# VNA.net
KiCad netlist of a schematic drawn in EAGLE
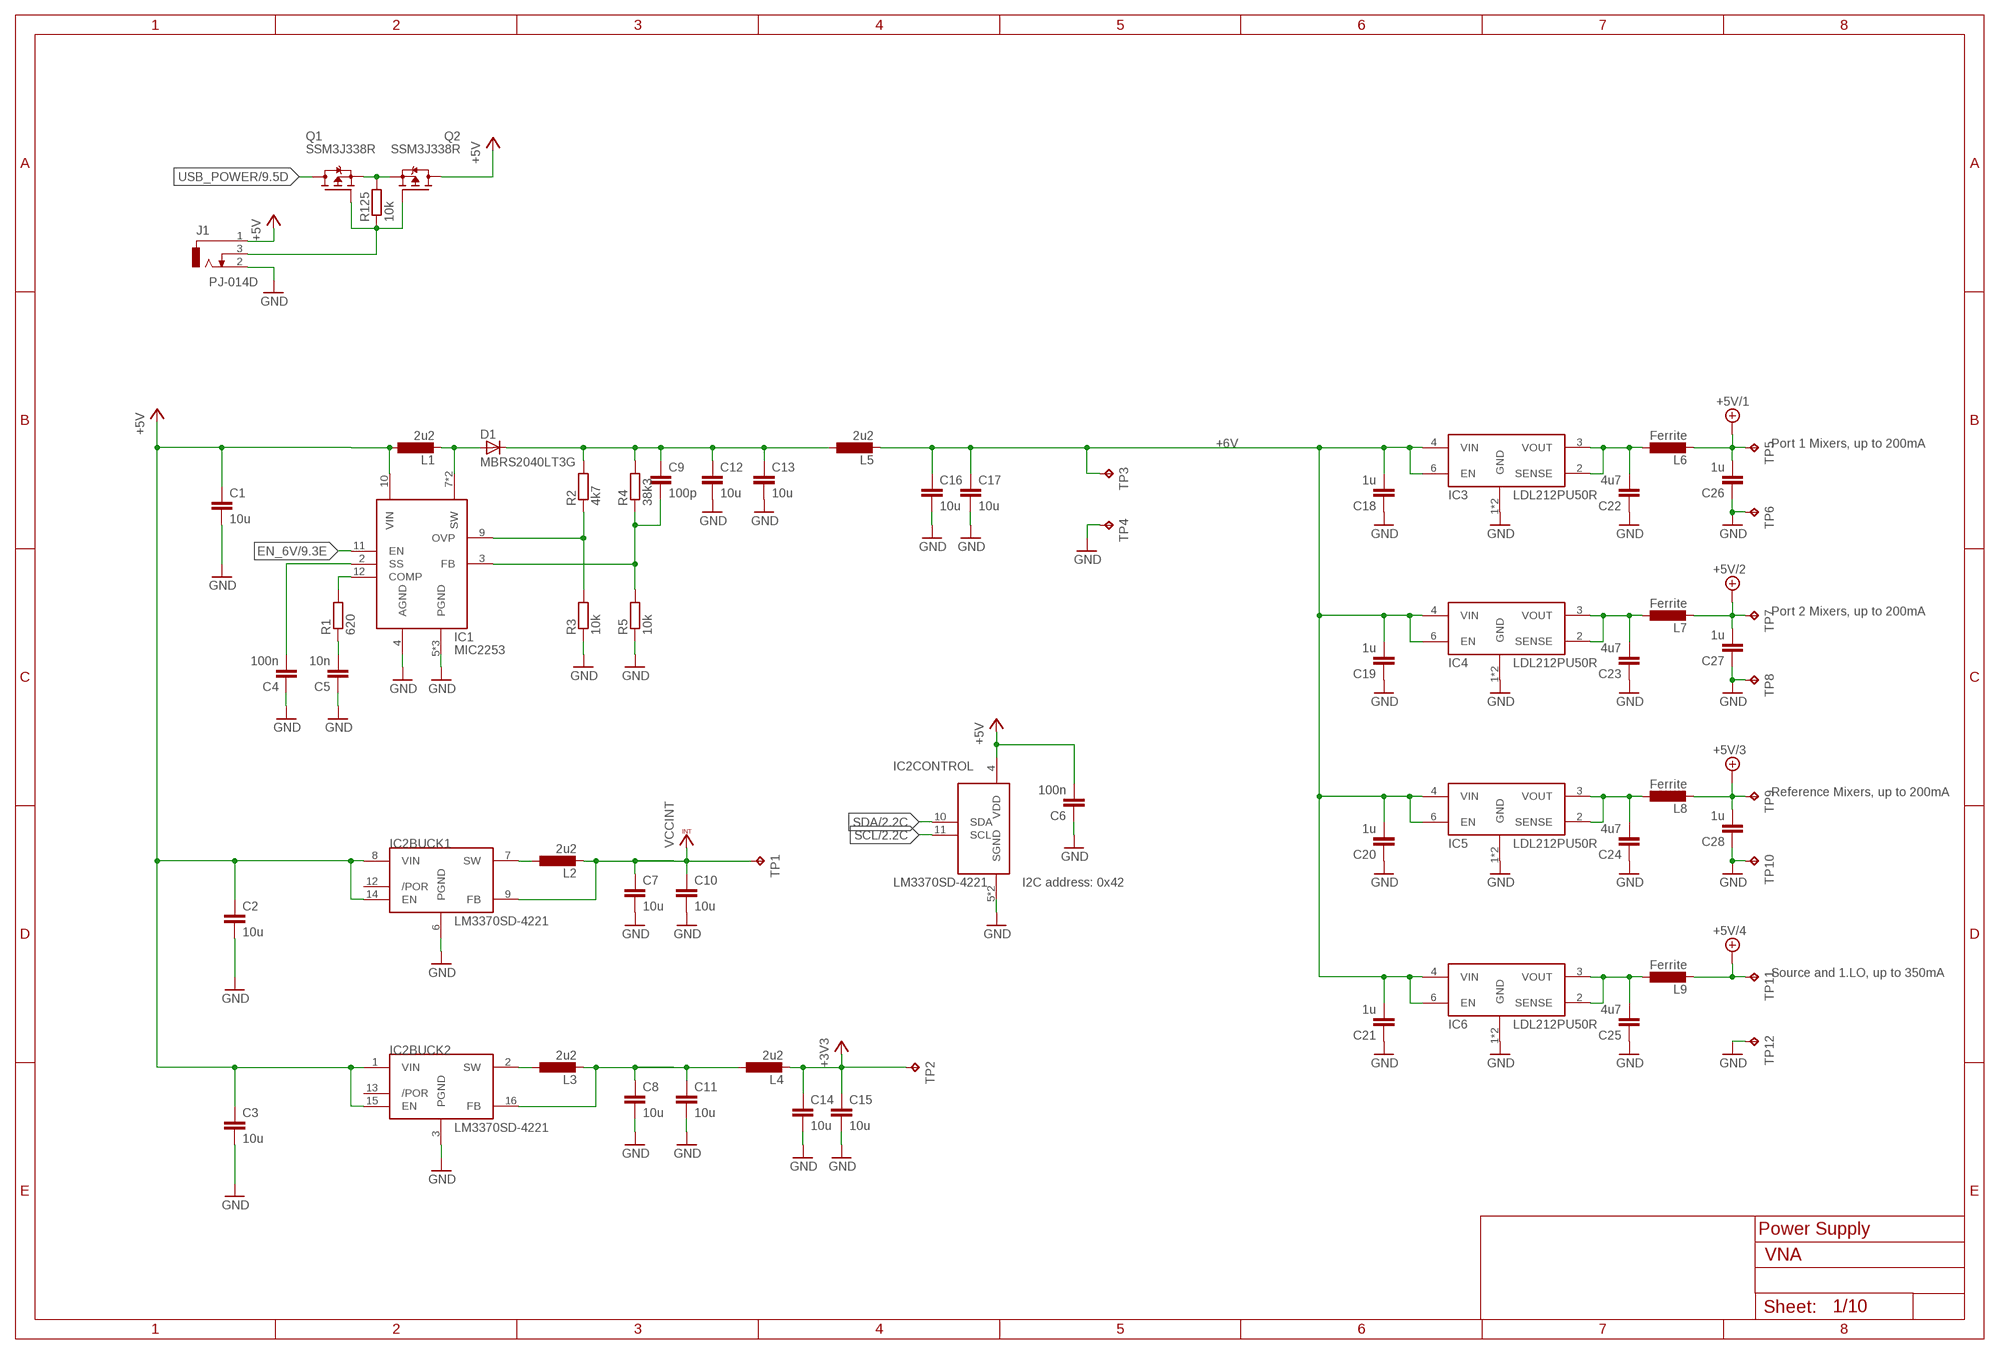
[diagram p0: schematic, sheet 1]
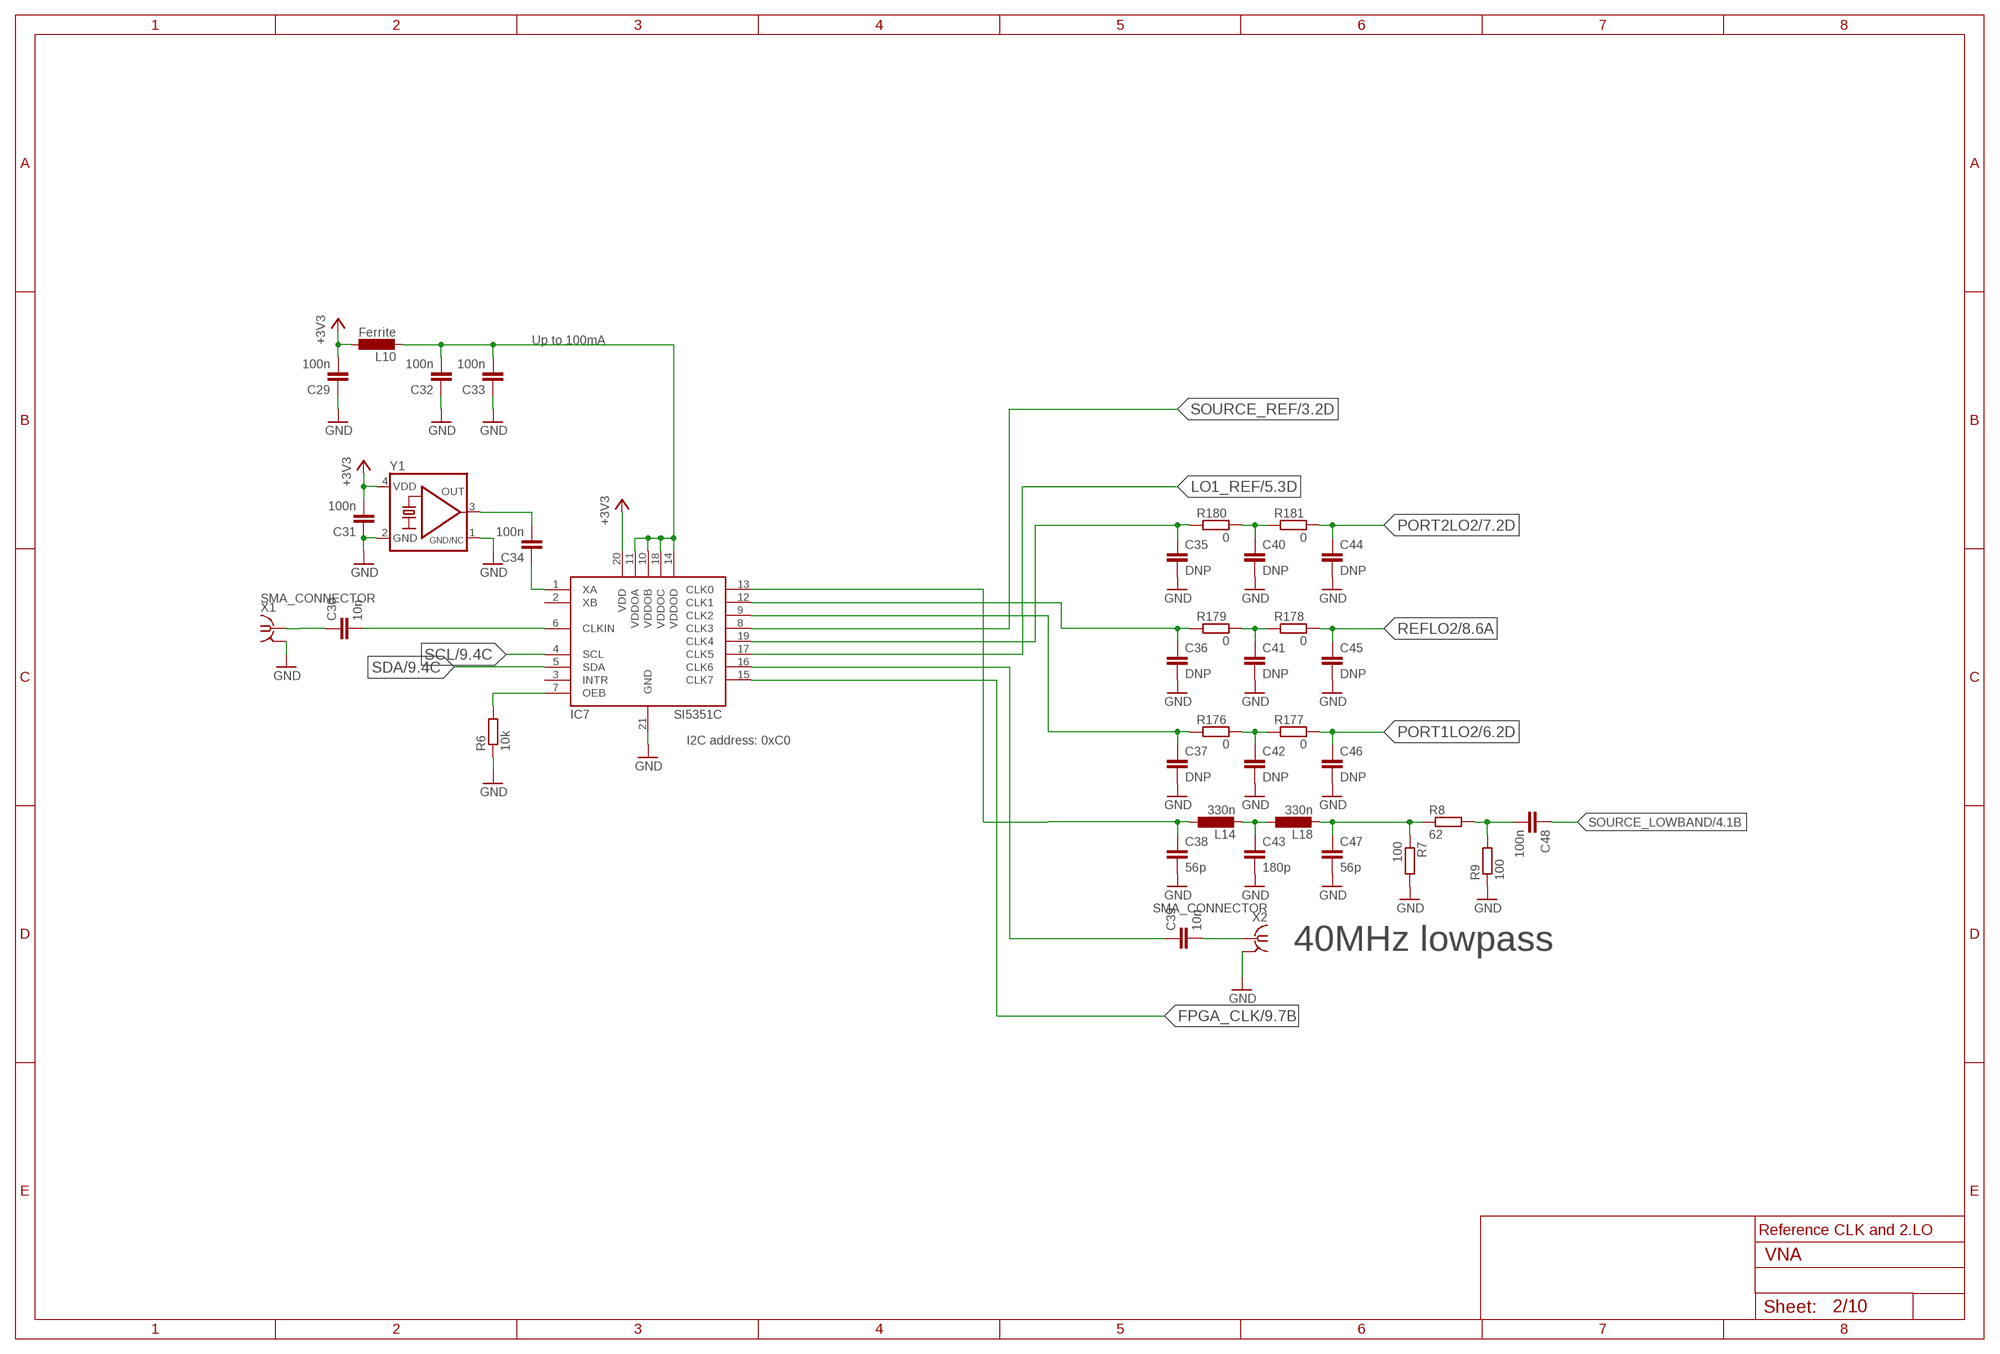
[diagram p1: schematic, sheet 2]
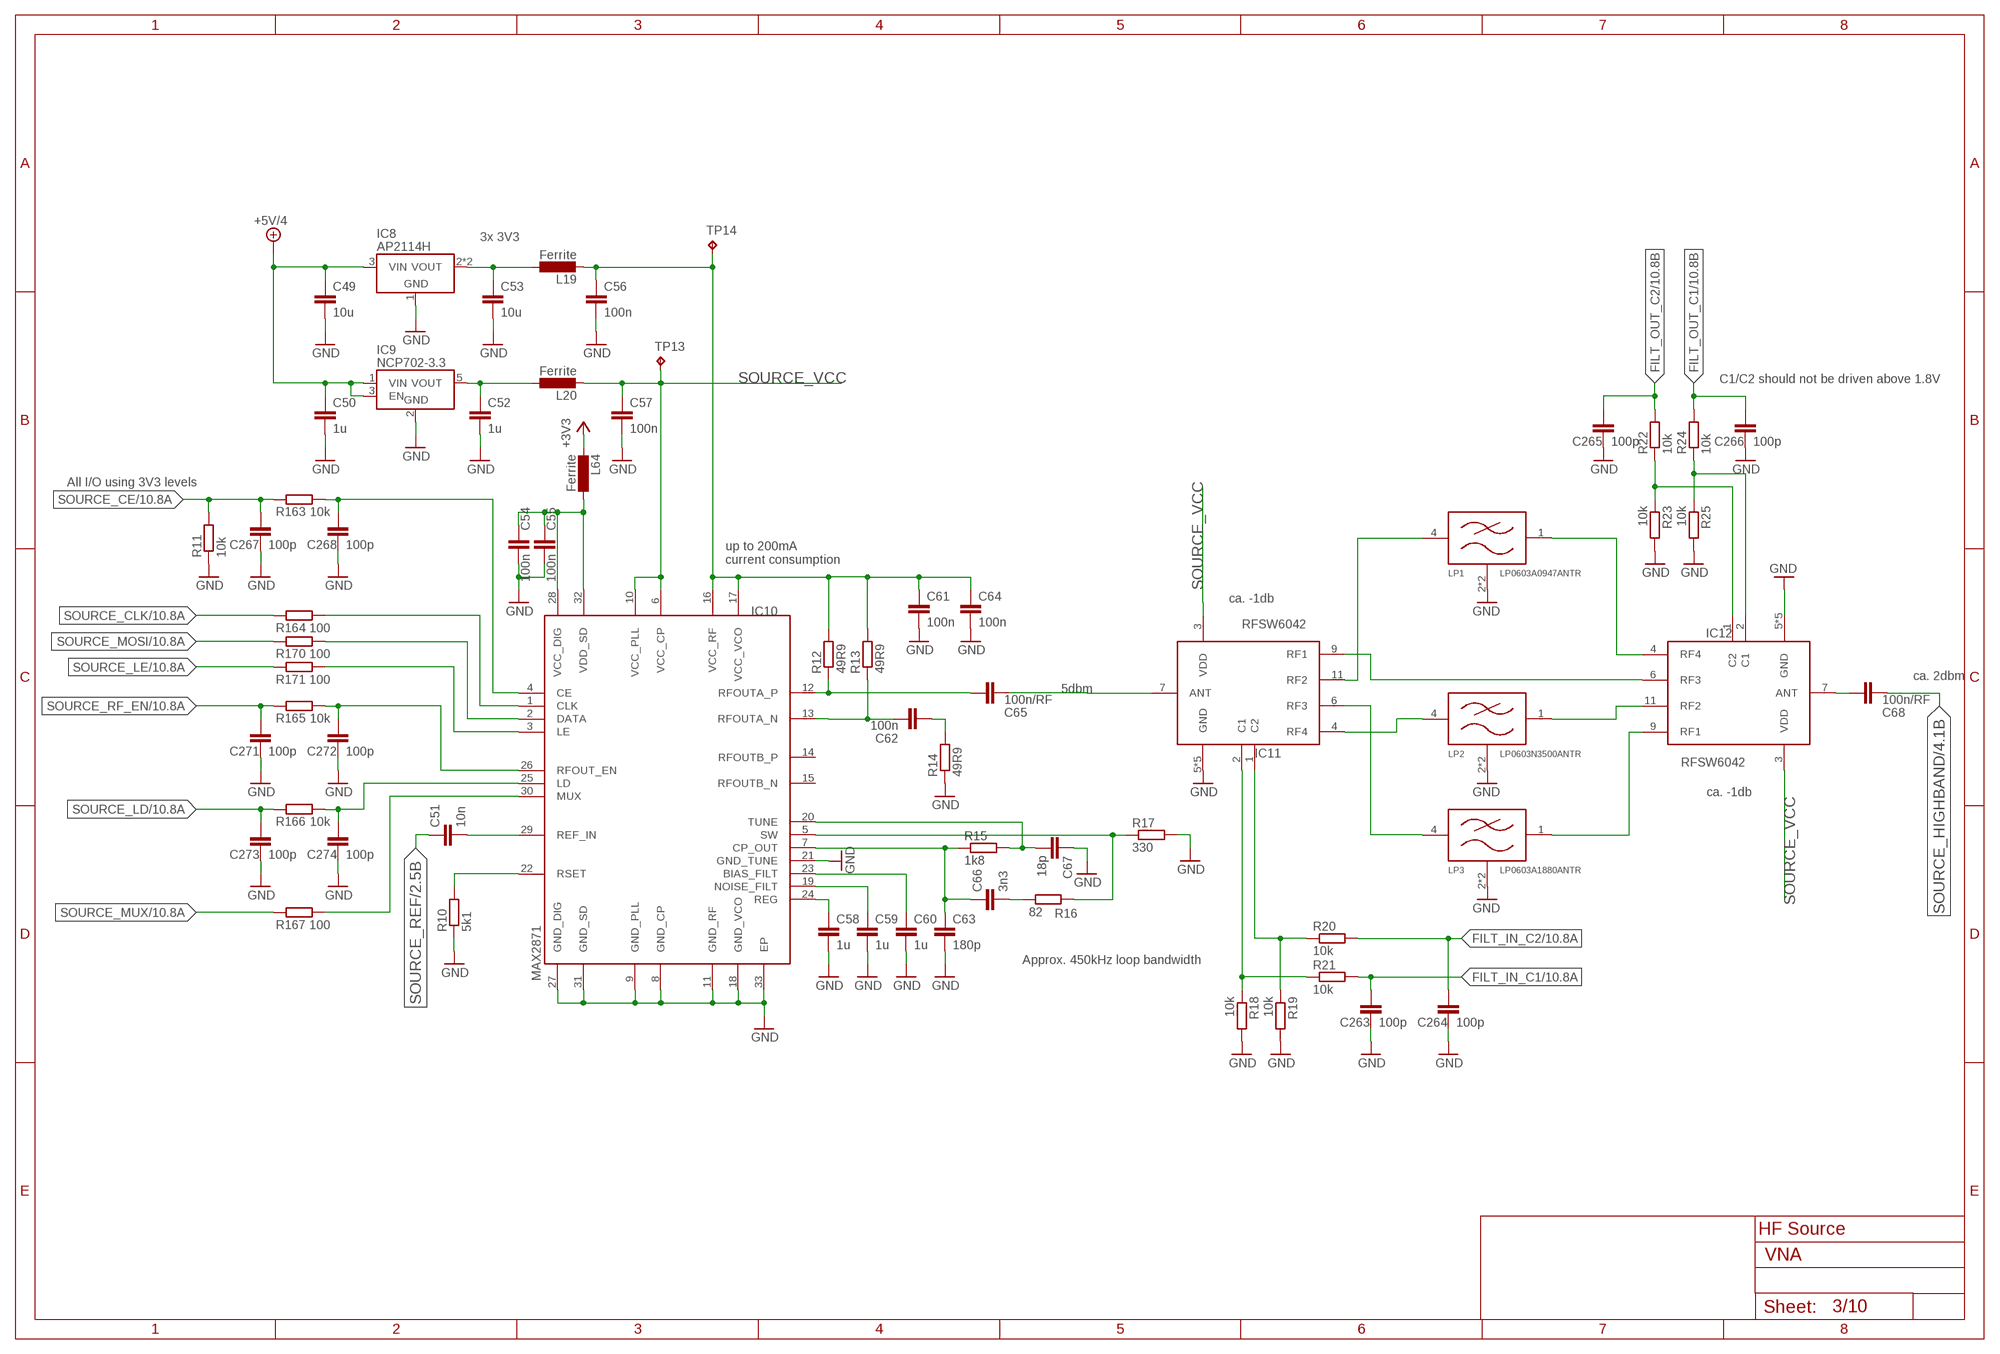
[diagram p2: schematic, sheet 3]
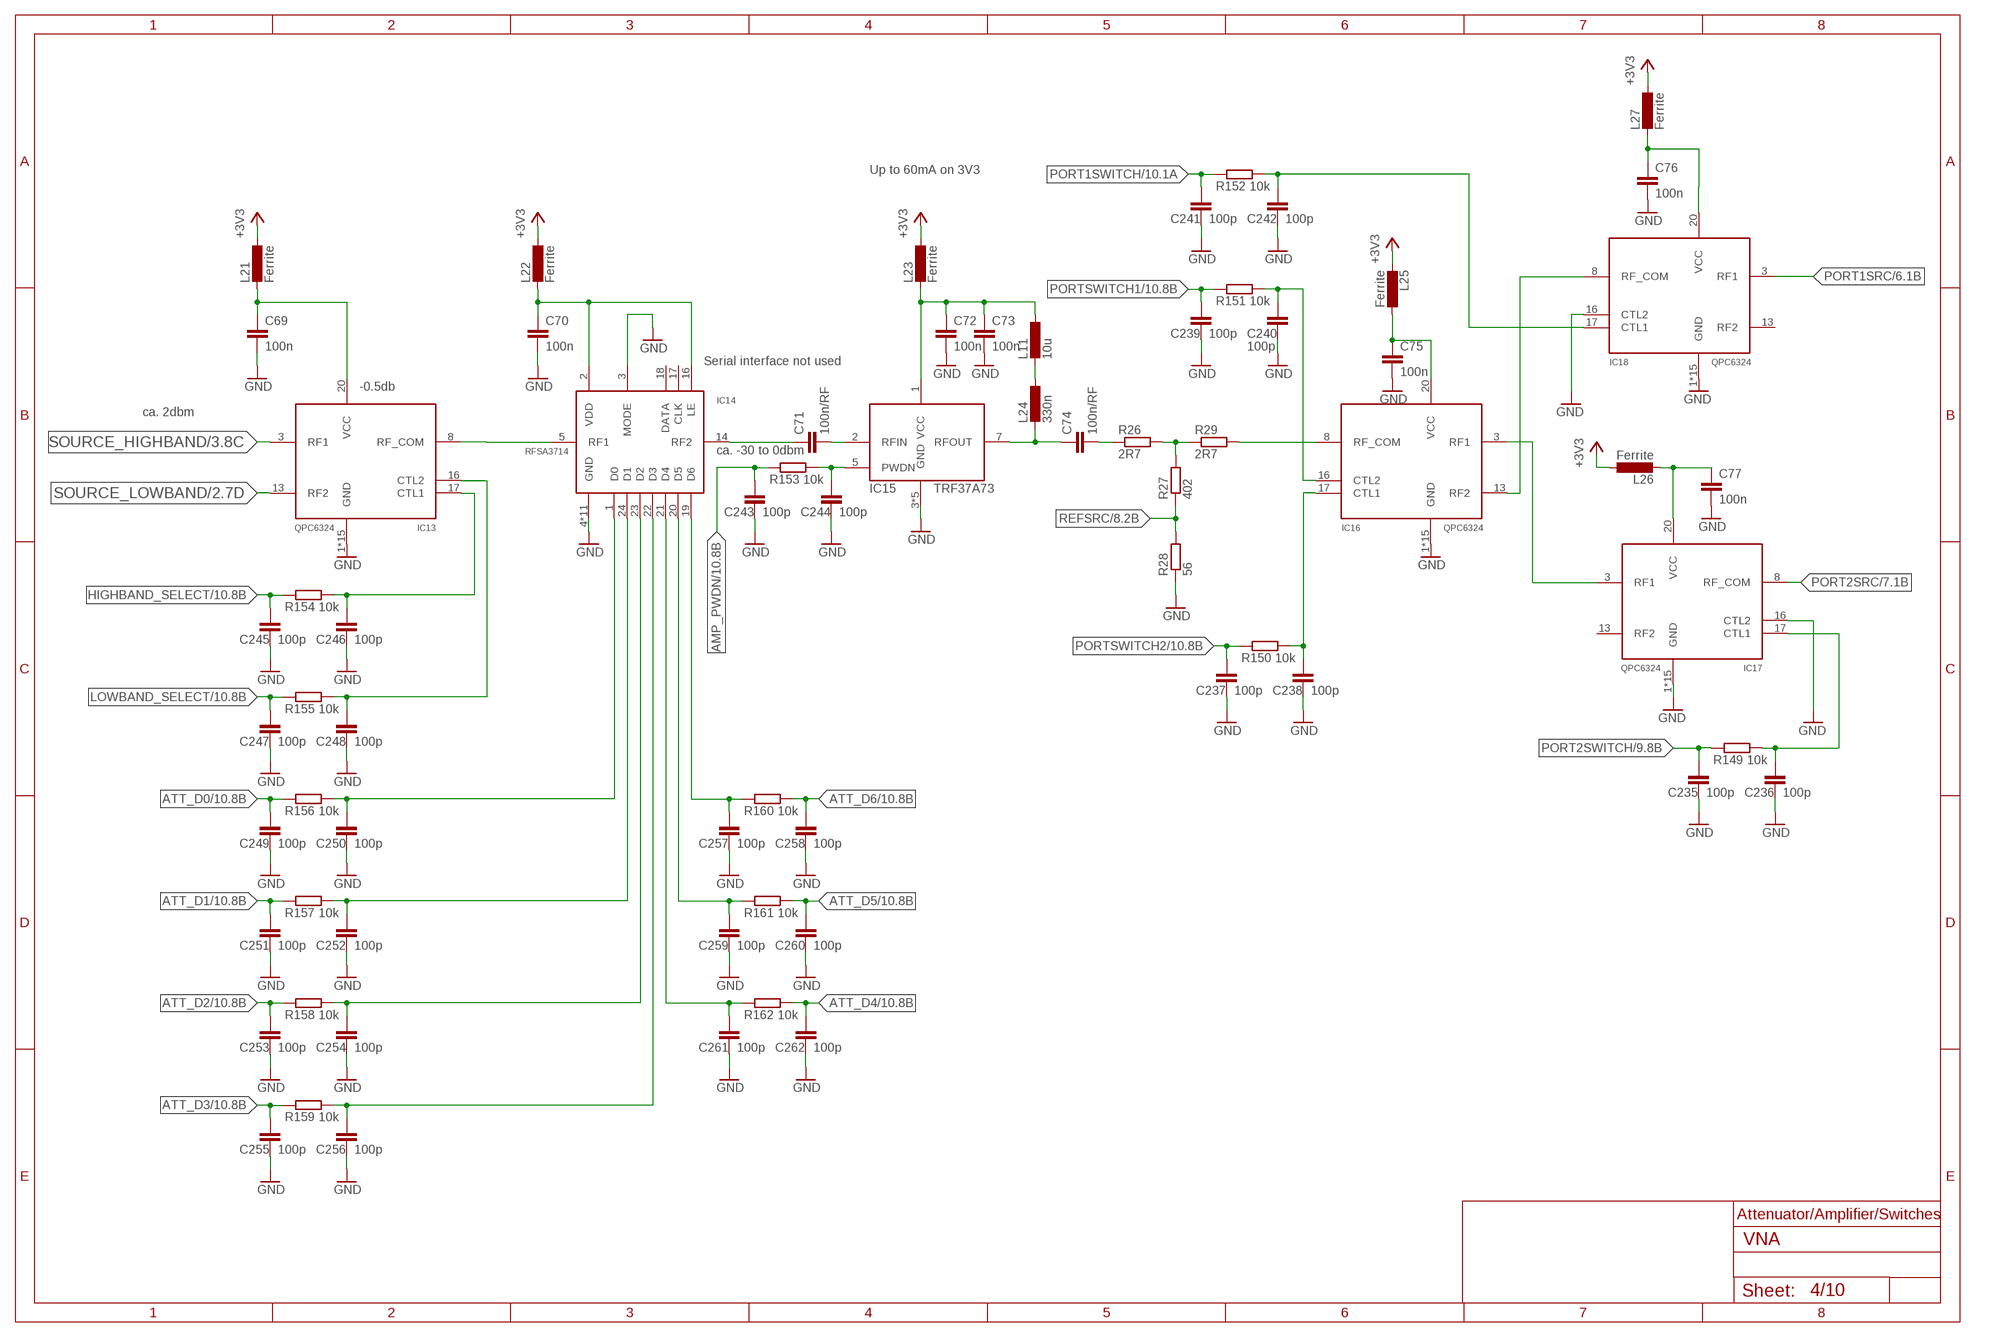
[diagram p3: schematic, sheet 4]
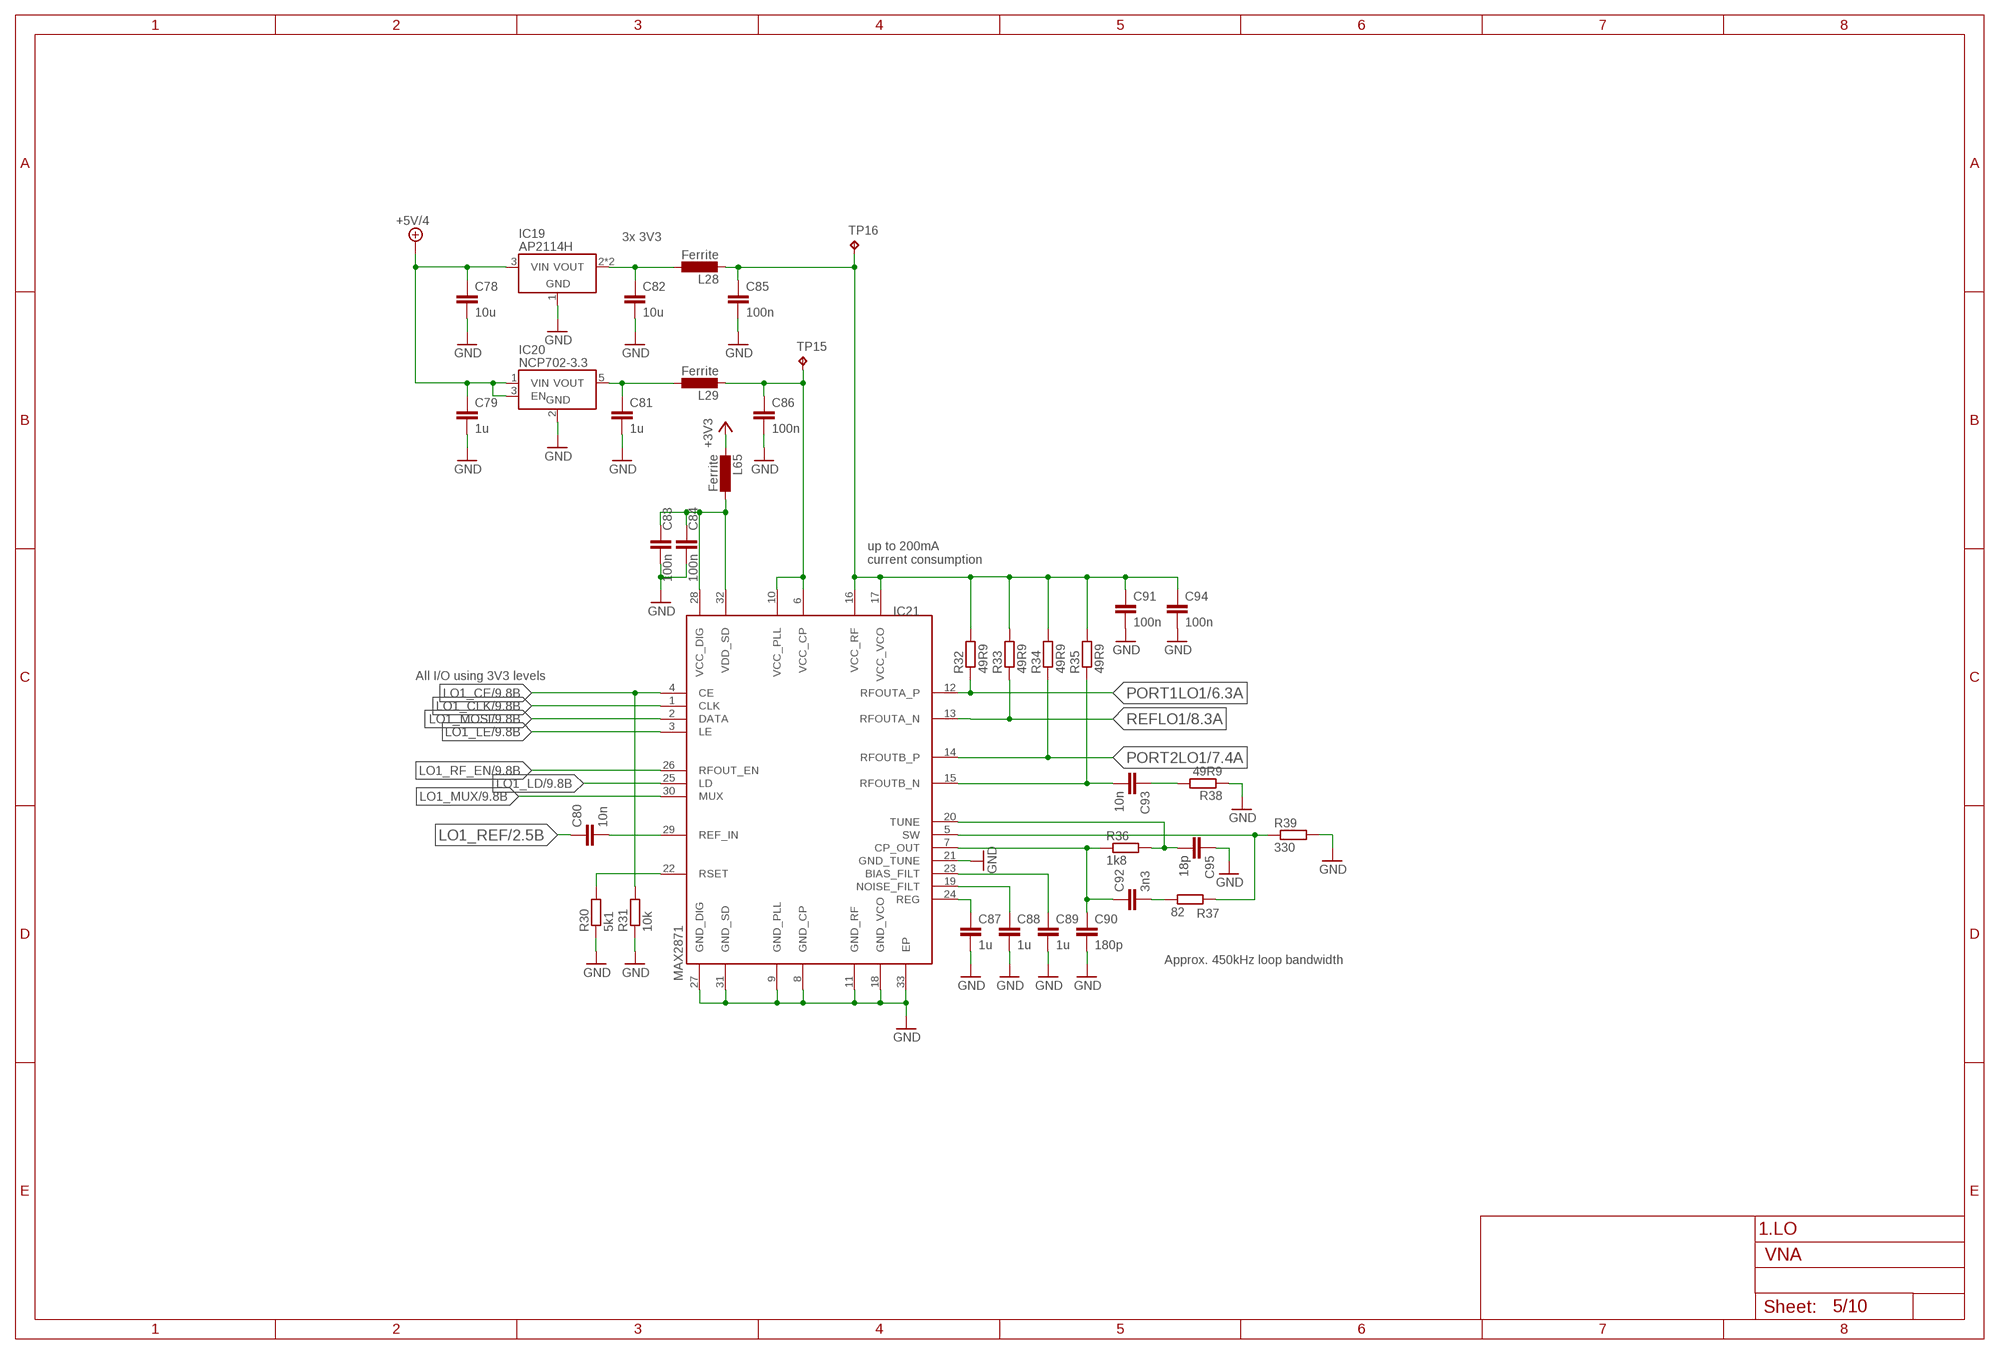
[diagram p4: schematic, sheet 5]
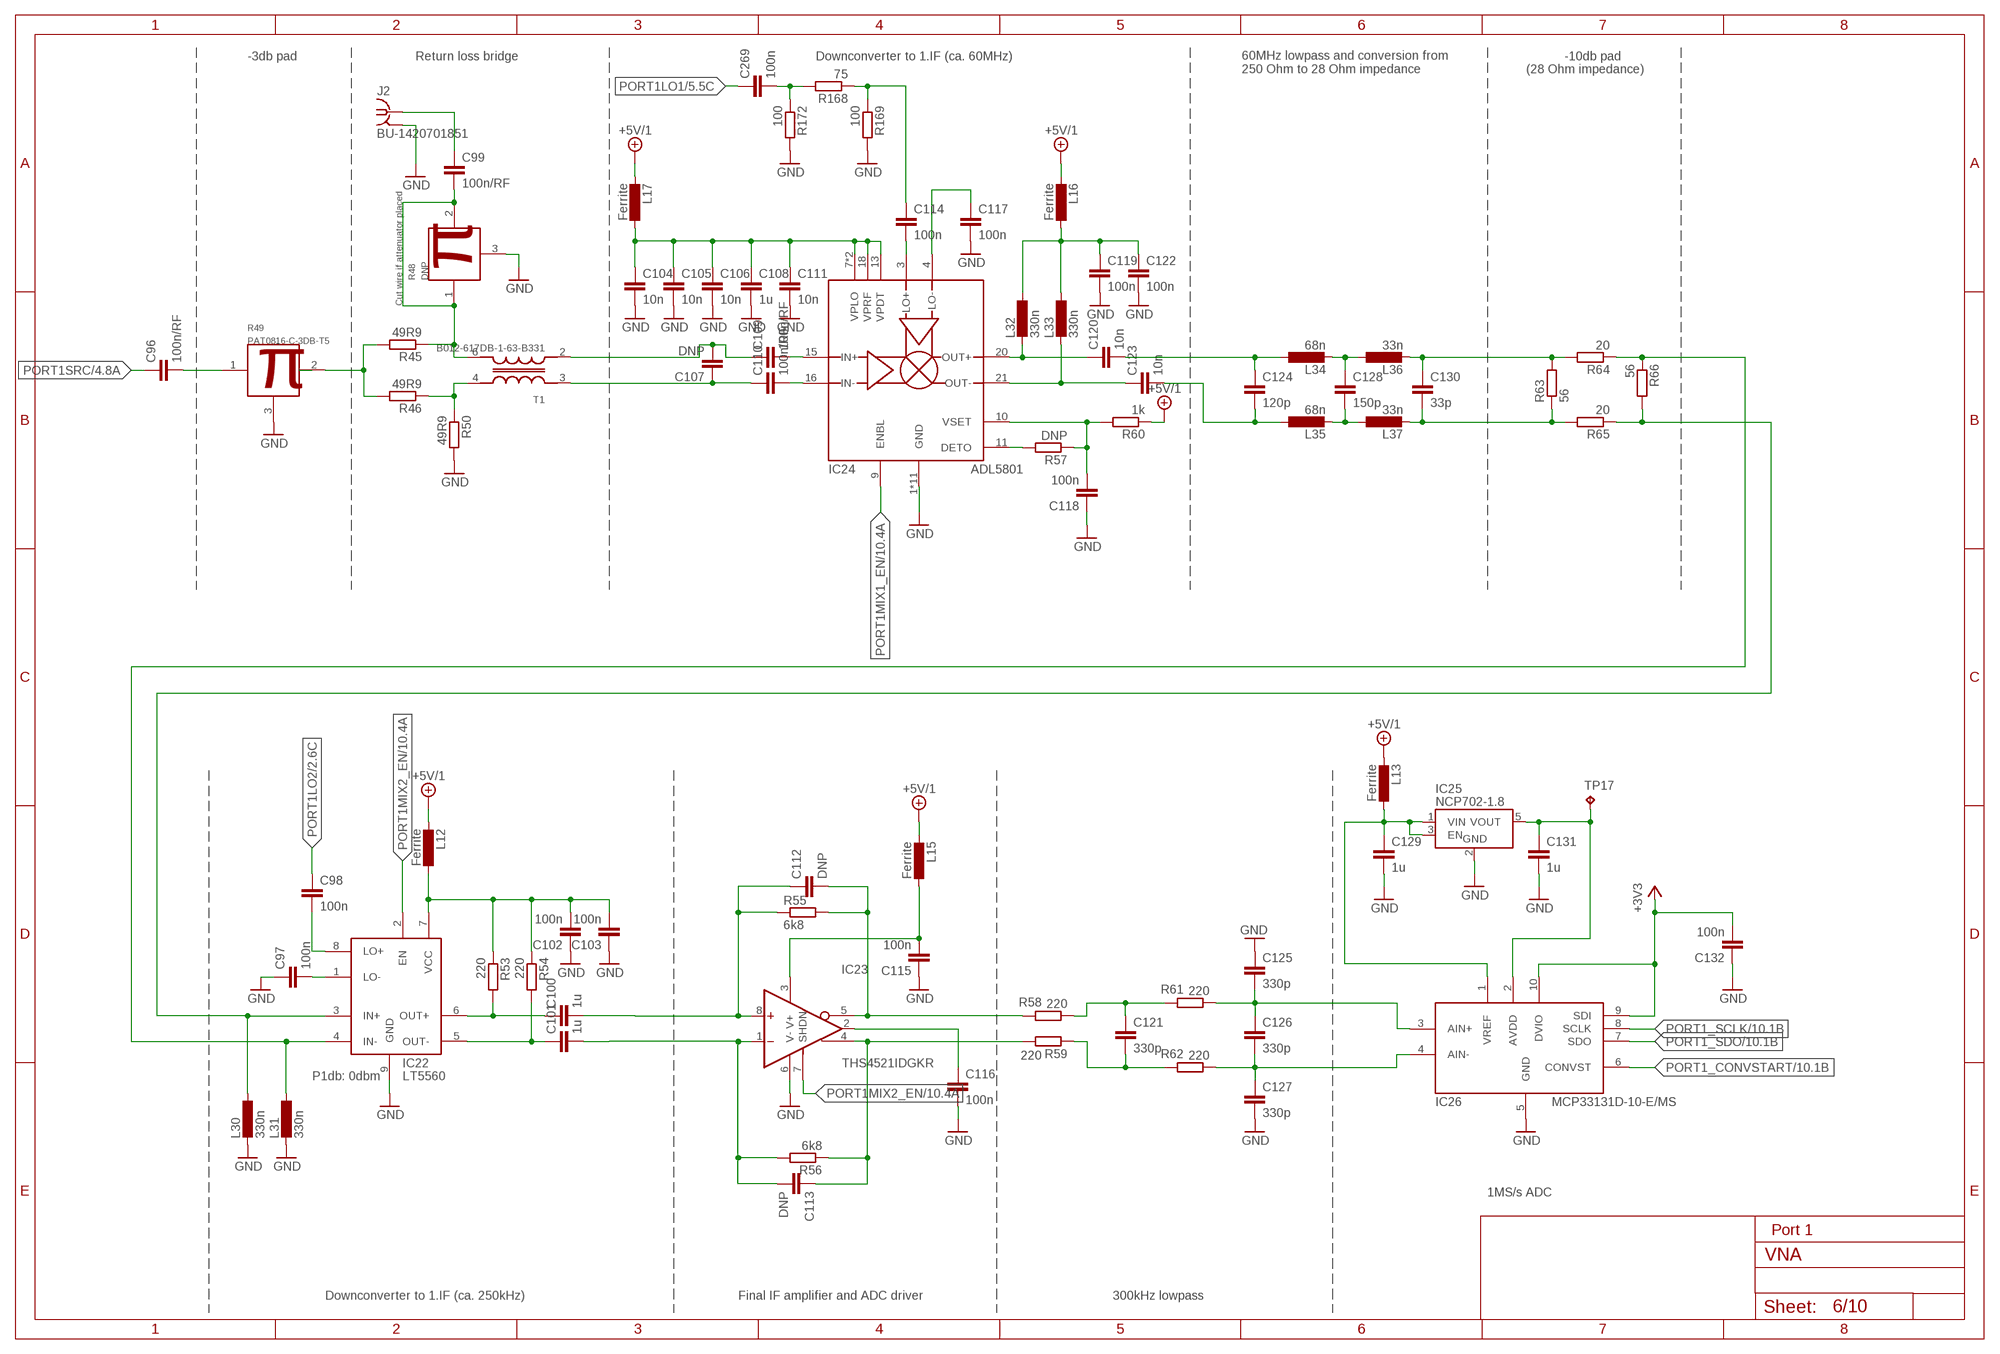
[diagram p5: schematic, sheet 6]
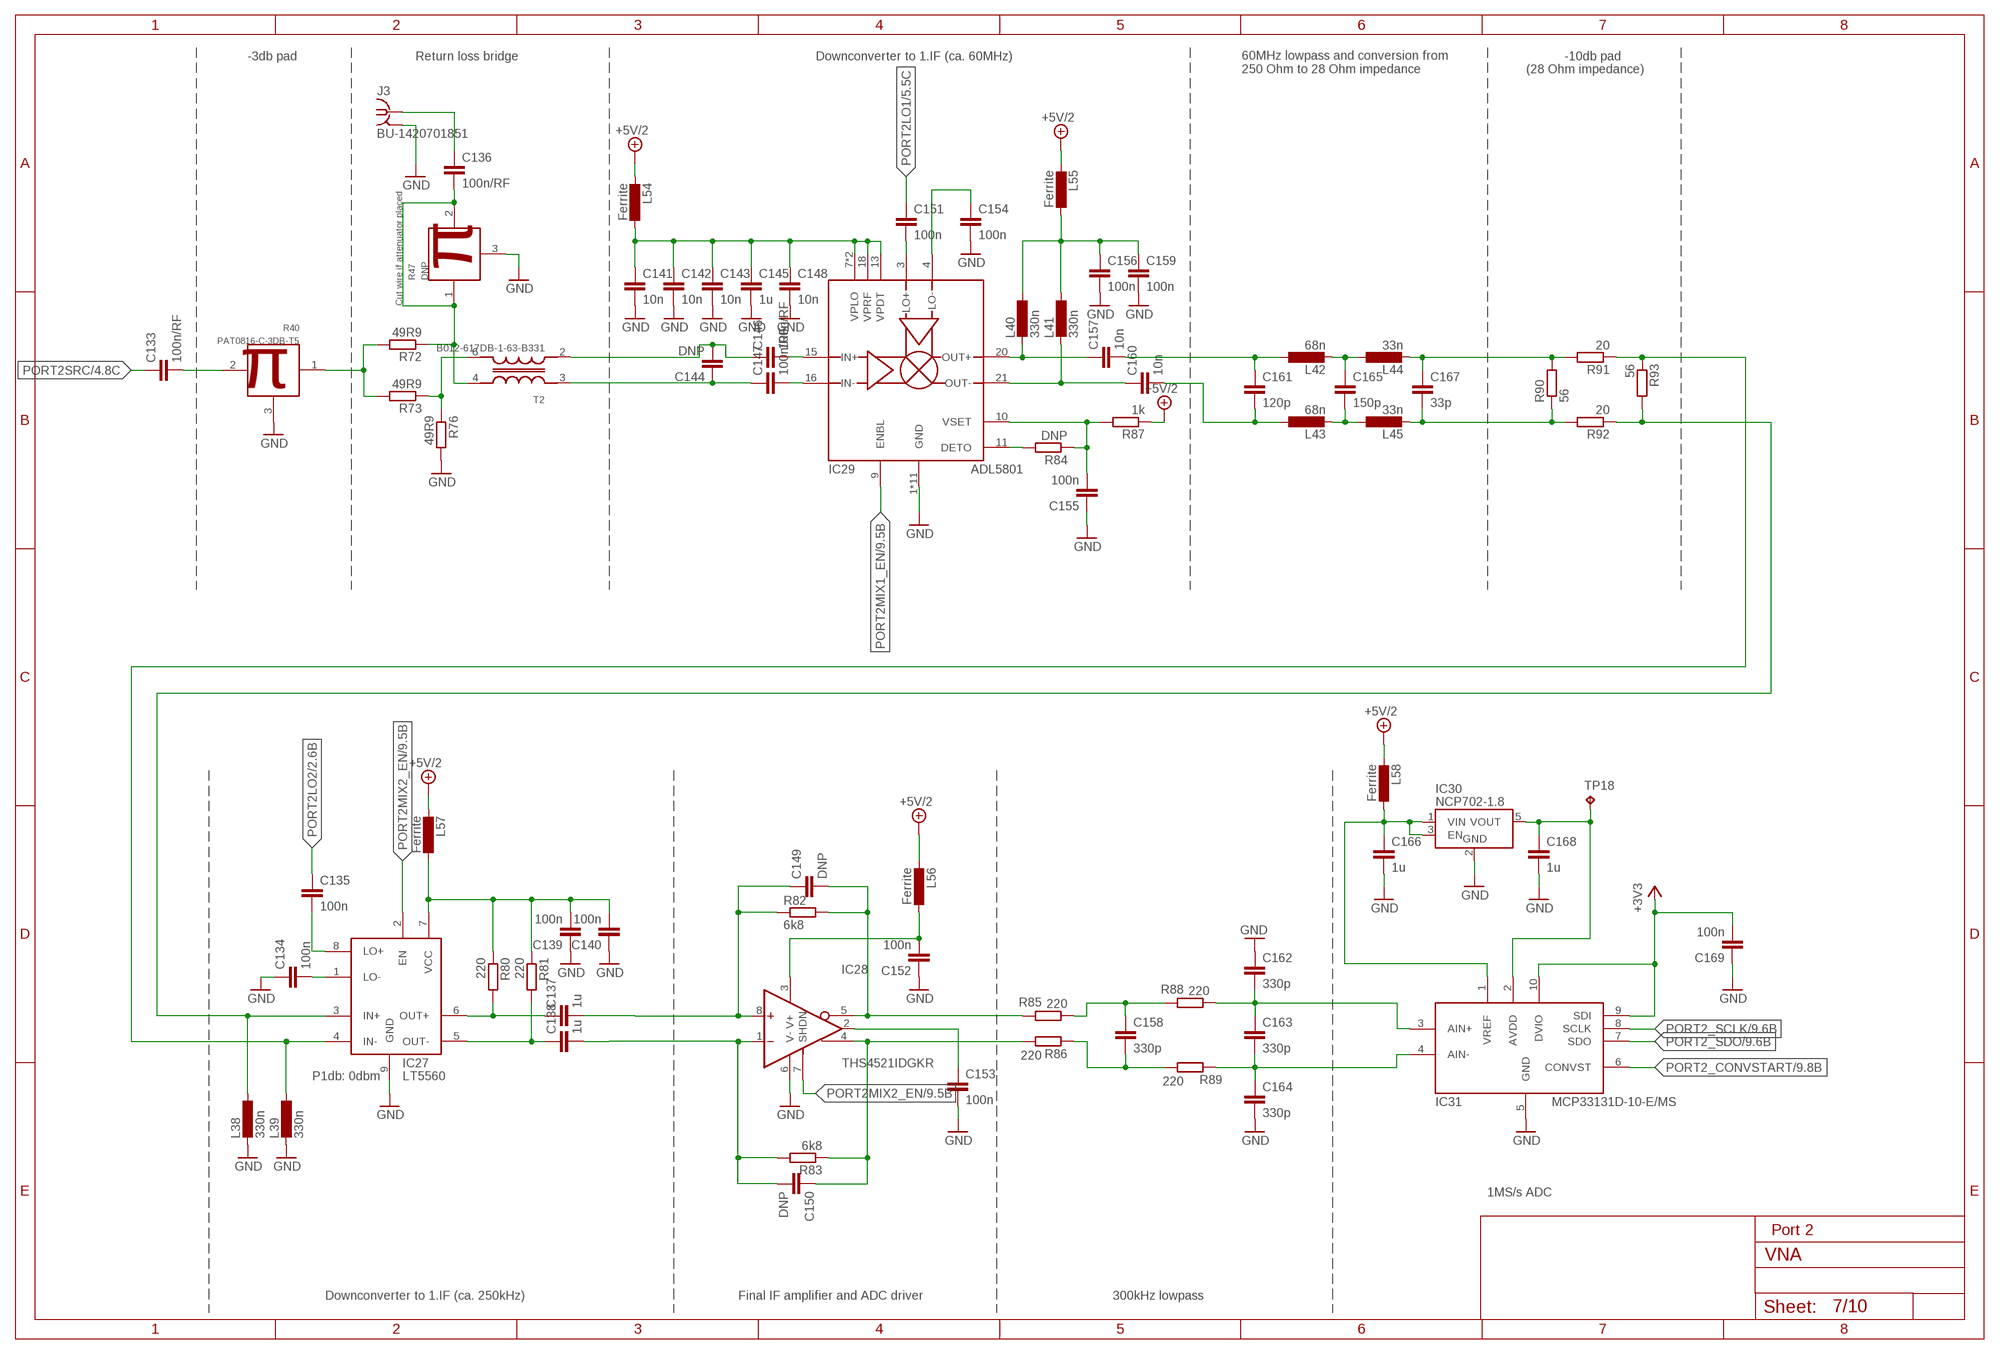
[diagram p6: schematic, sheet 7]
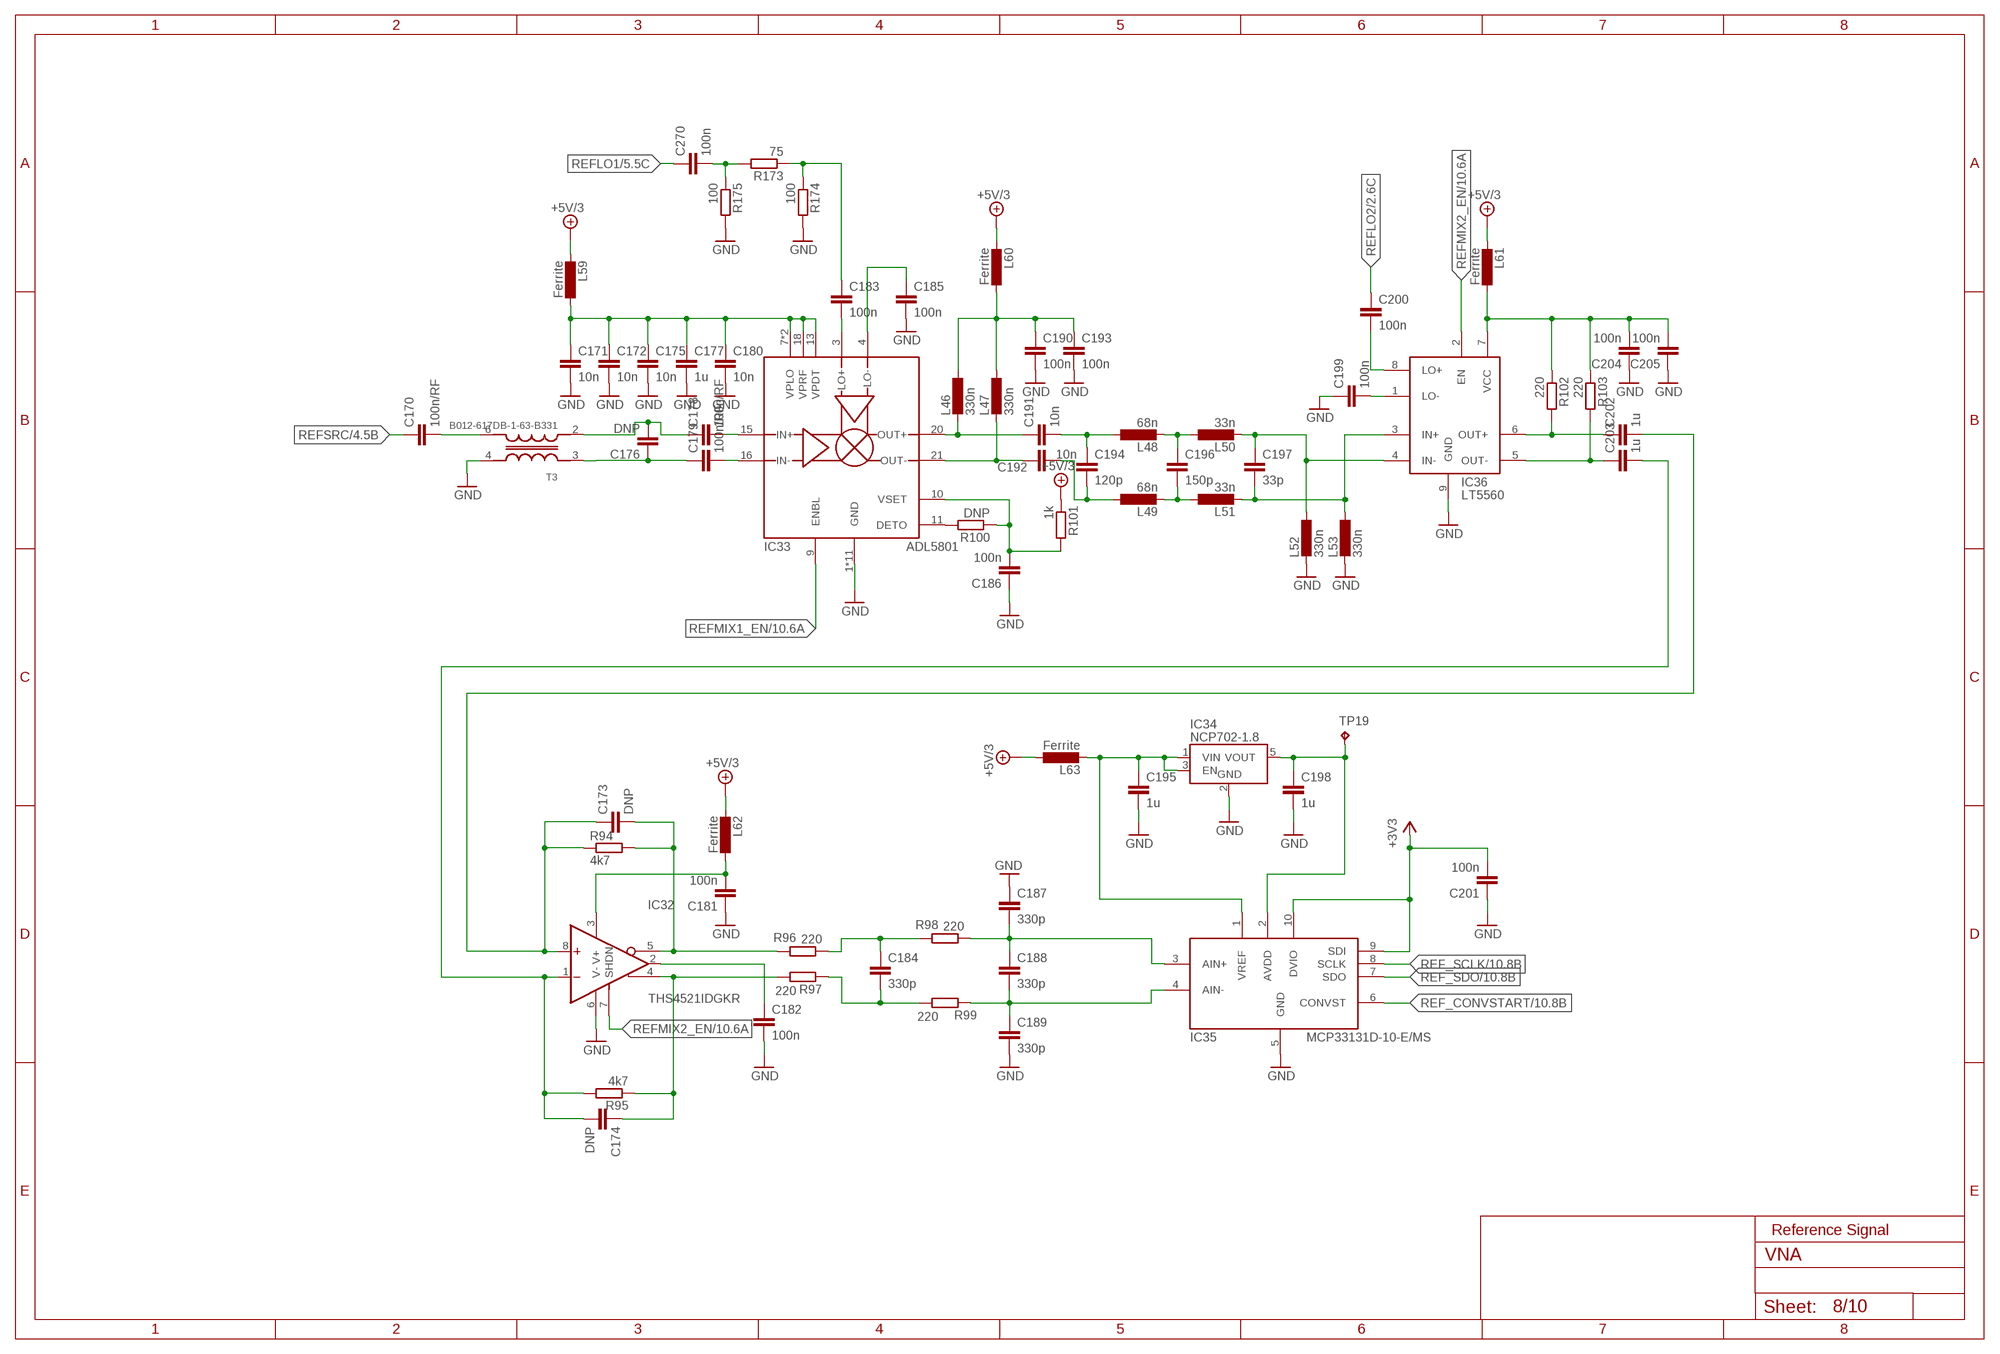
[diagram p7: schematic, sheet 8]
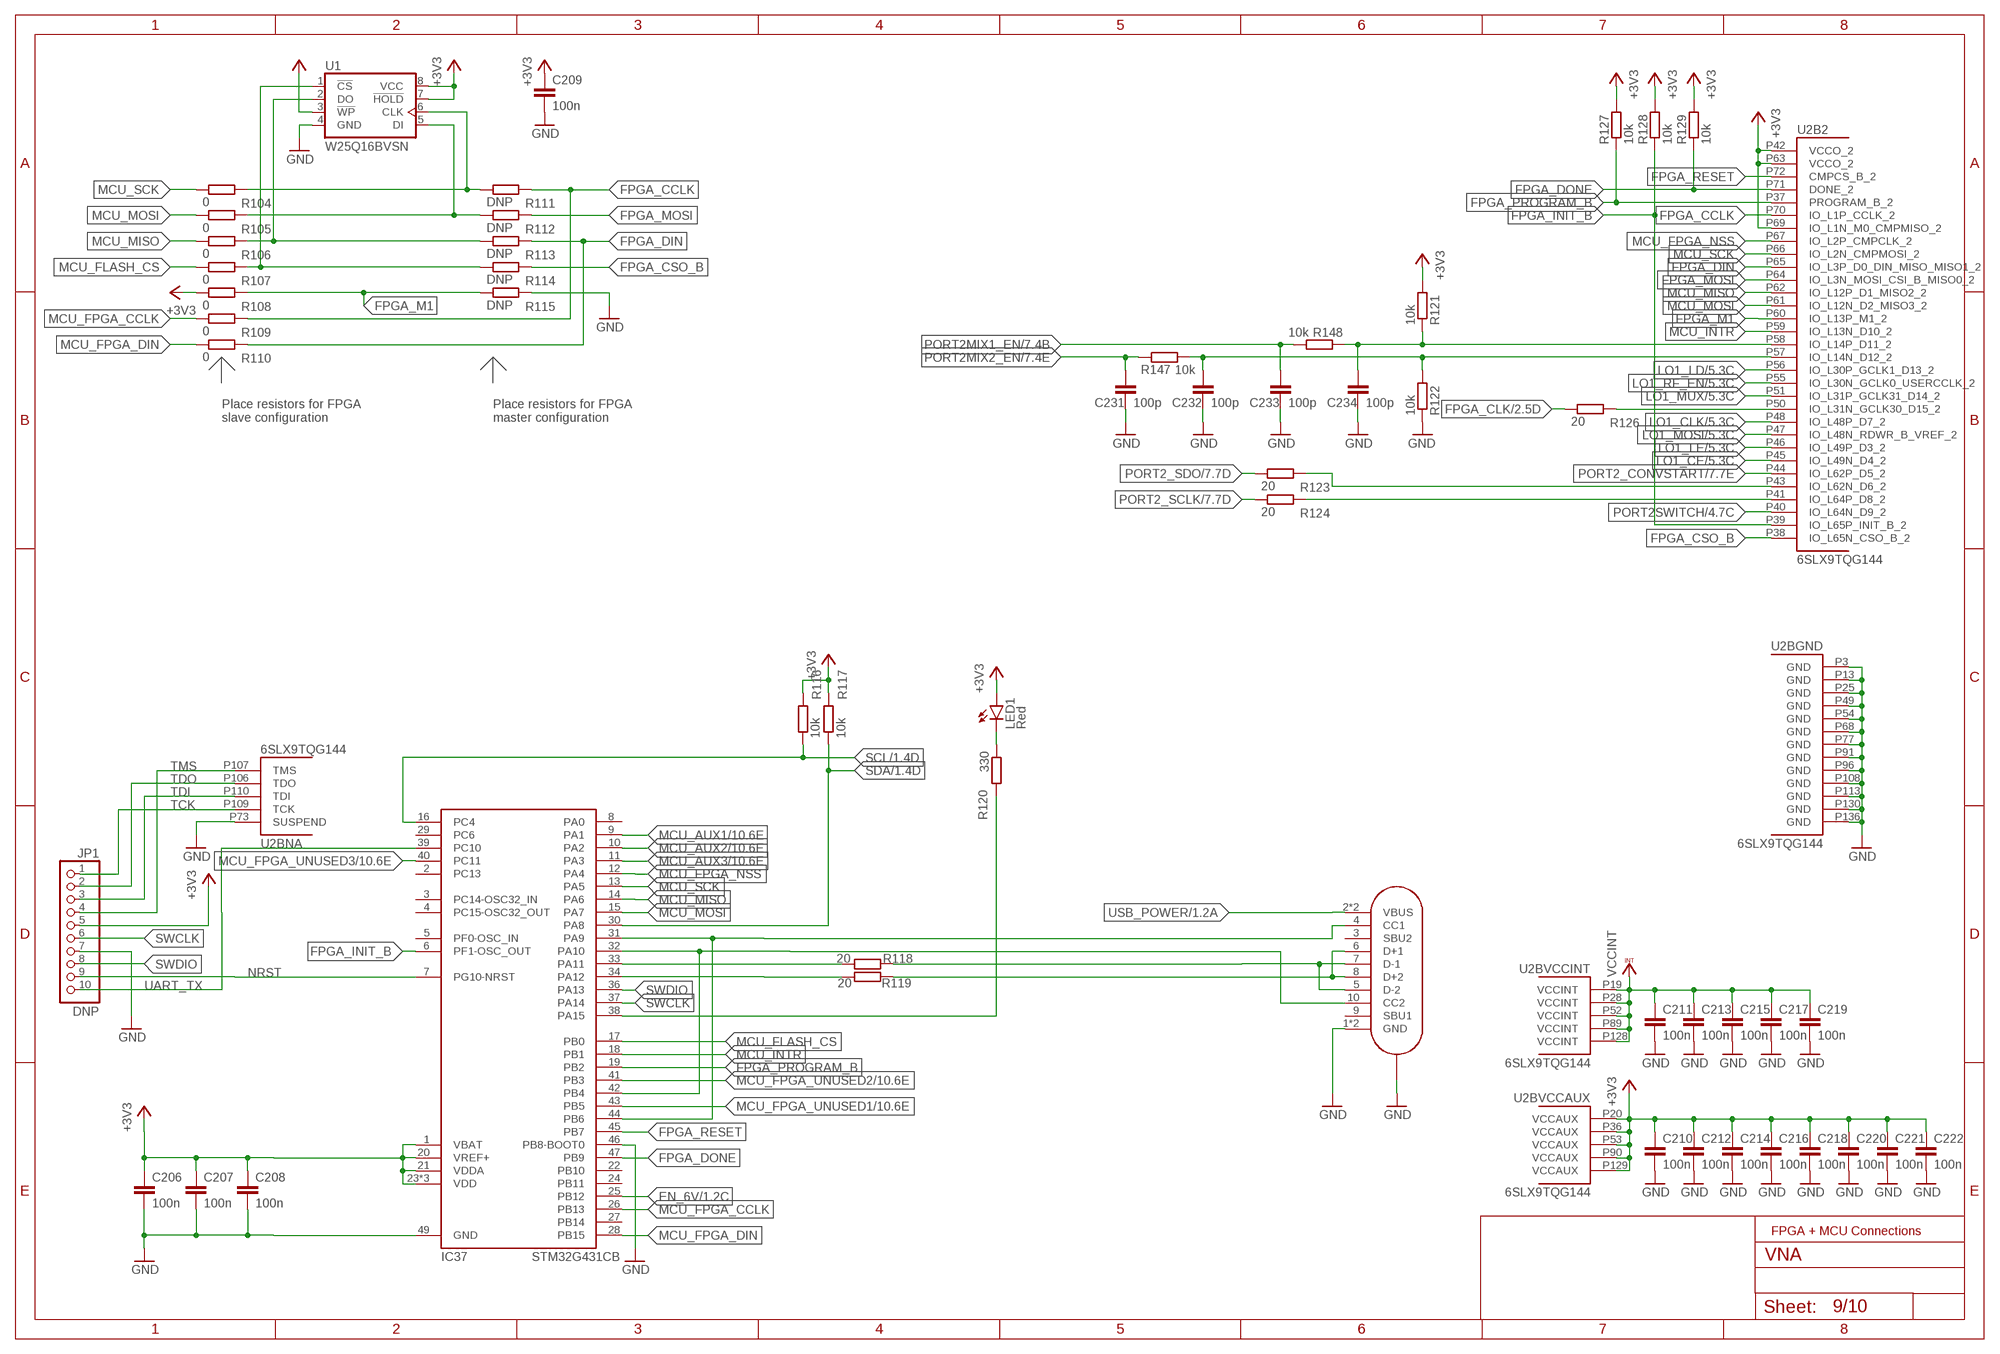
[diagram p8: schematic, sheet 9]
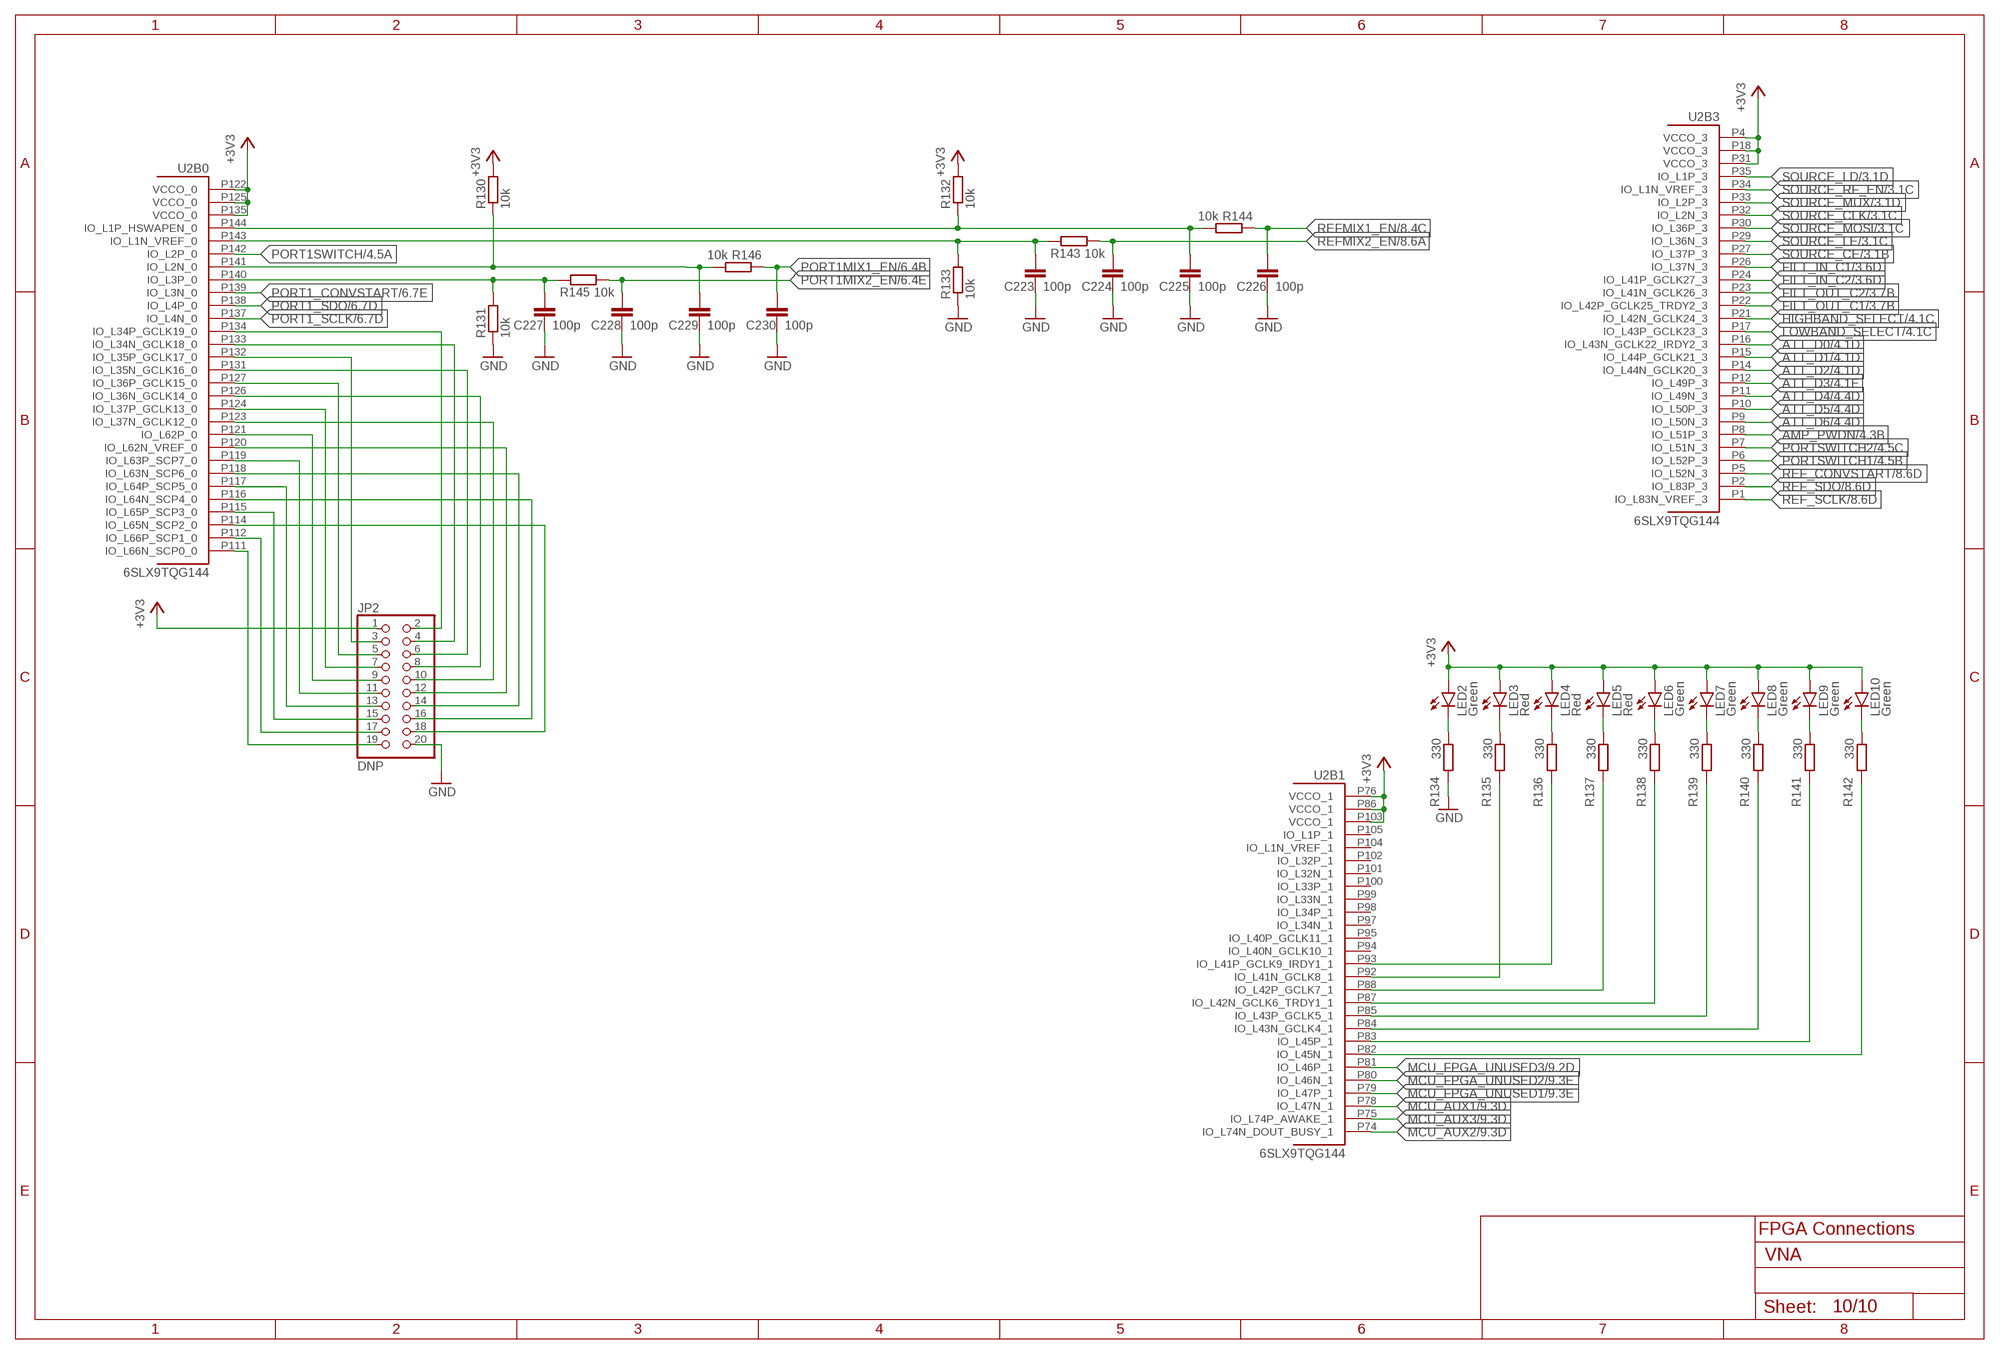
[diagram p9: schematic, sheet 10]

(export (version "E")
  (design (tool "Eeschema 10.0.6"))
  (components
    (comp (ref "C206")
      (value "100n")
      (footprint "eagle-import:C0402")
      (libsource (lib "eagle-import") (part "C-EU?{colon}2C0402"))
    )
    (comp (ref "C207")
      (value "100n")
      (footprint "eagle-import:C0402")
      (libsource (lib "eagle-import") (part "C-EU?{colon}2C0402"))
    )
    (comp (ref "C208")
      (value "100n")
      (footprint "eagle-import:C0402")
      (libsource (lib "eagle-import") (part "C-EU?{colon}2C0402"))
    )
    (comp (ref "C209")
      (value "100n")
      (footprint "eagle-import:C0402")
      (libsource (lib "eagle-import") (part "C-EU?{colon}2C0402"))
    )
    (comp (ref "C210")
      (value "100n")
      (footprint "eagle-import:C0402")
      (libsource (lib "eagle-import") (part "C-EU?{colon}2C0402"))
    )
    (comp (ref "C211")
      (value "100n")
      (footprint "eagle-import:C0402")
      (libsource (lib "eagle-import") (part "C-EU?{colon}2C0402"))
    )
    (comp (ref "C212")
      (value "100n")
      (footprint "eagle-import:C0402")
      (libsource (lib "eagle-import") (part "C-EU?{colon}2C0402"))
    )
    (comp (ref "C213")
      (value "100n")
      (footprint "eagle-import:C0402")
      (libsource (lib "eagle-import") (part "C-EU?{colon}2C0402"))
    )
    (comp (ref "C214")
      (value "100n")
      (footprint "eagle-import:C0402")
      (libsource (lib "eagle-import") (part "C-EU?{colon}2C0402"))
    )
    (comp (ref "C215")
      (value "100n")
      (footprint "eagle-import:C0402")
      (libsource (lib "eagle-import") (part "C-EU?{colon}2C0402"))
    )
    (comp (ref "C216")
      (value "100n")
      (footprint "eagle-import:C0402")
      (libsource (lib "eagle-import") (part "C-EU?{colon}2C0402"))
    )
    (comp (ref "C217")
      (value "100n")
      (footprint "eagle-import:C0402")
      (libsource (lib "eagle-import") (part "C-EU?{colon}2C0402"))
    )
    (comp (ref "C218")
      (value "100n")
      (footprint "eagle-import:C0402")
      (libsource (lib "eagle-import") (part "C-EU?{colon}2C0402"))
    )
    (comp (ref "C219")
      (value "100n")
      (footprint "eagle-import:C0402")
      (libsource (lib "eagle-import") (part "C-EU?{colon}2C0402"))
    )
    (comp (ref "C220")
      (value "100n")
      (footprint "eagle-import:C0402")
      (libsource (lib "eagle-import") (part "C-EU?{colon}2C0402"))
    )
    (comp (ref "C221")
      (value "100n")
      (footprint "eagle-import:C0402")
      (libsource (lib "eagle-import") (part "C-EU?{colon}2C0402"))
    )
    (comp (ref "C222")
      (value "100n")
      (footprint "eagle-import:C0402")
      (libsource (lib "eagle-import") (part "C-EU?{colon}2C0402"))
    )
    (comp (ref "C231")
      (value "100p")
      (footprint "eagle-import:C0402")
      (libsource (lib "eagle-import") (part "C-EU?{colon}2C0402"))
    )
    (comp (ref "C232")
      (value "100p")
      (footprint "eagle-import:C0402")
      (libsource (lib "eagle-import") (part "C-EU?{colon}2C0402"))
    )
    (comp (ref "C233")
      (value "100p")
      (footprint "eagle-import:C0402")
      (libsource (lib "eagle-import") (part "C-EU?{colon}2C0402"))
    )
    (comp (ref "C234")
      (value "100p")
      (footprint "eagle-import:C0402")
      (libsource (lib "eagle-import") (part "C-EU?{colon}2C0402"))
    )
    (comp (ref "IC37")
      (value "STM32G431CB")
      (footprint "eagle-import:QFN50P700X700X60-49T560N")
      (libsource (lib "eagle-import") (part "STM32G431CB"))
    )
    (comp (ref "J4")
      (value "TYPE-C16P(073)")
      (footprint "eagle-import:TYPE-C16P")
      (libsource (lib "eagle-import") (part "TYPE-C16P(073)"))
    )
    (comp (ref "JP1")
      (value "DNP")
      (footprint "eagle-import:1X10_90")
      (libsource (lib "eagle-import") (part "PINHD-1X10/90"))
    )
    (comp (ref "LED1")
      (value "Red")
      (footprint "eagle-import:CHIPLED_0603")
      (libsource (lib "eagle-import") (part "LEDCHIPLED_0603"))
    )
    (comp (ref "R104")
      (value "0")
      (footprint "eagle-import:R0402")
      (libsource (lib "eagle-import") (part "R-EU_R0402"))
    )
    (comp (ref "R105")
      (value "0")
      (footprint "eagle-import:R0402")
      (libsource (lib "eagle-import") (part "R-EU_R0402"))
    )
    (comp (ref "R106")
      (value "0")
      (footprint "eagle-import:R0402")
      (libsource (lib "eagle-import") (part "R-EU_R0402"))
    )
    (comp (ref "R107")
      (value "0")
      (footprint "eagle-import:R0402")
      (libsource (lib "eagle-import") (part "R-EU_R0402"))
    )
    (comp (ref "R108")
      (value "0")
      (footprint "eagle-import:R0402")
      (libsource (lib "eagle-import") (part "R-EU_R0402"))
    )
    (comp (ref "R109")
      (value "0")
      (footprint "eagle-import:R0402")
      (libsource (lib "eagle-import") (part "R-EU_R0402"))
    )
    (comp (ref "R110")
      (value "0")
      (footprint "eagle-import:R0402")
      (libsource (lib "eagle-import") (part "R-EU_R0402"))
    )
    (comp (ref "R111")
      (value "DNP")
      (footprint "eagle-import:R0402")
      (libsource (lib "eagle-import") (part "R-EU_R0402"))
    )
    (comp (ref "R112")
      (value "DNP")
      (footprint "eagle-import:R0402")
      (libsource (lib "eagle-import") (part "R-EU_R0402"))
    )
    (comp (ref "R113")
      (value "DNP")
      (footprint "eagle-import:R0402")
      (libsource (lib "eagle-import") (part "R-EU_R0402"))
    )
    (comp (ref "R114")
      (value "DNP")
      (footprint "eagle-import:R0402")
      (libsource (lib "eagle-import") (part "R-EU_R0402"))
    )
    (comp (ref "R115")
      (value "DNP")
      (footprint "eagle-import:R0402")
      (libsource (lib "eagle-import") (part "R-EU_R0402"))
    )
    (comp (ref "R116")
      (value "10k")
      (footprint "eagle-import:R0402")
      (libsource (lib "eagle-import") (part "R-EU_R0402"))
    )
    (comp (ref "R117")
      (value "10k")
      (footprint "eagle-import:R0402")
      (libsource (lib "eagle-import") (part "R-EU_R0402"))
    )
    (comp (ref "R118")
      (value "20")
      (footprint "eagle-import:R0402")
      (libsource (lib "eagle-import") (part "R-EU_R0402"))
    )
    (comp (ref "R119")
      (value "20")
      (footprint "eagle-import:R0402")
      (libsource (lib "eagle-import") (part "R-EU_R0402"))
    )
    (comp (ref "R120")
      (value "330")
      (footprint "eagle-import:R0402")
      (libsource (lib "eagle-import") (part "R-EU_R0402"))
    )
    (comp (ref "R121")
      (value "10k")
      (footprint "eagle-import:R0402")
      (libsource (lib "eagle-import") (part "R-EU_R0402"))
    )
    (comp (ref "R122")
      (value "10k")
      (footprint "eagle-import:R0402")
      (libsource (lib "eagle-import") (part "R-EU_R0402"))
    )
    (comp (ref "R123")
      (value "20")
      (footprint "eagle-import:R0402")
      (libsource (lib "eagle-import") (part "R-EU_R0402"))
    )
    (comp (ref "R124")
      (value "20")
      (footprint "eagle-import:R0402")
      (libsource (lib "eagle-import") (part "R-EU_R0402"))
    )
    (comp (ref "R126")
      (value "20")
      (footprint "eagle-import:R0402")
      (libsource (lib "eagle-import") (part "R-EU_R0402"))
    )
    (comp (ref "R127")
      (value "10k")
      (footprint "eagle-import:R0402")
      (libsource (lib "eagle-import") (part "R-EU_R0402"))
    )
    (comp (ref "R128")
      (value "10k")
      (footprint "eagle-import:R0402")
      (libsource (lib "eagle-import") (part "R-EU_R0402"))
    )
    (comp (ref "R129")
      (value "10k")
      (footprint "eagle-import:R0402")
      (libsource (lib "eagle-import") (part "R-EU_R0402"))
    )
    (comp (ref "R147")
      (value "10k")
      (footprint "eagle-import:R0402")
      (libsource (lib "eagle-import") (part "R-EU_R0402"))
    )
    (comp (ref "R148")
      (value "10k")
      (footprint "eagle-import:R0402")
      (libsource (lib "eagle-import") (part "R-EU_R0402"))
    )
    (comp (ref "U1")
      (value "W25Q16BVSN")
      (footprint "eagle-import:SO08")
      (libsource (lib "eagle-import") (part "W25Q16BVSN"))
    )
    (comp (ref "U2")
      (value "6SLX9TQG144")
      (footprint "eagle-import:TQ144")
      (libsource (lib "eagle-import") (part "6SLX9TQG144"))
    )
    (comp (ref "C133")
      (value "100n/RF")
      (footprint "eagle-import:C0402")
      (libsource (lib "eagle-import") (part "C-EU?{colon}2C0402"))
    )
    (comp (ref "C134")
      (value "100n")
      (footprint "eagle-import:C0402")
      (libsource (lib "eagle-import") (part "C-EU?{colon}2C0402"))
    )
    (comp (ref "C135")
      (value "100n")
      (footprint "eagle-import:C0402")
      (libsource (lib "eagle-import") (part "C-EU?{colon}2C0402"))
    )
    (comp (ref "C136")
      (value "100n/RF")
      (footprint "eagle-import:C0402")
      (libsource (lib "eagle-import") (part "C-EU?{colon}2C0402"))
    )
    (comp (ref "C137")
      (value "1u")
      (footprint "eagle-import:C0402")
      (libsource (lib "eagle-import") (part "C-EU?{colon}2C0402"))
    )
    (comp (ref "C138")
      (value "1u")
      (footprint "eagle-import:C0402")
      (libsource (lib "eagle-import") (part "C-EU?{colon}2C0402"))
    )
    (comp (ref "C139")
      (value "100n")
      (footprint "eagle-import:C0402")
      (libsource (lib "eagle-import") (part "C-EU?{colon}2C0402"))
    )
    (comp (ref "C140")
      (value "100n")
      (footprint "eagle-import:C0402")
      (libsource (lib "eagle-import") (part "C-EU?{colon}2C0402"))
    )
    (comp (ref "C141")
      (value "10n")
      (footprint "eagle-import:C0402")
      (libsource (lib "eagle-import") (part "C-EU?{colon}2C0402"))
    )
    (comp (ref "C142")
      (value "10n")
      (footprint "eagle-import:C0402")
      (libsource (lib "eagle-import") (part "C-EU?{colon}2C0402"))
    )
    (comp (ref "C143")
      (value "10n")
      (footprint "eagle-import:C0402")
      (libsource (lib "eagle-import") (part "C-EU?{colon}2C0402"))
    )
    (comp (ref "C144")
      (value "DNP")
      (footprint "eagle-import:C0402")
      (libsource (lib "eagle-import") (part "C-EU?{colon}2C0402"))
    )
    (comp (ref "C145")
      (value "1u")
      (footprint "eagle-import:C0402")
      (libsource (lib "eagle-import") (part "C-EU?{colon}2C0402"))
    )
    (comp (ref "C146")
      (value "100n/RF")
      (footprint "eagle-import:C0402")
      (libsource (lib "eagle-import") (part "C-EU?{colon}2C0402"))
    )
    (comp (ref "C147")
      (value "100n/RF")
      (footprint "eagle-import:C0402")
      (libsource (lib "eagle-import") (part "C-EU?{colon}2C0402"))
    )
    (comp (ref "C148")
      (value "10n")
      (footprint "eagle-import:C0402")
      (libsource (lib "eagle-import") (part "C-EU?{colon}2C0402"))
    )
    (comp (ref "C149")
      (value "DNP")
      (footprint "eagle-import:C0402")
      (libsource (lib "eagle-import") (part "C-EU?{colon}2C0402"))
    )
    (comp (ref "C150")
      (value "DNP")
      (footprint "eagle-import:C0402")
      (libsource (lib "eagle-import") (part "C-EU?{colon}2C0402"))
    )
    (comp (ref "C151")
      (value "100n")
      (footprint "eagle-import:C0402")
      (libsource (lib "eagle-import") (part "C-EU?{colon}2C0402"))
    )
    (comp (ref "C152")
      (value "100n")
      (footprint "eagle-import:C0402")
      (libsource (lib "eagle-import") (part "C-EU?{colon}2C0402"))
    )
    (comp (ref "C153")
      (value "100n")
      (footprint "eagle-import:C0402")
      (libsource (lib "eagle-import") (part "C-EU?{colon}2C0402"))
    )
    (comp (ref "C154")
      (value "100n")
      (footprint "eagle-import:C0402")
      (libsource (lib "eagle-import") (part "C-EU?{colon}2C0402"))
    )
    (comp (ref "C155")
      (value "100n")
      (footprint "eagle-import:C0402")
      (libsource (lib "eagle-import") (part "C-EU?{colon}2C0402"))
    )
    (comp (ref "C156")
      (value "100n")
      (footprint "eagle-import:C0402")
      (libsource (lib "eagle-import") (part "C-EU?{colon}2C0402"))
    )
    (comp (ref "C157")
      (value "10n")
      (footprint "eagle-import:C0402")
      (libsource (lib "eagle-import") (part "C-EU?{colon}2C0402"))
    )
    (comp (ref "C158")
      (value "330p")
      (footprint "eagle-import:C0402")
      (libsource (lib "eagle-import") (part "C-EU?{colon}2C0402"))
    )
    (comp (ref "C159")
      (value "100n")
      (footprint "eagle-import:C0402")
      (libsource (lib "eagle-import") (part "C-EU?{colon}2C0402"))
    )
    (comp (ref "C160")
      (value "10n")
      (footprint "eagle-import:C0402")
      (libsource (lib "eagle-import") (part "C-EU?{colon}2C0402"))
    )
    (comp (ref "C161")
      (value "120p")
      (footprint "eagle-import:C0402")
      (libsource (lib "eagle-import") (part "C-EU?{colon}2C0402"))
    )
    (comp (ref "C162")
      (value "330p")
      (footprint "eagle-import:C0402")
      (libsource (lib "eagle-import") (part "C-EU?{colon}2C0402"))
    )
    (comp (ref "C163")
      (value "330p")
      (footprint "eagle-import:C0402")
      (libsource (lib "eagle-import") (part "C-EU?{colon}2C0402"))
    )
    (comp (ref "C164")
      (value "330p")
      (footprint "eagle-import:C0402")
      (libsource (lib "eagle-import") (part "C-EU?{colon}2C0402"))
    )
    (comp (ref "C165")
      (value "150p")
      (footprint "eagle-import:C0402")
      (libsource (lib "eagle-import") (part "C-EU?{colon}2C0402"))
    )
    (comp (ref "C166")
      (value "1u")
      (footprint "eagle-import:C0402")
      (libsource (lib "eagle-import") (part "C-EU?{colon}2C0402"))
    )
    (comp (ref "C167")
      (value "33p")
      (footprint "eagle-import:C0402")
      (libsource (lib "eagle-import") (part "C-EU?{colon}2C0402"))
    )
    (comp (ref "C168")
      (value "1u")
      (footprint "eagle-import:C0402")
      (libsource (lib "eagle-import") (part "C-EU?{colon}2C0402"))
    )
    (comp (ref "C169")
      (value "100n")
      (footprint "eagle-import:C0402")
      (libsource (lib "eagle-import") (part "C-EU?{colon}2C0402"))
    )
    (comp (ref "IC27")
      (value "LT5560")
      (footprint "eagle-import:SON50P300X300X80-9T165X238")
      (libsource (lib "eagle-import") (part "LT5560"))
    )
    (comp (ref "IC28")
      (value "THS4521IDGKR")
      (footprint "eagle-import:SOP65P490X110-8N")
      (libsource (lib "eagle-import") (part "THS4521IDGKR"))
    )
    (comp (ref "IC29")
      (value "ADL5801")
      (footprint "eagle-import:QFN50P400X400X100-25T250N")
      (libsource (lib "eagle-import") (part "ADL5801"))
    )
    (comp (ref "IC30")
      (value "NCP702-1.8")
      (footprint "eagle-import:SOT95P240X110-5")
      (libsource (lib "eagle-import") (part "NCP702"))
    )
    (comp (ref "IC31")
      (value "MCP33131D-10-E/MS")
      (footprint "eagle-import:SOP50P490X110-10N")
      (libsource (lib "eagle-import") (part "MCP33131D-10-E/MS"))
    )
    (comp (ref "J3")
      (value "BU-1420701851")
      (footprint "eagle-import:BU-1420701851")
      (libsource (lib "eagle-import") (part "BU-1420701851"))
    )
    (comp (ref "L38")
      (value "330n")
      (footprint "eagle-import:L0402")
      (libsource (lib "eagle-import") (part "INDUCTOR0402"))
    )
    (comp (ref "L39")
      (value "330n")
      (footprint "eagle-import:L0402")
      (libsource (lib "eagle-import") (part "INDUCTOR0402"))
    )
    (comp (ref "L40")
      (value "330n")
      (footprint "eagle-import:L0402")
      (libsource (lib "eagle-import") (part "INDUCTOR0402"))
    )
    (comp (ref "L41")
      (value "330n")
      (footprint "eagle-import:L0402")
      (libsource (lib "eagle-import") (part "INDUCTOR0402"))
    )
    (comp (ref "L42")
      (value "68n")
      (footprint "eagle-import:L0402")
      (libsource (lib "eagle-import") (part "INDUCTOR0402"))
    )
    (comp (ref "L43")
      (value "68n")
      (footprint "eagle-import:L0402")
      (libsource (lib "eagle-import") (part "INDUCTOR0402"))
    )
    (comp (ref "L44")
      (value "33n")
      (footprint "eagle-import:L0402")
      (libsource (lib "eagle-import") (part "INDUCTOR0402"))
    )
    (comp (ref "L45")
      (value "33n")
      (footprint "eagle-import:L0402")
      (libsource (lib "eagle-import") (part "INDUCTOR0402"))
    )
    (comp (ref "L54")
      (value "Ferrite")
      (footprint "eagle-import:R0402")
      (libsource (lib "eagle-import") (part "FERRITE"))
    )
    (comp (ref "L55")
      (value "Ferrite")
      (footprint "eagle-import:R0402")
      (libsource (lib "eagle-import") (part "FERRITE"))
    )
    (comp (ref "L56")
      (value "Ferrite")
      (footprint "eagle-import:R0402")
      (libsource (lib "eagle-import") (part "FERRITE"))
    )
    (comp (ref "L57")
      (value "Ferrite")
      (footprint "eagle-import:R0402")
      (libsource (lib "eagle-import") (part "FERRITE"))
    )
    (comp (ref "L58")
      (value "Ferrite")
      (footprint "eagle-import:R0402")
      (libsource (lib "eagle-import") (part "FERRITE"))
    )
    (comp (ref "R40")
      (value "PAT0816-C-3DB-T5")
      (footprint "eagle-import:PAT0816")
      (libsource (lib "eagle-import") (part "PAT0816-C-3DB-T5"))
    )
    (comp (ref "R47")
      (value "DNP")
      (footprint "eagle-import:PAT0816")
      (libsource (lib "eagle-import") (part "PAT0816-C-3DB-T5"))
    )
    (comp (ref "R72")
      (value "49R9")
      (footprint "eagle-import:R0402")
      (libsource (lib "eagle-import") (part "R-EU_R0402"))
    )
    (comp (ref "R73")
      (value "49R9")
      (footprint "eagle-import:R0402")
      (libsource (lib "eagle-import") (part "R-EU_R0402"))
    )
    (comp (ref "R76")
      (value "49R9")
      (footprint "eagle-import:R0402")
      (libsource (lib "eagle-import") (part "R-EU_R0402"))
    )
    (comp (ref "R80")
      (value "220")
      (footprint "eagle-import:R0402")
      (libsource (lib "eagle-import") (part "R-EU_R0402"))
    )
    (comp (ref "R81")
      (value "220")
      (footprint "eagle-import:R0402")
      (libsource (lib "eagle-import") (part "R-EU_R0402"))
    )
    (comp (ref "R82")
      (value "6k8")
      (footprint "eagle-import:R0402")
      (libsource (lib "eagle-import") (part "R-EU_R0402"))
    )
    (comp (ref "R83")
      (value "6k8")
      (footprint "eagle-import:R0402")
      (libsource (lib "eagle-import") (part "R-EU_R0402"))
    )
    (comp (ref "R84")
      (value "DNP")
      (footprint "eagle-import:R0402")
      (libsource (lib "eagle-import") (part "R-EU_R0402"))
    )
    (comp (ref "R85")
      (value "220")
      (footprint "eagle-import:R0402")
      (libsource (lib "eagle-import") (part "R-EU_R0402"))
    )
    (comp (ref "R86")
      (value "220")
      (footprint "eagle-import:R0402")
      (libsource (lib "eagle-import") (part "R-EU_R0402"))
    )
    (comp (ref "R87")
      (value "1k")
      (footprint "eagle-import:R0402")
      (libsource (lib "eagle-import") (part "R-EU_R0402"))
    )
    (comp (ref "R88")
      (value "220")
      (footprint "eagle-import:R0402")
      (libsource (lib "eagle-import") (part "R-EU_R0402"))
    )
    (comp (ref "R89")
      (value "220")
      (footprint "eagle-import:R0402")
      (libsource (lib "eagle-import") (part "R-EU_R0402"))
    )
    (comp (ref "R90")
      (value "56")
      (footprint "eagle-import:R0402")
      (libsource (lib "eagle-import") (part "R-EU_R0402"))
    )
    (comp (ref "R91")
      (value "20")
      (footprint "eagle-import:R0402")
      (libsource (lib "eagle-import") (part "R-EU_R0402"))
    )
    (comp (ref "R92")
      (value "20")
      (footprint "eagle-import:R0402")
      (libsource (lib "eagle-import") (part "R-EU_R0402"))
    )
    (comp (ref "R93")
      (value "56")
      (footprint "eagle-import:R0402")
      (libsource (lib "eagle-import") (part "R-EU_R0402"))
    )
    (comp (ref "T2")
      (value "B012-617DB-1-63-B331")
      (footprint "eagle-import:EASTEVER_BALUN")
      (libsource (lib "eagle-import") (part "B012-617DB-1-63-B331"))
    )
    (comp (ref "TP18")
      (value "TPB1,27")
      (footprint "eagle-import:B1,27")
      (libsource (lib "eagle-import") (part "TPB1,27"))
    )
    (comp (ref "C29")
      (value "100n")
      (footprint "eagle-import:C0402")
      (libsource (lib "eagle-import") (part "C-EU?{colon}2C0402"))
    )
    (comp (ref "C30")
      (value "10n")
      (footprint "eagle-import:C0402")
      (libsource (lib "eagle-import") (part "C-EU?{colon}2C0402"))
    )
    (comp (ref "C31")
      (value "100n")
      (footprint "eagle-import:C0402")
      (libsource (lib "eagle-import") (part "C-EU?{colon}2C0402"))
    )
    (comp (ref "C32")
      (value "100n")
      (footprint "eagle-import:C0402")
      (libsource (lib "eagle-import") (part "C-EU?{colon}2C0402"))
    )
    (comp (ref "C33")
      (value "100n")
      (footprint "eagle-import:C0402")
      (libsource (lib "eagle-import") (part "C-EU?{colon}2C0402"))
    )
    (comp (ref "C34")
      (value "100n")
      (footprint "eagle-import:C0402")
      (libsource (lib "eagle-import") (part "C-EU?{colon}2C0402"))
    )
    (comp (ref "C35")
      (value "DNP")
      (footprint "eagle-import:C0402")
      (libsource (lib "eagle-import") (part "C-EU?{colon}2C0402"))
    )
    (comp (ref "C36")
      (value "DNP")
      (footprint "eagle-import:C0402")
      (libsource (lib "eagle-import") (part "C-EU?{colon}2C0402"))
    )
    (comp (ref "C37")
      (value "DNP")
      (footprint "eagle-import:C0402")
      (libsource (lib "eagle-import") (part "C-EU?{colon}2C0402"))
    )
    (comp (ref "C38")
      (value "56p")
      (footprint "eagle-import:C0402")
      (libsource (lib "eagle-import") (part "C-EU?{colon}2C0402"))
    )
    (comp (ref "C39")
      (value "10n")
      (footprint "eagle-import:C0402")
      (libsource (lib "eagle-import") (part "C-EU?{colon}2C0402"))
    )
    (comp (ref "C40")
      (value "DNP")
      (footprint "eagle-import:C0402")
      (libsource (lib "eagle-import") (part "C-EU?{colon}2C0402"))
    )
    (comp (ref "C41")
      (value "DNP")
      (footprint "eagle-import:C0402")
      (libsource (lib "eagle-import") (part "C-EU?{colon}2C0402"))
    )
    (comp (ref "C42")
      (value "DNP")
      (footprint "eagle-import:C0402")
      (libsource (lib "eagle-import") (part "C-EU?{colon}2C0402"))
    )
    (comp (ref "C43")
      (value "180p")
      (footprint "eagle-import:C0402")
      (libsource (lib "eagle-import") (part "C-EU?{colon}2C0402"))
    )
    (comp (ref "C44")
      (value "DNP")
      (footprint "eagle-import:C0402")
      (libsource (lib "eagle-import") (part "C-EU?{colon}2C0402"))
    )
    (comp (ref "C45")
      (value "DNP")
      (footprint "eagle-import:C0402")
      (libsource (lib "eagle-import") (part "C-EU?{colon}2C0402"))
    )
    (comp (ref "C46")
      (value "DNP")
      (footprint "eagle-import:C0402")
      (libsource (lib "eagle-import") (part "C-EU?{colon}2C0402"))
    )
    (comp (ref "C47")
      (value "56p")
      (footprint "eagle-import:C0402")
      (libsource (lib "eagle-import") (part "C-EU?{colon}2C0402"))
    )
    (comp (ref "C48")
      (value "100n")
      (footprint "eagle-import:C0402")
      (libsource (lib "eagle-import") (part "C-EU?{colon}2C0402"))
    )
    (comp (ref "IC7")
      (value "SI5351C")
      (footprint "eagle-import:QFN50P400X400X90-21T270N")
      (libsource (lib "eagle-import") (part "SI5351C"))
    )
    (comp (ref "L10")
      (value "Ferrite")
      (footprint "eagle-import:R0402")
      (libsource (lib "eagle-import") (part "FERRITE"))
    )
    (comp (ref "L14")
      (value "330n")
      (footprint "eagle-import:L0402")
      (libsource (lib "eagle-import") (part "INDUCTOR0402"))
    )
    (comp (ref "L18")
      (value "330n")
      (footprint "eagle-import:L0402")
      (libsource (lib "eagle-import") (part "INDUCTOR0402"))
    )
    (comp (ref "R6")
      (value "10k")
      (footprint "eagle-import:R0402")
      (libsource (lib "eagle-import") (part "R-EU_R0402"))
    )
    (comp (ref "R7")
      (value "100")
      (footprint "eagle-import:R0402")
      (libsource (lib "eagle-import") (part "R-EU_R0402"))
    )
    (comp (ref "R8")
      (value "62")
      (footprint "eagle-import:R0402")
      (libsource (lib "eagle-import") (part "R-EU_R0402"))
    )
    (comp (ref "R9")
      (value "100")
      (footprint "eagle-import:R0402")
      (libsource (lib "eagle-import") (part "R-EU_R0402"))
    )
    (comp (ref "R176")
      (value "0")
      (footprint "eagle-import:R0402")
      (libsource (lib "eagle-import") (part "R-EU_R0402"))
    )
    (comp (ref "R177")
      (value "0")
      (footprint "eagle-import:R0402")
      (libsource (lib "eagle-import") (part "R-EU_R0402"))
    )
    (comp (ref "R178")
      (value "0")
      (footprint "eagle-import:R0402")
      (libsource (lib "eagle-import") (part "R-EU_R0402"))
    )
    (comp (ref "R179")
      (value "0")
      (footprint "eagle-import:R0402")
      (libsource (lib "eagle-import") (part "R-EU_R0402"))
    )
    (comp (ref "R180")
      (value "0")
      (footprint "eagle-import:R0402")
      (libsource (lib "eagle-import") (part "R-EU_R0402"))
    )
    (comp (ref "R181")
      (value "0")
      (footprint "eagle-import:R0402")
      (libsource (lib "eagle-import") (part "R-EU_R0402"))
    )
    (comp (ref "X1")
      (value "SMA_CONNECTOR")
      (footprint "eagle-import:J502-ND-142-0711-821_826")
      (libsource (lib "eagle-import") (part "SMA_CONNECTOR"))
    )
    (comp (ref "X2")
      (value "SMA_CONNECTOR")
      (footprint "eagle-import:J502-ND-142-0711-821_826")
      (libsource (lib "eagle-import") (part "SMA_CONNECTOR"))
    )
    (comp (ref "Y1")
      (value "DSB221SDN/26MHz")
      (footprint "eagle-import:2.5X2.0_KXO-86-TCXO")
      (libsource (lib "eagle-import") (part "KXO-TCXO-CMOS-86"))
    )
    (comp (ref "C223")
      (value "100p")
      (footprint "eagle-import:C0402")
      (libsource (lib "eagle-import") (part "C-EU?{colon}2C0402"))
    )
    (comp (ref "C224")
      (value "100p")
      (footprint "eagle-import:C0402")
      (libsource (lib "eagle-import") (part "C-EU?{colon}2C0402"))
    )
    (comp (ref "C225")
      (value "100p")
      (footprint "eagle-import:C0402")
      (libsource (lib "eagle-import") (part "C-EU?{colon}2C0402"))
    )
    (comp (ref "C226")
      (value "100p")
      (footprint "eagle-import:C0402")
      (libsource (lib "eagle-import") (part "C-EU?{colon}2C0402"))
    )
    (comp (ref "C227")
      (value "100p")
      (footprint "eagle-import:C0402")
      (libsource (lib "eagle-import") (part "C-EU?{colon}2C0402"))
    )
    (comp (ref "C228")
      (value "100p")
      (footprint "eagle-import:C0402")
      (libsource (lib "eagle-import") (part "C-EU?{colon}2C0402"))
    )
    (comp (ref "C229")
      (value "100p")
      (footprint "eagle-import:C0402")
      (libsource (lib "eagle-import") (part "C-EU?{colon}2C0402"))
    )
    (comp (ref "C230")
      (value "100p")
      (footprint "eagle-import:C0402")
      (libsource (lib "eagle-import") (part "C-EU?{colon}2C0402"))
    )
    (comp (ref "JP2")
      (value "DNP")
      (footprint "eagle-import:2X10")
      (libsource (lib "eagle-import") (part "PINHD-2X10"))
    )
    (comp (ref "LED2")
      (value "Green")
      (footprint "eagle-import:CHIPLED_0603")
      (libsource (lib "eagle-import") (part "LEDCHIPLED_0603"))
    )
    (comp (ref "LED3")
      (value "Red")
      (footprint "eagle-import:CHIPLED_0603")
      (libsource (lib "eagle-import") (part "LEDCHIPLED_0603"))
    )
    (comp (ref "LED4")
      (value "Red")
      (footprint "eagle-import:CHIPLED_0603")
      (libsource (lib "eagle-import") (part "LEDCHIPLED_0603"))
    )
    (comp (ref "LED5")
      (value "Red")
      (footprint "eagle-import:CHIPLED_0603")
      (libsource (lib "eagle-import") (part "LEDCHIPLED_0603"))
    )
    (comp (ref "LED6")
      (value "Green")
      (footprint "eagle-import:CHIPLED_0603")
      (libsource (lib "eagle-import") (part "LEDCHIPLED_0603"))
    )
    (comp (ref "LED7")
      (value "Green")
      (footprint "eagle-import:CHIPLED_0603")
      (libsource (lib "eagle-import") (part "LEDCHIPLED_0603"))
    )
    (comp (ref "LED8")
      (value "Green")
      (footprint "eagle-import:CHIPLED_0603")
      (libsource (lib "eagle-import") (part "LEDCHIPLED_0603"))
    )
    (comp (ref "LED9")
      (value "Green")
      (footprint "eagle-import:CHIPLED_0603")
      (libsource (lib "eagle-import") (part "LEDCHIPLED_0603"))
    )
    (comp (ref "LED10")
      (value "Green")
      (footprint "eagle-import:CHIPLED_0603")
      (libsource (lib "eagle-import") (part "LEDCHIPLED_0603"))
    )
    (comp (ref "R130")
      (value "10k")
      (footprint "eagle-import:R0402")
      (libsource (lib "eagle-import") (part "R-EU_R0402"))
    )
    (comp (ref "R131")
      (value "10k")
      (footprint "eagle-import:R0402")
      (libsource (lib "eagle-import") (part "R-EU_R0402"))
    )
    (comp (ref "R132")
      (value "10k")
      (footprint "eagle-import:R0402")
      (libsource (lib "eagle-import") (part "R-EU_R0402"))
    )
    (comp (ref "R133")
      (value "10k")
      (footprint "eagle-import:R0402")
      (libsource (lib "eagle-import") (part "R-EU_R0402"))
    )
    (comp (ref "R134")
      (value "330")
      (footprint "eagle-import:R0402")
      (libsource (lib "eagle-import") (part "R-EU_R0402"))
    )
    (comp (ref "R135")
      (value "330")
      (footprint "eagle-import:R0402")
      (libsource (lib "eagle-import") (part "R-EU_R0402"))
    )
    (comp (ref "R136")
      (value "330")
      (footprint "eagle-import:R0402")
      (libsource (lib "eagle-import") (part "R-EU_R0402"))
    )
    (comp (ref "R137")
      (value "330")
      (footprint "eagle-import:R0402")
      (libsource (lib "eagle-import") (part "R-EU_R0402"))
    )
    (comp (ref "R138")
      (value "330")
      (footprint "eagle-import:R0402")
      (libsource (lib "eagle-import") (part "R-EU_R0402"))
    )
    (comp (ref "R139")
      (value "330")
      (footprint "eagle-import:R0402")
      (libsource (lib "eagle-import") (part "R-EU_R0402"))
    )
    (comp (ref "R140")
      (value "330")
      (footprint "eagle-import:R0402")
      (libsource (lib "eagle-import") (part "R-EU_R0402"))
    )
    (comp (ref "R141")
      (value "330")
      (footprint "eagle-import:R0402")
      (libsource (lib "eagle-import") (part "R-EU_R0402"))
    )
    (comp (ref "R142")
      (value "330")
      (footprint "eagle-import:R0402")
      (libsource (lib "eagle-import") (part "R-EU_R0402"))
    )
    (comp (ref "R143")
      (value "10k")
      (footprint "eagle-import:R0402")
      (libsource (lib "eagle-import") (part "R-EU_R0402"))
    )
    (comp (ref "R144")
      (value "10k")
      (footprint "eagle-import:R0402")
      (libsource (lib "eagle-import") (part "R-EU_R0402"))
    )
    (comp (ref "R145")
      (value "10k")
      (footprint "eagle-import:R0402")
      (libsource (lib "eagle-import") (part "R-EU_R0402"))
    )
    (comp (ref "R146")
      (value "10k")
      (footprint "eagle-import:R0402")
      (libsource (lib "eagle-import") (part "R-EU_R0402"))
    )
    (comp (ref "C49")
      (value "10u")
      (footprint "eagle-import:C1206")
      (libsource (lib "eagle-import") (part "C-EUC1206"))
    )
    (comp (ref "C50")
      (value "1u")
      (footprint "eagle-import:C0603")
      (libsource (lib "eagle-import") (part "C-EU?{colon}1C0603"))
    )
    (comp (ref "C51")
      (value "10n")
      (footprint "eagle-import:C0402")
      (libsource (lib "eagle-import") (part "C-EU?{colon}2C0402"))
    )
    (comp (ref "C52")
      (value "1u")
      (footprint "eagle-import:C0603")
      (libsource (lib "eagle-import") (part "C-EU?{colon}1C0603"))
    )
    (comp (ref "C53")
      (value "10u")
      (footprint "eagle-import:C1206")
      (libsource (lib "eagle-import") (part "C-EUC1206"))
    )
    (comp (ref "C54")
      (value "100n")
      (footprint "eagle-import:C0402")
      (libsource (lib "eagle-import") (part "C-EU?{colon}2C0402"))
    )
    (comp (ref "C55")
      (value "100n")
      (footprint "eagle-import:C0402")
      (libsource (lib "eagle-import") (part "C-EU?{colon}2C0402"))
    )
    (comp (ref "C56")
      (value "100n")
      (footprint "eagle-import:C0402")
      (libsource (lib "eagle-import") (part "C-EU?{colon}2C0402"))
    )
    (comp (ref "C57")
      (value "100n")
      (footprint "eagle-import:C0402")
      (libsource (lib "eagle-import") (part "C-EU?{colon}2C0402"))
    )
    (comp (ref "C58")
      (value "1u")
      (footprint "eagle-import:C0402")
      (libsource (lib "eagle-import") (part "C-EU?{colon}2C0402"))
    )
    (comp (ref "C59")
      (value "1u")
      (footprint "eagle-import:C0402")
      (libsource (lib "eagle-import") (part "C-EU?{colon}2C0402"))
    )
    (comp (ref "C60")
      (value "1u")
      (footprint "eagle-import:C0402")
      (libsource (lib "eagle-import") (part "C-EU?{colon}2C0402"))
    )
    (comp (ref "C61")
      (value "100n")
      (footprint "eagle-import:C0402")
      (libsource (lib "eagle-import") (part "C-EU?{colon}2C0402"))
    )
    (comp (ref "C62")
      (value "100n")
      (footprint "eagle-import:C0402")
      (libsource (lib "eagle-import") (part "C-EU?{colon}2C0402"))
    )
    (comp (ref "C63")
      (value "180p")
      (footprint "eagle-import:C0402")
      (libsource (lib "eagle-import") (part "C-EU?{colon}2C0402"))
    )
    (comp (ref "C64")
      (value "100n")
      (footprint "eagle-import:C0402")
      (libsource (lib "eagle-import") (part "C-EU?{colon}2C0402"))
    )
    (comp (ref "C65")
      (value "100n/RF")
      (footprint "eagle-import:C0402")
      (libsource (lib "eagle-import") (part "C-EU?{colon}2C0402"))
    )
    (comp (ref "C66")
      (value "3n3")
      (footprint "eagle-import:C0402")
      (libsource (lib "eagle-import") (part "C-EU?{colon}2C0402"))
    )
    (comp (ref "C67")
      (value "18p")
      (footprint "eagle-import:C0402")
      (libsource (lib "eagle-import") (part "C-EU?{colon}2C0402"))
    )
    (comp (ref "C68")
      (value "100n/RF")
      (footprint "eagle-import:C0402")
      (libsource (lib "eagle-import") (part "C-EU?{colon}2C0402"))
    )
    (comp (ref "C263")
      (value "100p")
      (footprint "eagle-import:C0402")
      (libsource (lib "eagle-import") (part "C-EU?{colon}2C0402"))
    )
    (comp (ref "C264")
      (value "100p")
      (footprint "eagle-import:C0402")
      (libsource (lib "eagle-import") (part "C-EU?{colon}2C0402"))
    )
    (comp (ref "C265")
      (value "100p")
      (footprint "eagle-import:C0402")
      (libsource (lib "eagle-import") (part "C-EU?{colon}2C0402"))
    )
    (comp (ref "C266")
      (value "100p")
      (footprint "eagle-import:C0402")
      (libsource (lib "eagle-import") (part "C-EU?{colon}2C0402"))
    )
    (comp (ref "C267")
      (value "100p")
      (footprint "eagle-import:C0402")
      (libsource (lib "eagle-import") (part "C-EU?{colon}2C0402"))
    )
    (comp (ref "C268")
      (value "100p")
      (footprint "eagle-import:C0402")
      (libsource (lib "eagle-import") (part "C-EU?{colon}2C0402"))
    )
    (comp (ref "C271")
      (value "100p")
      (footprint "eagle-import:C0402")
      (libsource (lib "eagle-import") (part "C-EU?{colon}2C0402"))
    )
    (comp (ref "C272")
      (value "100p")
      (footprint "eagle-import:C0402")
      (libsource (lib "eagle-import") (part "C-EU?{colon}2C0402"))
    )
    (comp (ref "C273")
      (value "100p")
      (footprint "eagle-import:C0402")
      (libsource (lib "eagle-import") (part "C-EU?{colon}2C0402"))
    )
    (comp (ref "C274")
      (value "100p")
      (footprint "eagle-import:C0402")
      (libsource (lib "eagle-import") (part "C-EU?{colon}2C0402"))
    )
    (comp (ref "IC8")
      (value "AP2114H")
      (footprint "eagle-import:SOT230P700X180-4")
      (libsource (lib "eagle-import") (part "AP2114H"))
    )
    (comp (ref "IC9")
      (value "NCP702-3.3")
      (footprint "eagle-import:SOT95P240X110-5")
      (libsource (lib "eagle-import") (part "NCP702"))
    )
    (comp (ref "IC10")
      (value "MAX2871")
      (footprint "eagle-import:QFN50P500X500X80-33T310")
      (libsource (lib "eagle-import") (part "MAX2871"))
    )
    (comp (ref "IC11")
      (value "RFSW6042")
      (footprint "eagle-import:QFN40P180X180X55-13T76N")
      (libsource (lib "eagle-import") (part "RFSW6042"))
    )
    (comp (ref "IC12")
      (value "RFSW6042")
      (footprint "eagle-import:QFN40P180X180X55-13T76N")
      (libsource (lib "eagle-import") (part "RFSW6042"))
    )
    (comp (ref "L19")
      (value "Ferrite")
      (footprint "eagle-import:R0402")
      (libsource (lib "eagle-import") (part "FERRITE"))
    )
    (comp (ref "L20")
      (value "Ferrite")
      (footprint "eagle-import:R0402")
      (libsource (lib "eagle-import") (part "FERRITE"))
    )
    (comp (ref "L64")
      (value "Ferrite")
      (footprint "eagle-import:R0402")
      (libsource (lib "eagle-import") (part "FERRITE"))
    )
    (comp (ref "LP1")
      (value "LP0603A0947ANTR")
      (footprint "eagle-import:FILTRDFN160X84X70-4N")
      (libsource (lib "eagle-import") (part "LP0603A"))
    )
    (comp (ref "LP2")
      (value "LP0603N3500ANTR")
      (footprint "eagle-import:FILTRDFN160X84X70-4N")
      (libsource (lib "eagle-import") (part "LP0603A"))
    )
    (comp (ref "LP3")
      (value "LP0603A1880ANTR")
      (footprint "eagle-import:FILTRDFN160X84X70-4N")
      (libsource (lib "eagle-import") (part "LP0603A"))
    )
    (comp (ref "R10")
      (value "5k1")
      (footprint "eagle-import:R0402")
      (libsource (lib "eagle-import") (part "R-EU_R0402"))
    )
    (comp (ref "R11")
      (value "10k")
      (footprint "eagle-import:R0402")
      (libsource (lib "eagle-import") (part "R-EU_R0402"))
    )
    (comp (ref "R12")
      (value "49R9")
      (footprint "eagle-import:R0402")
      (libsource (lib "eagle-import") (part "R-EU_R0402"))
    )
    (comp (ref "R13")
      (value "49R9")
      (footprint "eagle-import:R0402")
      (libsource (lib "eagle-import") (part "R-EU_R0402"))
    )
    (comp (ref "R14")
      (value "49R9")
      (footprint "eagle-import:R0402")
      (libsource (lib "eagle-import") (part "R-EU_R0402"))
    )
    (comp (ref "R15")
      (value "1k8")
      (footprint "eagle-import:R0402")
      (libsource (lib "eagle-import") (part "R-EU_R0402"))
    )
    (comp (ref "R16")
      (value "82")
      (footprint "eagle-import:R0402")
      (libsource (lib "eagle-import") (part "R-EU_R0402"))
    )
    (comp (ref "R17")
      (value "330")
      (footprint "eagle-import:R0402")
      (libsource (lib "eagle-import") (part "R-EU_R0402"))
    )
    (comp (ref "R18")
      (value "10k")
      (footprint "eagle-import:R0402")
      (libsource (lib "eagle-import") (part "R-EU_R0402"))
    )
    (comp (ref "R19")
      (value "10k")
      (footprint "eagle-import:R0402")
      (libsource (lib "eagle-import") (part "R-EU_R0402"))
    )
    (comp (ref "R20")
      (value "10k")
      (footprint "eagle-import:R0402")
      (libsource (lib "eagle-import") (part "R-EU_R0402"))
    )
    (comp (ref "R21")
      (value "10k")
      (footprint "eagle-import:R0402")
      (libsource (lib "eagle-import") (part "R-EU_R0402"))
    )
    (comp (ref "R22")
      (value "10k")
      (footprint "eagle-import:R0402")
      (libsource (lib "eagle-import") (part "R-EU_R0402"))
    )
    (comp (ref "R23")
      (value "10k")
      (footprint "eagle-import:R0402")
      (libsource (lib "eagle-import") (part "R-EU_R0402"))
    )
    (comp (ref "R24")
      (value "10k")
      (footprint "eagle-import:R0402")
      (libsource (lib "eagle-import") (part "R-EU_R0402"))
    )
    (comp (ref "R25")
      (value "10k")
      (footprint "eagle-import:R0402")
      (libsource (lib "eagle-import") (part "R-EU_R0402"))
    )
    (comp (ref "R163")
      (value "10k")
      (footprint "eagle-import:R0402")
      (libsource (lib "eagle-import") (part "R-EU_R0402"))
    )
    (comp (ref "R164")
      (value "100")
      (footprint "eagle-import:R0402")
      (libsource (lib "eagle-import") (part "R-EU_R0402"))
    )
    (comp (ref "R165")
      (value "10k")
      (footprint "eagle-import:R0402")
      (libsource (lib "eagle-import") (part "R-EU_R0402"))
    )
    (comp (ref "R166")
      (value "10k")
      (footprint "eagle-import:R0402")
      (libsource (lib "eagle-import") (part "R-EU_R0402"))
    )
    (comp (ref "R167")
      (value "100")
      (footprint "eagle-import:R0402")
      (libsource (lib "eagle-import") (part "R-EU_R0402"))
    )
    (comp (ref "R170")
      (value "100")
      (footprint "eagle-import:R0402")
      (libsource (lib "eagle-import") (part "R-EU_R0402"))
    )
    (comp (ref "R171")
      (value "100")
      (footprint "eagle-import:R0402")
      (libsource (lib "eagle-import") (part "R-EU_R0402"))
    )
    (comp (ref "TP13")
      (value "TPB1,27")
      (footprint "eagle-import:B1,27")
      (libsource (lib "eagle-import") (part "TPB1,27"))
    )
    (comp (ref "TP14")
      (value "TPB1,27")
      (footprint "eagle-import:B1,27")
      (libsource (lib "eagle-import") (part "TPB1,27"))
    )
    (comp (ref "C78")
      (value "10u")
      (footprint "eagle-import:C1206")
      (libsource (lib "eagle-import") (part "C-EUC1206"))
    )
    (comp (ref "C79")
      (value "1u")
      (footprint "eagle-import:C0603")
      (libsource (lib "eagle-import") (part "C-EU?{colon}1C0603"))
    )
    (comp (ref "C80")
      (value "10n")
      (footprint "eagle-import:C0402")
      (libsource (lib "eagle-import") (part "C-EU?{colon}2C0402"))
    )
    (comp (ref "C81")
      (value "1u")
      (footprint "eagle-import:C0603")
      (libsource (lib "eagle-import") (part "C-EU?{colon}1C0603"))
    )
    (comp (ref "C82")
      (value "10u")
      (footprint "eagle-import:C1206")
      (libsource (lib "eagle-import") (part "C-EUC1206"))
    )
    (comp (ref "C83")
      (value "100n")
      (footprint "eagle-import:C0402")
      (libsource (lib "eagle-import") (part "C-EU?{colon}2C0402"))
    )
    (comp (ref "C84")
      (value "100n")
      (footprint "eagle-import:C0402")
      (libsource (lib "eagle-import") (part "C-EU?{colon}2C0402"))
    )
    (comp (ref "C85")
      (value "100n")
      (footprint "eagle-import:C0402")
      (libsource (lib "eagle-import") (part "C-EU?{colon}2C0402"))
    )
    (comp (ref "C86")
      (value "100n")
      (footprint "eagle-import:C0402")
      (libsource (lib "eagle-import") (part "C-EU?{colon}2C0402"))
    )
    (comp (ref "C87")
      (value "1u")
      (footprint "eagle-import:C0402")
      (libsource (lib "eagle-import") (part "C-EU?{colon}2C0402"))
    )
    (comp (ref "C88")
      (value "1u")
      (footprint "eagle-import:C0402")
      (libsource (lib "eagle-import") (part "C-EU?{colon}2C0402"))
    )
    (comp (ref "C89")
      (value "1u")
      (footprint "eagle-import:C0402")
      (libsource (lib "eagle-import") (part "C-EU?{colon}2C0402"))
    )
    (comp (ref "C90")
      (value "180p")
      (footprint "eagle-import:C0402")
      (libsource (lib "eagle-import") (part "C-EU?{colon}2C0402"))
    )
    (comp (ref "C91")
      (value "100n")
      (footprint "eagle-import:C0402")
      (libsource (lib "eagle-import") (part "C-EU?{colon}2C0402"))
    )
    (comp (ref "C92")
      (value "3n3")
      (footprint "eagle-import:C0402")
      (libsource (lib "eagle-import") (part "C-EU?{colon}2C0402"))
    )
    (comp (ref "C93")
      (value "10n")
      (footprint "eagle-import:C0402")
      (libsource (lib "eagle-import") (part "C-EU?{colon}2C0402"))
    )
    (comp (ref "C94")
      (value "100n")
      (footprint "eagle-import:C0402")
      (libsource (lib "eagle-import") (part "C-EU?{colon}2C0402"))
    )
    (comp (ref "C95")
      (value "18p")
      (footprint "eagle-import:C0402")
      (libsource (lib "eagle-import") (part "C-EU?{colon}2C0402"))
    )
    (comp (ref "IC19")
      (value "AP2114H")
      (footprint "eagle-import:SOT230P700X180-4")
      (libsource (lib "eagle-import") (part "AP2114H"))
    )
    (comp (ref "IC20")
      (value "NCP702-3.3")
      (footprint "eagle-import:SOT95P240X110-5")
      (libsource (lib "eagle-import") (part "NCP702"))
    )
    (comp (ref "IC21")
      (value "MAX2871")
      (footprint "eagle-import:QFN50P500X500X80-33T310")
      (libsource (lib "eagle-import") (part "MAX2871"))
    )
    (comp (ref "L28")
      (value "Ferrite")
      (footprint "eagle-import:R0402")
      (libsource (lib "eagle-import") (part "FERRITE"))
    )
    (comp (ref "L29")
      (value "Ferrite")
      (footprint "eagle-import:R0402")
      (libsource (lib "eagle-import") (part "FERRITE"))
    )
    (comp (ref "L65")
      (value "Ferrite")
      (footprint "eagle-import:R0402")
      (libsource (lib "eagle-import") (part "FERRITE"))
    )
    (comp (ref "R30")
      (value "5k1")
      (footprint "eagle-import:R0402")
      (libsource (lib "eagle-import") (part "R-EU_R0402"))
    )
    (comp (ref "R31")
      (value "10k")
      (footprint "eagle-import:R0402")
      (libsource (lib "eagle-import") (part "R-EU_R0402"))
    )
    (comp (ref "R32")
      (value "49R9")
      (footprint "eagle-import:R0402")
      (libsource (lib "eagle-import") (part "R-EU_R0402"))
    )
    (comp (ref "R33")
      (value "49R9")
      (footprint "eagle-import:R0402")
      (libsource (lib "eagle-import") (part "R-EU_R0402"))
    )
    (comp (ref "R34")
      (value "49R9")
      (footprint "eagle-import:R0402")
      (libsource (lib "eagle-import") (part "R-EU_R0402"))
    )
    (comp (ref "R35")
      (value "49R9")
      (footprint "eagle-import:R0402")
      (libsource (lib "eagle-import") (part "R-EU_R0402"))
    )
    (comp (ref "R36")
      (value "1k8")
      (footprint "eagle-import:R0402")
      (libsource (lib "eagle-import") (part "R-EU_R0402"))
    )
    (comp (ref "R37")
      (value "82")
      (footprint "eagle-import:R0402")
      (libsource (lib "eagle-import") (part "R-EU_R0402"))
    )
    (comp (ref "R38")
      (value "49R9")
      (footprint "eagle-import:R0402")
      (libsource (lib "eagle-import") (part "R-EU_R0402"))
    )
    (comp (ref "R39")
      (value "330")
      (footprint "eagle-import:R0402")
      (libsource (lib "eagle-import") (part "R-EU_R0402"))
    )
    (comp (ref "TP15")
      (value "TPB1,27")
      (footprint "eagle-import:B1,27")
      (libsource (lib "eagle-import") (part "TPB1,27"))
    )
    (comp (ref "TP16")
      (value "TPB1,27")
      (footprint "eagle-import:B1,27")
      (libsource (lib "eagle-import") (part "TPB1,27"))
    )
    (comp (ref "C1")
      (value "10u")
      (footprint "eagle-import:C1206")
      (libsource (lib "eagle-import") (part "C-EUC1206"))
    )
    (comp (ref "C2")
      (value "10u")
      (footprint "eagle-import:C1206")
      (libsource (lib "eagle-import") (part "C-EUC1206"))
    )
    (comp (ref "C3")
      (value "10u")
      (footprint "eagle-import:C1206")
      (libsource (lib "eagle-import") (part "C-EUC1206"))
    )
    (comp (ref "C4")
      (value "100n")
      (footprint "eagle-import:C0402")
      (libsource (lib "eagle-import") (part "C-EU?{colon}2C0402"))
    )
    (comp (ref "C5")
      (value "10n")
      (footprint "eagle-import:C0402")
      (libsource (lib "eagle-import") (part "C-EU?{colon}2C0402"))
    )
    (comp (ref "C6")
      (value "100n")
      (footprint "eagle-import:C0402")
      (libsource (lib "eagle-import") (part "C-EU?{colon}2C0402"))
    )
    (comp (ref "C7")
      (value "10u")
      (footprint "eagle-import:C1206")
      (libsource (lib "eagle-import") (part "C-EUC1206"))
    )
    (comp (ref "C8")
      (value "10u")
      (footprint "eagle-import:C1206")
      (libsource (lib "eagle-import") (part "C-EUC1206"))
    )
    (comp (ref "C9")
      (value "100p")
      (footprint "eagle-import:C0402")
      (libsource (lib "eagle-import") (part "C-EU?{colon}2C0402"))
    )
    (comp (ref "C10")
      (value "10u")
      (footprint "eagle-import:C1206")
      (libsource (lib "eagle-import") (part "C-EUC1206"))
    )
    (comp (ref "C11")
      (value "10u")
      (footprint "eagle-import:C1206")
      (libsource (lib "eagle-import") (part "C-EUC1206"))
    )
    (comp (ref "C12")
      (value "10u")
      (footprint "eagle-import:C1206")
      (libsource (lib "eagle-import") (part "C-EUC1206"))
    )
    (comp (ref "C13")
      (value "10u")
      (footprint "eagle-import:C1206")
      (libsource (lib "eagle-import") (part "C-EUC1206"))
    )
    (comp (ref "C14")
      (value "10u")
      (footprint "eagle-import:C1206")
      (libsource (lib "eagle-import") (part "C-EUC1206"))
    )
    (comp (ref "C15")
      (value "10u")
      (footprint "eagle-import:C1206")
      (libsource (lib "eagle-import") (part "C-EUC1206"))
    )
    (comp (ref "C16")
      (value "10u")
      (footprint "eagle-import:C1206")
      (libsource (lib "eagle-import") (part "C-EUC1206"))
    )
    (comp (ref "C17")
      (value "10u")
      (footprint "eagle-import:C1206")
      (libsource (lib "eagle-import") (part "C-EUC1206"))
    )
    (comp (ref "C18")
      (value "1u")
      (footprint "eagle-import:C0603")
      (libsource (lib "eagle-import") (part "C-EU?{colon}1C0603"))
    )
    (comp (ref "C19")
      (value "1u")
      (footprint "eagle-import:C0603")
      (libsource (lib "eagle-import") (part "C-EU?{colon}1C0603"))
    )
    (comp (ref "C20")
      (value "1u")
      (footprint "eagle-import:C0603")
      (libsource (lib "eagle-import") (part "C-EU?{colon}1C0603"))
    )
    (comp (ref "C21")
      (value "1u")
      (footprint "eagle-import:C0603")
      (libsource (lib "eagle-import") (part "C-EU?{colon}1C0603"))
    )
    (comp (ref "C22")
      (value "4u7")
      (footprint "eagle-import:C0603")
      (libsource (lib "eagle-import") (part "C-EU?{colon}1C0603"))
    )
    (comp (ref "C23")
      (value "4u7")
      (footprint "eagle-import:C0603")
      (libsource (lib "eagle-import") (part "C-EU?{colon}1C0603"))
    )
    (comp (ref "C24")
      (value "4u7")
      (footprint "eagle-import:C0603")
      (libsource (lib "eagle-import") (part "C-EU?{colon}1C0603"))
    )
    (comp (ref "C25")
      (value "4u7")
      (footprint "eagle-import:C0603")
      (libsource (lib "eagle-import") (part "C-EU?{colon}1C0603"))
    )
    (comp (ref "C26")
      (value "1u")
      (footprint "eagle-import:C0603")
      (libsource (lib "eagle-import") (part "C-EU?{colon}1C0603"))
    )
    (comp (ref "C27")
      (value "1u")
      (footprint "eagle-import:C0603")
      (libsource (lib "eagle-import") (part "C-EU?{colon}1C0603"))
    )
    (comp (ref "C28")
      (value "1u")
      (footprint "eagle-import:C0603")
      (libsource (lib "eagle-import") (part "C-EU?{colon}1C0603"))
    )
    (comp (ref "D1")
      (value "MBRS2040LT3G")
      (footprint "eagle-import:SMB")
      (libsource (lib "eagle-import") (part "D-SMB"))
    )
    (comp (ref "IC1")
      (value "MIC2253")
      (footprint "eagle-import:SON50P300X300X90-13T170X240N")
      (libsource (lib "eagle-import") (part "MIC2253"))
    )
    (comp (ref "IC2")
      (value "LM3370SD-4221")
      (footprint "eagle-import:SON50P400X500X80-17T260X400N")
      (libsource (lib "eagle-import") (part "LM3370"))
    )
    (comp (ref "IC3")
      (value "LDL212PU50R")
      (footprint "eagle-import:SON95P300X300X100-7T170X240N")
      (libsource (lib "eagle-import") (part "LDL212PU50R"))
    )
    (comp (ref "IC4")
      (value "LDL212PU50R")
      (footprint "eagle-import:SON95P300X300X100-7T170X240N")
      (libsource (lib "eagle-import") (part "LDL212PU50R"))
    )
    (comp (ref "IC5")
      (value "LDL212PU50R")
      (footprint "eagle-import:SON95P300X300X100-7T170X240N")
      (libsource (lib "eagle-import") (part "LDL212PU50R"))
    )
    (comp (ref "IC6")
      (value "LDL212PU50R")
      (footprint "eagle-import:SON95P300X300X100-7T170X240N")
      (libsource (lib "eagle-import") (part "LDL212PU50R"))
    )
    (comp (ref "J1")
      (value "PJ-014D")
      (footprint "eagle-import:PJ-014D")
      (libsource (lib "eagle-import") (part "PJ-014D"))
    )
    (comp (ref "L1")
      (value "2u2")
      (footprint "eagle-import:SRN5040")
      (libsource (lib "eagle-import") (part "SRN5040"))
    )
    (comp (ref "L2")
      (value "2u2")
      (footprint "eagle-import:SRN5040")
      (libsource (lib "eagle-import") (part "SRN5040"))
    )
    (comp (ref "L3")
      (value "2u2")
      (footprint "eagle-import:SRN5040")
      (libsource (lib "eagle-import") (part "SRN5040"))
    )
    (comp (ref "L4")
      (value "2u2")
      (footprint "eagle-import:SRN5040")
      (libsource (lib "eagle-import") (part "SRN5040"))
    )
    (comp (ref "L5")
      (value "2u2")
      (footprint "eagle-import:SRN5040")
      (libsource (lib "eagle-import") (part "SRN5040"))
    )
    (comp (ref "L6")
      (value "Ferrite")
      (footprint "eagle-import:R0402")
      (libsource (lib "eagle-import") (part "FERRITE"))
    )
    (comp (ref "L7")
      (value "Ferrite")
      (footprint "eagle-import:R0402")
      (libsource (lib "eagle-import") (part "FERRITE"))
    )
    (comp (ref "L8")
      (value "Ferrite")
      (footprint "eagle-import:R0402")
      (libsource (lib "eagle-import") (part "FERRITE"))
    )
    (comp (ref "L9")
      (value "Ferrite")
      (footprint "eagle-import:R0402")
      (libsource (lib "eagle-import") (part "FERRITE"))
    )
    (comp (ref "Q1")
      (value "SSM3J338R")
      (footprint "eagle-import:SOTFL95P240X80-3N")
      (libsource (lib "eagle-import") (part "SSM3J338R"))
    )
    (comp (ref "Q2")
      (value "SSM3J338R")
      (footprint "eagle-import:SOTFL95P240X80-3N")
      (libsource (lib "eagle-import") (part "SSM3J338R"))
    )
    (comp (ref "R1")
      (value "620")
      (footprint "eagle-import:R0402")
      (libsource (lib "eagle-import") (part "R-EU_R0402"))
    )
    (comp (ref "R2")
      (value "4k7")
      (footprint "eagle-import:R0402")
      (libsource (lib "eagle-import") (part "R-EU_R0402"))
    )
    (comp (ref "R3")
      (value "10k")
      (footprint "eagle-import:R0402")
      (libsource (lib "eagle-import") (part "R-EU_R0402"))
    )
    (comp (ref "R4")
      (value "38k3")
      (footprint "eagle-import:R0402")
      (libsource (lib "eagle-import") (part "R-EU_R0402"))
    )
    (comp (ref "R5")
      (value "10k")
      (footprint "eagle-import:R0402")
      (libsource (lib "eagle-import") (part "R-EU_R0402"))
    )
    (comp (ref "R125")
      (value "10k")
      (footprint "eagle-import:R0402")
      (libsource (lib "eagle-import") (part "R-EU_R0402"))
    )
    (comp (ref "TP1")
      (value "TPB1,27")
      (footprint "eagle-import:B1,27")
      (libsource (lib "eagle-import") (part "TPB1,27"))
    )
    (comp (ref "TP2")
      (value "TPB1,27")
      (footprint "eagle-import:B1,27")
      (libsource (lib "eagle-import") (part "TPB1,27"))
    )
    (comp (ref "TP3")
      (value "TPB1,27")
      (footprint "eagle-import:B1,27")
      (libsource (lib "eagle-import") (part "TPB1,27"))
    )
    (comp (ref "TP4")
      (value "TPB1,27")
      (footprint "eagle-import:B1,27")
      (libsource (lib "eagle-import") (part "TPB1,27"))
    )
    (comp (ref "TP5")
      (value "TPB1,27")
      (footprint "eagle-import:B1,27")
      (libsource (lib "eagle-import") (part "TPB1,27"))
    )
    (comp (ref "TP6")
      (value "TPB1,27")
      (footprint "eagle-import:B1,27")
      (libsource (lib "eagle-import") (part "TPB1,27"))
    )
    (comp (ref "TP7")
      (value "TPB1,27")
      (footprint "eagle-import:B1,27")
      (libsource (lib "eagle-import") (part "TPB1,27"))
    )
    (comp (ref "TP8")
      (value "TPB1,27")
      (footprint "eagle-import:B1,27")
      (libsource (lib "eagle-import") (part "TPB1,27"))
    )
    (comp (ref "TP9")
      (value "TPB1,27")
      (footprint "eagle-import:B1,27")
      (libsource (lib "eagle-import") (part "TPB1,27"))
    )
    (comp (ref "TP10")
      (value "TPB1,27")
      (footprint "eagle-import:B1,27")
      (libsource (lib "eagle-import") (part "TPB1,27"))
    )
    (comp (ref "TP11")
      (value "TPB1,27")
      (footprint "eagle-import:B1,27")
      (libsource (lib "eagle-import") (part "TPB1,27"))
    )
    (comp (ref "TP12")
      (value "TPB1,27")
      (footprint "eagle-import:B1,27")
      (libsource (lib "eagle-import") (part "TPB1,27"))
    )
    (comp (ref "C69")
      (value "100n")
      (footprint "eagle-import:C0402")
      (libsource (lib "eagle-import") (part "C-EU?{colon}2C0402"))
    )
    (comp (ref "C70")
      (value "100n")
      (footprint "eagle-import:C0402")
      (libsource (lib "eagle-import") (part "C-EU?{colon}2C0402"))
    )
    (comp (ref "C71")
      (value "100n/RF")
      (footprint "eagle-import:C0402")
      (libsource (lib "eagle-import") (part "C-EU?{colon}2C0402"))
    )
    (comp (ref "C72")
      (value "100n")
      (footprint "eagle-import:C0402")
      (libsource (lib "eagle-import") (part "C-EU?{colon}2C0402"))
    )
    (comp (ref "C73")
      (value "100n")
      (footprint "eagle-import:C0402")
      (libsource (lib "eagle-import") (part "C-EU?{colon}2C0402"))
    )
    (comp (ref "C74")
      (value "100n/RF")
      (footprint "eagle-import:C0402")
      (libsource (lib "eagle-import") (part "C-EU?{colon}2C0402"))
    )
    (comp (ref "C75")
      (value "100n")
      (footprint "eagle-import:C0402")
      (libsource (lib "eagle-import") (part "C-EU?{colon}2C0402"))
    )
    (comp (ref "C76")
      (value "100n")
      (footprint "eagle-import:C0402")
      (libsource (lib "eagle-import") (part "C-EU?{colon}2C0402"))
    )
    (comp (ref "C77")
      (value "100n")
      (footprint "eagle-import:C0402")
      (libsource (lib "eagle-import") (part "C-EU?{colon}2C0402"))
    )
    (comp (ref "C235")
      (value "100p")
      (footprint "eagle-import:C0402")
      (libsource (lib "eagle-import") (part "C-EU?{colon}2C0402"))
    )
    (comp (ref "C236")
      (value "100p")
      (footprint "eagle-import:C0402")
      (libsource (lib "eagle-import") (part "C-EU?{colon}2C0402"))
    )
    (comp (ref "C237")
      (value "100p")
      (footprint "eagle-import:C0402")
      (libsource (lib "eagle-import") (part "C-EU?{colon}2C0402"))
    )
    (comp (ref "C238")
      (value "100p")
      (footprint "eagle-import:C0402")
      (libsource (lib "eagle-import") (part "C-EU?{colon}2C0402"))
    )
    (comp (ref "C239")
      (value "100p")
      (footprint "eagle-import:C0402")
      (libsource (lib "eagle-import") (part "C-EU?{colon}2C0402"))
    )
    (comp (ref "C240")
      (value "100p")
      (footprint "eagle-import:C0402")
      (libsource (lib "eagle-import") (part "C-EU?{colon}2C0402"))
    )
    (comp (ref "C241")
      (value "100p")
      (footprint "eagle-import:C0402")
      (libsource (lib "eagle-import") (part "C-EU?{colon}2C0402"))
    )
    (comp (ref "C242")
      (value "100p")
      (footprint "eagle-import:C0402")
      (libsource (lib "eagle-import") (part "C-EU?{colon}2C0402"))
    )
    (comp (ref "C243")
      (value "100p")
      (footprint "eagle-import:C0402")
      (libsource (lib "eagle-import") (part "C-EU?{colon}2C0402"))
    )
    (comp (ref "C244")
      (value "100p")
      (footprint "eagle-import:C0402")
      (libsource (lib "eagle-import") (part "C-EU?{colon}2C0402"))
    )
    (comp (ref "C245")
      (value "100p")
      (footprint "eagle-import:C0402")
      (libsource (lib "eagle-import") (part "C-EU?{colon}2C0402"))
    )
    (comp (ref "C246")
      (value "100p")
      (footprint "eagle-import:C0402")
      (libsource (lib "eagle-import") (part "C-EU?{colon}2C0402"))
    )
    (comp (ref "C247")
      (value "100p")
      (footprint "eagle-import:C0402")
      (libsource (lib "eagle-import") (part "C-EU?{colon}2C0402"))
    )
    (comp (ref "C248")
      (value "100p")
      (footprint "eagle-import:C0402")
      (libsource (lib "eagle-import") (part "C-EU?{colon}2C0402"))
    )
    (comp (ref "C249")
      (value "100p")
      (footprint "eagle-import:C0402")
      (libsource (lib "eagle-import") (part "C-EU?{colon}2C0402"))
    )
    (comp (ref "C250")
      (value "100p")
      (footprint "eagle-import:C0402")
      (libsource (lib "eagle-import") (part "C-EU?{colon}2C0402"))
    )
    (comp (ref "C251")
      (value "100p")
      (footprint "eagle-import:C0402")
      (libsource (lib "eagle-import") (part "C-EU?{colon}2C0402"))
    )
    (comp (ref "C252")
      (value "100p")
      (footprint "eagle-import:C0402")
      (libsource (lib "eagle-import") (part "C-EU?{colon}2C0402"))
    )
    (comp (ref "C253")
      (value "100p")
      (footprint "eagle-import:C0402")
      (libsource (lib "eagle-import") (part "C-EU?{colon}2C0402"))
    )
    (comp (ref "C254")
      (value "100p")
      (footprint "eagle-import:C0402")
      (libsource (lib "eagle-import") (part "C-EU?{colon}2C0402"))
    )
    (comp (ref "C255")
      (value "100p")
      (footprint "eagle-import:C0402")
      (libsource (lib "eagle-import") (part "C-EU?{colon}2C0402"))
    )
    (comp (ref "C256")
      (value "100p")
      (footprint "eagle-import:C0402")
      (libsource (lib "eagle-import") (part "C-EU?{colon}2C0402"))
    )
    (comp (ref "C257")
      (value "100p")
      (footprint "eagle-import:C0402")
      (libsource (lib "eagle-import") (part "C-EU?{colon}2C0402"))
    )
    (comp (ref "C258")
      (value "100p")
      (footprint "eagle-import:C0402")
      (libsource (lib "eagle-import") (part "C-EU?{colon}2C0402"))
    )
    (comp (ref "C259")
      (value "100p")
      (footprint "eagle-import:C0402")
      (libsource (lib "eagle-import") (part "C-EU?{colon}2C0402"))
    )
    (comp (ref "C260")
      (value "100p")
      (footprint "eagle-import:C0402")
      (libsource (lib "eagle-import") (part "C-EU?{colon}2C0402"))
    )
    (comp (ref "C261")
      (value "100p")
      (footprint "eagle-import:C0402")
      (libsource (lib "eagle-import") (part "C-EU?{colon}2C0402"))
    )
    (comp (ref "C262")
      (value "100p")
      (footprint "eagle-import:C0402")
      (libsource (lib "eagle-import") (part "C-EU?{colon}2C0402"))
    )
    (comp (ref "IC13")
      (value "QPC6324")
      (footprint "eagle-import:QFN50P400X400X75-21T206")
      (libsource (lib "eagle-import") (part "QPC6324"))
    )
    (comp (ref "IC14")
      (value "RFSA3714")
      (footprint "eagle-import:QFN50P400X400X75-25T270")
      (libsource (lib "eagle-import") (part "RFSA3714"))
    )
    (comp (ref "IC15")
      (value "TRF37A73")
      (footprint "eagle-import:SON50P200X200X80-9T90X160N")
      (libsource (lib "eagle-import") (part "TRF37A73"))
    )
    (comp (ref "IC16")
      (value "QPC6324")
      (footprint "eagle-import:QFN50P400X400X75-21T206")
      (libsource (lib "eagle-import") (part "QPC6324"))
    )
    (comp (ref "IC17")
      (value "QPC6324")
      (footprint "eagle-import:QFN50P400X400X75-21T206")
      (libsource (lib "eagle-import") (part "QPC6324"))
    )
    (comp (ref "IC18")
      (value "QPC6324")
      (footprint "eagle-import:QFN50P400X400X75-21T206")
      (libsource (lib "eagle-import") (part "QPC6324"))
    )
    (comp (ref "L11")
      (value "10u")
      (footprint "eagle-import:INDC2012X100N")
      (libsource (lib "eagle-import") (part "INDUCTOR"))
    )
    (comp (ref "L21")
      (value "Ferrite")
      (footprint "eagle-import:R0402")
      (libsource (lib "eagle-import") (part "FERRITE"))
    )
    (comp (ref "L22")
      (value "Ferrite")
      (footprint "eagle-import:R0402")
      (libsource (lib "eagle-import") (part "FERRITE"))
    )
    (comp (ref "L23")
      (value "Ferrite")
      (footprint "eagle-import:R0402")
      (libsource (lib "eagle-import") (part "FERRITE"))
    )
    (comp (ref "L24")
      (value "330n")
      (footprint "eagle-import:L0402")
      (libsource (lib "eagle-import") (part "INDUCTOR0402"))
    )
    (comp (ref "L25")
      (value "Ferrite")
      (footprint "eagle-import:R0402")
      (libsource (lib "eagle-import") (part "FERRITE"))
    )
    (comp (ref "L26")
      (value "Ferrite")
      (footprint "eagle-import:R0402")
      (libsource (lib "eagle-import") (part "FERRITE"))
    )
    (comp (ref "L27")
      (value "Ferrite")
      (footprint "eagle-import:R0402")
      (libsource (lib "eagle-import") (part "FERRITE"))
    )
    (comp (ref "R26")
      (value "2R7")
      (footprint "eagle-import:R0402")
      (libsource (lib "eagle-import") (part "R-EU_R0402"))
    )
    (comp (ref "R27")
      (value "402")
      (footprint "eagle-import:R0402")
      (libsource (lib "eagle-import") (part "R-EU_R0402"))
    )
    (comp (ref "R28")
      (value "56")
      (footprint "eagle-import:R0402")
      (libsource (lib "eagle-import") (part "R-EU_R0402"))
    )
    (comp (ref "R29")
      (value "2R7")
      (footprint "eagle-import:R0402")
      (libsource (lib "eagle-import") (part "R-EU_R0402"))
    )
    (comp (ref "R149")
      (value "10k")
      (footprint "eagle-import:R0402")
      (libsource (lib "eagle-import") (part "R-EU_R0402"))
    )
    (comp (ref "R150")
      (value "10k")
      (footprint "eagle-import:R0402")
      (libsource (lib "eagle-import") (part "R-EU_R0402"))
    )
    (comp (ref "R151")
      (value "10k")
      (footprint "eagle-import:R0402")
      (libsource (lib "eagle-import") (part "R-EU_R0402"))
    )
    (comp (ref "R152")
      (value "10k")
      (footprint "eagle-import:R0402")
      (libsource (lib "eagle-import") (part "R-EU_R0402"))
    )
    (comp (ref "R153")
      (value "10k")
      (footprint "eagle-import:R0402")
      (libsource (lib "eagle-import") (part "R-EU_R0402"))
    )
    (comp (ref "R154")
      (value "10k")
      (footprint "eagle-import:R0402")
      (libsource (lib "eagle-import") (part "R-EU_R0402"))
    )
    (comp (ref "R155")
      (value "10k")
      (footprint "eagle-import:R0402")
      (libsource (lib "eagle-import") (part "R-EU_R0402"))
    )
    (comp (ref "R156")
      (value "10k")
      (footprint "eagle-import:R0402")
      (libsource (lib "eagle-import") (part "R-EU_R0402"))
    )
    (comp (ref "R157")
      (value "10k")
      (footprint "eagle-import:R0402")
      (libsource (lib "eagle-import") (part "R-EU_R0402"))
    )
    (comp (ref "R158")
      (value "10k")
      (footprint "eagle-import:R0402")
      (libsource (lib "eagle-import") (part "R-EU_R0402"))
    )
    (comp (ref "R159")
      (value "10k")
      (footprint "eagle-import:R0402")
      (libsource (lib "eagle-import") (part "R-EU_R0402"))
    )
    (comp (ref "R160")
      (value "10k")
      (footprint "eagle-import:R0402")
      (libsource (lib "eagle-import") (part "R-EU_R0402"))
    )
    (comp (ref "R161")
      (value "10k")
      (footprint "eagle-import:R0402")
      (libsource (lib "eagle-import") (part "R-EU_R0402"))
    )
    (comp (ref "R162")
      (value "10k")
      (footprint "eagle-import:R0402")
      (libsource (lib "eagle-import") (part "R-EU_R0402"))
    )
    (comp (ref "C96")
      (value "100n/RF")
      (footprint "eagle-import:C0402")
      (libsource (lib "eagle-import") (part "C-EU?{colon}2C0402"))
    )
    (comp (ref "C97")
      (value "100n")
      (footprint "eagle-import:C0402")
      (libsource (lib "eagle-import") (part "C-EU?{colon}2C0402"))
    )
    (comp (ref "C98")
      (value "100n")
      (footprint "eagle-import:C0402")
      (libsource (lib "eagle-import") (part "C-EU?{colon}2C0402"))
    )
    (comp (ref "C99")
      (value "100n/RF")
      (footprint "eagle-import:C0402")
      (libsource (lib "eagle-import") (part "C-EU?{colon}2C0402"))
    )
    (comp (ref "C100")
      (value "1u")
      (footprint "eagle-import:C0402")
      (libsource (lib "eagle-import") (part "C-EU?{colon}2C0402"))
    )
    (comp (ref "C101")
      (value "1u")
      (footprint "eagle-import:C0402")
      (libsource (lib "eagle-import") (part "C-EU?{colon}2C0402"))
    )
    (comp (ref "C102")
      (value "100n")
      (footprint "eagle-import:C0402")
      (libsource (lib "eagle-import") (part "C-EU?{colon}2C0402"))
    )
    (comp (ref "C103")
      (value "100n")
      (footprint "eagle-import:C0402")
      (libsource (lib "eagle-import") (part "C-EU?{colon}2C0402"))
    )
    (comp (ref "C104")
      (value "10n")
      (footprint "eagle-import:C0402")
      (libsource (lib "eagle-import") (part "C-EU?{colon}2C0402"))
    )
    (comp (ref "C105")
      (value "10n")
      (footprint "eagle-import:C0402")
      (libsource (lib "eagle-import") (part "C-EU?{colon}2C0402"))
    )
    (comp (ref "C106")
      (value "10n")
      (footprint "eagle-import:C0402")
      (libsource (lib "eagle-import") (part "C-EU?{colon}2C0402"))
    )
    (comp (ref "C107")
      (value "DNP")
      (footprint "eagle-import:C0402")
      (libsource (lib "eagle-import") (part "C-EU?{colon}2C0402"))
    )
    (comp (ref "C108")
      (value "1u")
      (footprint "eagle-import:C0402")
      (libsource (lib "eagle-import") (part "C-EU?{colon}2C0402"))
    )
    (comp (ref "C109")
      (value "100n/RF")
      (footprint "eagle-import:C0402")
      (libsource (lib "eagle-import") (part "C-EU?{colon}2C0402"))
    )
    (comp (ref "C110")
      (value "100n/RF")
      (footprint "eagle-import:C0402")
      (libsource (lib "eagle-import") (part "C-EU?{colon}2C0402"))
    )
    (comp (ref "C111")
      (value "10n")
      (footprint "eagle-import:C0402")
      (libsource (lib "eagle-import") (part "C-EU?{colon}2C0402"))
    )
    (comp (ref "C112")
      (value "DNP")
      (footprint "eagle-import:C0402")
      (libsource (lib "eagle-import") (part "C-EU?{colon}2C0402"))
    )
    (comp (ref "C113")
      (value "DNP")
      (footprint "eagle-import:C0402")
      (libsource (lib "eagle-import") (part "C-EU?{colon}2C0402"))
    )
    (comp (ref "C114")
      (value "100n")
      (footprint "eagle-import:C0402")
      (libsource (lib "eagle-import") (part "C-EU?{colon}2C0402"))
    )
    (comp (ref "C115")
      (value "100n")
      (footprint "eagle-import:C0402")
      (libsource (lib "eagle-import") (part "C-EU?{colon}2C0402"))
    )
    (comp (ref "C116")
      (value "100n")
      (footprint "eagle-import:C0402")
      (libsource (lib "eagle-import") (part "C-EU?{colon}2C0402"))
    )
    (comp (ref "C117")
      (value "100n")
      (footprint "eagle-import:C0402")
      (libsource (lib "eagle-import") (part "C-EU?{colon}2C0402"))
    )
    (comp (ref "C118")
      (value "100n")
      (footprint "eagle-import:C0402")
      (libsource (lib "eagle-import") (part "C-EU?{colon}2C0402"))
    )
    (comp (ref "C119")
      (value "100n")
      (footprint "eagle-import:C0402")
      (libsource (lib "eagle-import") (part "C-EU?{colon}2C0402"))
    )
    (comp (ref "C120")
      (value "10n")
      (footprint "eagle-import:C0402")
      (libsource (lib "eagle-import") (part "C-EU?{colon}2C0402"))
    )
    (comp (ref "C121")
      (value "330p")
      (footprint "eagle-import:C0402")
      (libsource (lib "eagle-import") (part "C-EU?{colon}2C0402"))
    )
    (comp (ref "C122")
      (value "100n")
      (footprint "eagle-import:C0402")
      (libsource (lib "eagle-import") (part "C-EU?{colon}2C0402"))
    )
    (comp (ref "C123")
      (value "10n")
      (footprint "eagle-import:C0402")
      (libsource (lib "eagle-import") (part "C-EU?{colon}2C0402"))
    )
    (comp (ref "C124")
      (value "120p")
      (footprint "eagle-import:C0402")
      (libsource (lib "eagle-import") (part "C-EU?{colon}2C0402"))
    )
    (comp (ref "C125")
      (value "330p")
      (footprint "eagle-import:C0402")
      (libsource (lib "eagle-import") (part "C-EU?{colon}2C0402"))
    )
    (comp (ref "C126")
      (value "330p")
      (footprint "eagle-import:C0402")
      (libsource (lib "eagle-import") (part "C-EU?{colon}2C0402"))
    )
    (comp (ref "C127")
      (value "330p")
      (footprint "eagle-import:C0402")
      (libsource (lib "eagle-import") (part "C-EU?{colon}2C0402"))
    )
    (comp (ref "C128")
      (value "150p")
      (footprint "eagle-import:C0402")
      (libsource (lib "eagle-import") (part "C-EU?{colon}2C0402"))
    )
    (comp (ref "C129")
      (value "1u")
      (footprint "eagle-import:C0402")
      (libsource (lib "eagle-import") (part "C-EU?{colon}2C0402"))
    )
    (comp (ref "C130")
      (value "33p")
      (footprint "eagle-import:C0402")
      (libsource (lib "eagle-import") (part "C-EU?{colon}2C0402"))
    )
    (comp (ref "C131")
      (value "1u")
      (footprint "eagle-import:C0402")
      (libsource (lib "eagle-import") (part "C-EU?{colon}2C0402"))
    )
    (comp (ref "C132")
      (value "100n")
      (footprint "eagle-import:C0402")
      (libsource (lib "eagle-import") (part "C-EU?{colon}2C0402"))
    )
    (comp (ref "C269")
      (value "100n")
      (footprint "eagle-import:C0402")
      (libsource (lib "eagle-import") (part "C-EU?{colon}2C0402"))
    )
    (comp (ref "IC22")
      (value "LT5560")
      (footprint "eagle-import:SON50P300X300X80-9T165X238")
      (libsource (lib "eagle-import") (part "LT5560"))
    )
    (comp (ref "IC23")
      (value "THS4521IDGKR")
      (footprint "eagle-import:SOP65P490X110-8N")
      (libsource (lib "eagle-import") (part "THS4521IDGKR"))
    )
    (comp (ref "IC24")
      (value "ADL5801")
      (footprint "eagle-import:QFN50P400X400X100-25T250N")
      (libsource (lib "eagle-import") (part "ADL5801"))
    )
    (comp (ref "IC25")
      (value "NCP702-1.8")
      (footprint "eagle-import:SOT95P240X110-5")
      (libsource (lib "eagle-import") (part "NCP702"))
    )
    (comp (ref "IC26")
      (value "MCP33131D-10-E/MS")
      (footprint "eagle-import:SOP50P490X110-10N")
      (libsource (lib "eagle-import") (part "MCP33131D-10-E/MS"))
    )
    (comp (ref "J2")
      (value "BU-1420701851")
      (footprint "eagle-import:BU-1420701851")
      (libsource (lib "eagle-import") (part "BU-1420701851"))
    )
    (comp (ref "L12")
      (value "Ferrite")
      (footprint "eagle-import:R0402")
      (libsource (lib "eagle-import") (part "FERRITE"))
    )
    (comp (ref "L13")
      (value "Ferrite")
      (footprint "eagle-import:R0402")
      (libsource (lib "eagle-import") (part "FERRITE"))
    )
    (comp (ref "L15")
      (value "Ferrite")
      (footprint "eagle-import:R0402")
      (libsource (lib "eagle-import") (part "FERRITE"))
    )
    (comp (ref "L16")
      (value "Ferrite")
      (footprint "eagle-import:R0402")
      (libsource (lib "eagle-import") (part "FERRITE"))
    )
    (comp (ref "L17")
      (value "Ferrite")
      (footprint "eagle-import:R0402")
      (libsource (lib "eagle-import") (part "FERRITE"))
    )
    (comp (ref "L30")
      (value "330n")
      (footprint "eagle-import:L0402")
      (libsource (lib "eagle-import") (part "INDUCTOR0402"))
    )
    (comp (ref "L31")
      (value "330n")
      (footprint "eagle-import:L0402")
      (libsource (lib "eagle-import") (part "INDUCTOR0402"))
    )
    (comp (ref "L32")
      (value "330n")
      (footprint "eagle-import:L0402")
      (libsource (lib "eagle-import") (part "INDUCTOR0402"))
    )
    (comp (ref "L33")
      (value "330n")
      (footprint "eagle-import:L0402")
      (libsource (lib "eagle-import") (part "INDUCTOR0402"))
    )
    (comp (ref "L34")
      (value "68n")
      (footprint "eagle-import:L0402")
      (libsource (lib "eagle-import") (part "INDUCTOR0402"))
    )
    (comp (ref "L35")
      (value "68n")
      (footprint "eagle-import:L0402")
      (libsource (lib "eagle-import") (part "INDUCTOR0402"))
    )
    (comp (ref "L36")
      (value "33n")
      (footprint "eagle-import:L0402")
      (libsource (lib "eagle-import") (part "INDUCTOR0402"))
    )
    (comp (ref "L37")
      (value "33n")
      (footprint "eagle-import:L0402")
      (libsource (lib "eagle-import") (part "INDUCTOR0402"))
    )
    (comp (ref "R45")
      (value "49R9")
      (footprint "eagle-import:R0402")
      (libsource (lib "eagle-import") (part "R-EU_R0402"))
    )
    (comp (ref "R46")
      (value "49R9")
      (footprint "eagle-import:R0402")
      (libsource (lib "eagle-import") (part "R-EU_R0402"))
    )
    (comp (ref "R48")
      (value "DNP")
      (footprint "eagle-import:PAT0816")
      (libsource (lib "eagle-import") (part "PAT0816-C-3DB-T5"))
    )
    (comp (ref "R49")
      (value "PAT0816-C-3DB-T5")
      (footprint "eagle-import:PAT0816")
      (libsource (lib "eagle-import") (part "PAT0816-C-3DB-T5"))
    )
    (comp (ref "R50")
      (value "49R9")
      (footprint "eagle-import:R0402")
      (libsource (lib "eagle-import") (part "R-EU_R0402"))
    )
    (comp (ref "R53")
      (value "220")
      (footprint "eagle-import:R0402")
      (libsource (lib "eagle-import") (part "R-EU_R0402"))
    )
    (comp (ref "R54")
      (value "220")
      (footprint "eagle-import:R0402")
      (libsource (lib "eagle-import") (part "R-EU_R0402"))
    )
    (comp (ref "R55")
      (value "6k8")
      (footprint "eagle-import:R0402")
      (libsource (lib "eagle-import") (part "R-EU_R0402"))
    )
    (comp (ref "R56")
      (value "6k8")
      (footprint "eagle-import:R0402")
      (libsource (lib "eagle-import") (part "R-EU_R0402"))
    )
    (comp (ref "R57")
      (value "DNP")
      (footprint "eagle-import:R0402")
      (libsource (lib "eagle-import") (part "R-EU_R0402"))
    )
    (comp (ref "R58")
      (value "220")
      (footprint "eagle-import:R0402")
      (libsource (lib "eagle-import") (part "R-EU_R0402"))
    )
    (comp (ref "R59")
      (value "220")
      (footprint "eagle-import:R0402")
      (libsource (lib "eagle-import") (part "R-EU_R0402"))
    )
    (comp (ref "R60")
      (value "1k")
      (footprint "eagle-import:R0402")
      (libsource (lib "eagle-import") (part "R-EU_R0402"))
    )
    (comp (ref "R61")
      (value "220")
      (footprint "eagle-import:R0402")
      (libsource (lib "eagle-import") (part "R-EU_R0402"))
    )
    (comp (ref "R62")
      (value "220")
      (footprint "eagle-import:R0402")
      (libsource (lib "eagle-import") (part "R-EU_R0402"))
    )
    (comp (ref "R63")
      (value "56")
      (footprint "eagle-import:R0402")
      (libsource (lib "eagle-import") (part "R-EU_R0402"))
    )
    (comp (ref "R64")
      (value "20")
      (footprint "eagle-import:R0402")
      (libsource (lib "eagle-import") (part "R-EU_R0402"))
    )
    (comp (ref "R65")
      (value "20")
      (footprint "eagle-import:R0402")
      (libsource (lib "eagle-import") (part "R-EU_R0402"))
    )
    (comp (ref "R66")
      (value "56")
      (footprint "eagle-import:R0402")
      (libsource (lib "eagle-import") (part "R-EU_R0402"))
    )
    (comp (ref "R168")
      (value "75")
      (footprint "eagle-import:R0402")
      (libsource (lib "eagle-import") (part "R-EU_R0402"))
    )
    (comp (ref "R169")
      (value "100")
      (footprint "eagle-import:R0402")
      (libsource (lib "eagle-import") (part "R-EU_R0402"))
    )
    (comp (ref "R172")
      (value "100")
      (footprint "eagle-import:R0402")
      (libsource (lib "eagle-import") (part "R-EU_R0402"))
    )
    (comp (ref "T1")
      (value "B012-617DB-1-63-B331")
      (footprint "eagle-import:EASTEVER_BALUN")
      (libsource (lib "eagle-import") (part "B012-617DB-1-63-B331"))
    )
    (comp (ref "TP17")
      (value "TPB1,27")
      (footprint "eagle-import:B1,27")
      (libsource (lib "eagle-import") (part "TPB1,27"))
    )
    (comp (ref "C170")
      (value "100n/RF")
      (footprint "eagle-import:C0402")
      (libsource (lib "eagle-import") (part "C-EU?{colon}2C0402"))
    )
    (comp (ref "C171")
      (value "10n")
      (footprint "eagle-import:C0402")
      (libsource (lib "eagle-import") (part "C-EU?{colon}2C0402"))
    )
    (comp (ref "C172")
      (value "10n")
      (footprint "eagle-import:C0402")
      (libsource (lib "eagle-import") (part "C-EU?{colon}2C0402"))
    )
    (comp (ref "C173")
      (value "DNP")
      (footprint "eagle-import:C0402")
      (libsource (lib "eagle-import") (part "C-EU?{colon}2C0402"))
    )
    (comp (ref "C174")
      (value "DNP")
      (footprint "eagle-import:C0402")
      (libsource (lib "eagle-import") (part "C-EU?{colon}2C0402"))
    )
    (comp (ref "C175")
      (value "10n")
      (footprint "eagle-import:C0402")
      (libsource (lib "eagle-import") (part "C-EU?{colon}2C0402"))
    )
    (comp (ref "C176")
      (value "DNP")
      (footprint "eagle-import:C0402")
      (libsource (lib "eagle-import") (part "C-EU?{colon}2C0402"))
    )
    (comp (ref "C177")
      (value "1u")
      (footprint "eagle-import:C0402")
      (libsource (lib "eagle-import") (part "C-EU?{colon}2C0402"))
    )
    (comp (ref "C178")
      (value "100n/RF")
      (footprint "eagle-import:C0402")
      (libsource (lib "eagle-import") (part "C-EU?{colon}2C0402"))
    )
    (comp (ref "C179")
      (value "100n/RF")
      (footprint "eagle-import:C0402")
      (libsource (lib "eagle-import") (part "C-EU?{colon}2C0402"))
    )
    (comp (ref "C180")
      (value "10n")
      (footprint "eagle-import:C0402")
      (libsource (lib "eagle-import") (part "C-EU?{colon}2C0402"))
    )
    (comp (ref "C181")
      (value "100n")
      (footprint "eagle-import:C0402")
      (libsource (lib "eagle-import") (part "C-EU?{colon}2C0402"))
    )
    (comp (ref "C182")
      (value "100n")
      (footprint "eagle-import:C0402")
      (libsource (lib "eagle-import") (part "C-EU?{colon}2C0402"))
    )
    (comp (ref "C183")
      (value "100n")
      (footprint "eagle-import:C0402")
      (libsource (lib "eagle-import") (part "C-EU?{colon}2C0402"))
    )
    (comp (ref "C184")
      (value "330p")
      (footprint "eagle-import:C0402")
      (libsource (lib "eagle-import") (part "C-EU?{colon}2C0402"))
    )
    (comp (ref "C185")
      (value "100n")
      (footprint "eagle-import:C0402")
      (libsource (lib "eagle-import") (part "C-EU?{colon}2C0402"))
    )
    (comp (ref "C186")
      (value "100n")
      (footprint "eagle-import:C0402")
      (libsource (lib "eagle-import") (part "C-EU?{colon}2C0402"))
    )
    (comp (ref "C187")
      (value "330p")
      (footprint "eagle-import:C0402")
      (libsource (lib "eagle-import") (part "C-EU?{colon}2C0402"))
    )
    (comp (ref "C188")
      (value "330p")
      (footprint "eagle-import:C0402")
      (libsource (lib "eagle-import") (part "C-EU?{colon}2C0402"))
    )
    (comp (ref "C189")
      (value "330p")
      (footprint "eagle-import:C0402")
      (libsource (lib "eagle-import") (part "C-EU?{colon}2C0402"))
    )
    (comp (ref "C190")
      (value "100n")
      (footprint "eagle-import:C0402")
      (libsource (lib "eagle-import") (part "C-EU?{colon}2C0402"))
    )
    (comp (ref "C191")
      (value "10n")
      (footprint "eagle-import:C0402")
      (libsource (lib "eagle-import") (part "C-EU?{colon}2C0402"))
    )
    (comp (ref "C192")
      (value "10n")
      (footprint "eagle-import:C0402")
      (libsource (lib "eagle-import") (part "C-EU?{colon}2C0402"))
    )
    (comp (ref "C193")
      (value "100n")
      (footprint "eagle-import:C0402")
      (libsource (lib "eagle-import") (part "C-EU?{colon}2C0402"))
    )
    (comp (ref "C194")
      (value "120p")
      (footprint "eagle-import:C0402")
      (libsource (lib "eagle-import") (part "C-EU?{colon}2C0402"))
    )
    (comp (ref "C195")
      (value "1u")
      (footprint "eagle-import:C0402")
      (libsource (lib "eagle-import") (part "C-EU?{colon}2C0402"))
    )
    (comp (ref "C196")
      (value "150p")
      (footprint "eagle-import:C0402")
      (libsource (lib "eagle-import") (part "C-EU?{colon}2C0402"))
    )
    (comp (ref "C197")
      (value "33p")
      (footprint "eagle-import:C0402")
      (libsource (lib "eagle-import") (part "C-EU?{colon}2C0402"))
    )
    (comp (ref "C198")
      (value "1u")
      (footprint "eagle-import:C0402")
      (libsource (lib "eagle-import") (part "C-EU?{colon}2C0402"))
    )
    (comp (ref "C199")
      (value "100n")
      (footprint "eagle-import:C0402")
      (libsource (lib "eagle-import") (part "C-EU?{colon}2C0402"))
    )
    (comp (ref "C200")
      (value "100n")
      (footprint "eagle-import:C0402")
      (libsource (lib "eagle-import") (part "C-EU?{colon}2C0402"))
    )
    (comp (ref "C201")
      (value "100n")
      (footprint "eagle-import:C0402")
      (libsource (lib "eagle-import") (part "C-EU?{colon}2C0402"))
    )
    (comp (ref "C202")
      (value "1u")
      (footprint "eagle-import:C0402")
      (libsource (lib "eagle-import") (part "C-EU?{colon}2C0402"))
    )
    (comp (ref "C203")
      (value "1u")
      (footprint "eagle-import:C0402")
      (libsource (lib "eagle-import") (part "C-EU?{colon}2C0402"))
    )
    (comp (ref "C204")
      (value "100n")
      (footprint "eagle-import:C0402")
      (libsource (lib "eagle-import") (part "C-EU?{colon}2C0402"))
    )
    (comp (ref "C205")
      (value "100n")
      (footprint "eagle-import:C0402")
      (libsource (lib "eagle-import") (part "C-EU?{colon}2C0402"))
    )
    (comp (ref "C270")
      (value "100n")
      (footprint "eagle-import:C0402")
      (libsource (lib "eagle-import") (part "C-EU?{colon}2C0402"))
    )
    (comp (ref "IC32")
      (value "THS4521IDGKR")
      (footprint "eagle-import:SOP65P490X110-8N")
      (libsource (lib "eagle-import") (part "THS4521IDGKR"))
    )
    (comp (ref "IC33")
      (value "ADL5801")
      (footprint "eagle-import:QFN50P400X400X100-25T250N")
      (libsource (lib "eagle-import") (part "ADL5801"))
    )
    (comp (ref "IC34")
      (value "NCP702-1.8")
      (footprint "eagle-import:SOT95P240X110-5")
      (libsource (lib "eagle-import") (part "NCP702"))
    )
    (comp (ref "IC35")
      (value "MCP33131D-10-E/MS")
      (footprint "eagle-import:SOP50P490X110-10N")
      (libsource (lib "eagle-import") (part "MCP33131D-10-E/MS"))
    )
    (comp (ref "IC36")
      (value "LT5560")
      (footprint "eagle-import:SON50P300X300X80-9T165X238")
      (libsource (lib "eagle-import") (part "LT5560"))
    )
    (comp (ref "L46")
      (value "330n")
      (footprint "eagle-import:L0402")
      (libsource (lib "eagle-import") (part "INDUCTOR0402"))
    )
    (comp (ref "L47")
      (value "330n")
      (footprint "eagle-import:L0402")
      (libsource (lib "eagle-import") (part "INDUCTOR0402"))
    )
    (comp (ref "L48")
      (value "68n")
      (footprint "eagle-import:L0402")
      (libsource (lib "eagle-import") (part "INDUCTOR0402"))
    )
    (comp (ref "L49")
      (value "68n")
      (footprint "eagle-import:L0402")
      (libsource (lib "eagle-import") (part "INDUCTOR0402"))
    )
    (comp (ref "L50")
      (value "33n")
      (footprint "eagle-import:L0402")
      (libsource (lib "eagle-import") (part "INDUCTOR0402"))
    )
    (comp (ref "L51")
      (value "33n")
      (footprint "eagle-import:L0402")
      (libsource (lib "eagle-import") (part "INDUCTOR0402"))
    )
    (comp (ref "L52")
      (value "330n")
      (footprint "eagle-import:L0402")
      (libsource (lib "eagle-import") (part "INDUCTOR0402"))
    )
    (comp (ref "L53")
      (value "330n")
      (footprint "eagle-import:L0402")
      (libsource (lib "eagle-import") (part "INDUCTOR0402"))
    )
    (comp (ref "L59")
      (value "Ferrite")
      (footprint "eagle-import:R0402")
      (libsource (lib "eagle-import") (part "FERRITE"))
    )
    (comp (ref "L60")
      (value "Ferrite")
      (footprint "eagle-import:R0402")
      (libsource (lib "eagle-import") (part "FERRITE"))
    )
    (comp (ref "L61")
      (value "Ferrite")
      (footprint "eagle-import:R0402")
      (libsource (lib "eagle-import") (part "FERRITE"))
    )
    (comp (ref "L62")
      (value "Ferrite")
      (footprint "eagle-import:R0402")
      (libsource (lib "eagle-import") (part "FERRITE"))
    )
    (comp (ref "L63")
      (value "Ferrite")
      (footprint "eagle-import:R0402")
      (libsource (lib "eagle-import") (part "FERRITE"))
    )
    (comp (ref "R94")
      (value "4k7")
      (footprint "eagle-import:R0402")
      (libsource (lib "eagle-import") (part "R-EU_R0402"))
    )
    (comp (ref "R95")
      (value "4k7")
      (footprint "eagle-import:R0402")
      (libsource (lib "eagle-import") (part "R-EU_R0402"))
    )
    (comp (ref "R96")
      (value "220")
      (footprint "eagle-import:R0402")
      (libsource (lib "eagle-import") (part "R-EU_R0402"))
    )
    (comp (ref "R97")
      (value "220")
      (footprint "eagle-import:R0402")
      (libsource (lib "eagle-import") (part "R-EU_R0402"))
    )
    (comp (ref "R98")
      (value "220")
      (footprint "eagle-import:R0402")
      (libsource (lib "eagle-import") (part "R-EU_R0402"))
    )
    (comp (ref "R99")
      (value "220")
      (footprint "eagle-import:R0402")
      (libsource (lib "eagle-import") (part "R-EU_R0402"))
    )
    (comp (ref "R100")
      (value "DNP")
      (footprint "eagle-import:R0402")
      (libsource (lib "eagle-import") (part "R-EU_R0402"))
    )
    (comp (ref "R101")
      (value "1k")
      (footprint "eagle-import:R0402")
      (libsource (lib "eagle-import") (part "R-EU_R0402"))
    )
    (comp (ref "R102")
      (value "220")
      (footprint "eagle-import:R0402")
      (libsource (lib "eagle-import") (part "R-EU_R0402"))
    )
    (comp (ref "R103")
      (value "220")
      (footprint "eagle-import:R0402")
      (libsource (lib "eagle-import") (part "R-EU_R0402"))
    )
    (comp (ref "R173")
      (value "75")
      (footprint "eagle-import:R0402")
      (libsource (lib "eagle-import") (part "R-EU_R0402"))
    )
    (comp (ref "R174")
      (value "100")
      (footprint "eagle-import:R0402")
      (libsource (lib "eagle-import") (part "R-EU_R0402"))
    )
    (comp (ref "R175")
      (value "100")
      (footprint "eagle-import:R0402")
      (libsource (lib "eagle-import") (part "R-EU_R0402"))
    )
    (comp (ref "T3")
      (value "B012-617DB-1-63-B331")
      (footprint "eagle-import:EASTEVER_BALUN")
      (libsource (lib "eagle-import") (part "B012-617DB-1-63-B331"))
    )
    (comp (ref "TP19")
      (value "TPB1,27")
      (footprint "eagle-import:B1,27")
      (libsource (lib "eagle-import") (part "TPB1,27"))
    )
  )
  (nets
    (net (code "1") (name "+3V3") (class "Default")
      (node (ref "C132") (pin "2") (pinfunction "2_2") (pintype "passive"))
      (node (ref "C14") (pin "1") (pinfunction "1_1") (pintype "passive"))
      (node (ref "C15") (pin "1") (pinfunction "1_1") (pintype "passive"))
      (node (ref "C169") (pin "2") (pinfunction "2_2") (pintype "passive"))
      (node (ref "C201") (pin "2") (pinfunction "2_2") (pintype "passive"))
      (node (ref "C206") (pin "1") (pinfunction "1_1") (pintype "passive"))
      (node (ref "C207") (pin "1") (pinfunction "1_1") (pintype "passive"))
      (node (ref "C208") (pin "1") (pinfunction "1_1") (pintype "passive"))
      (node (ref "C209") (pin "1") (pinfunction "1_1") (pintype "passive"))
      (node (ref "C210") (pin "1") (pinfunction "1_1") (pintype "passive"))
      (node (ref "C212") (pin "1") (pinfunction "1_1") (pintype "passive"))
      (node (ref "C214") (pin "1") (pinfunction "1_1") (pintype "passive"))
      (node (ref "C216") (pin "1") (pinfunction "1_1") (pintype "passive"))
      (node (ref "C218") (pin "1") (pinfunction "1_1") (pintype "passive"))
      (node (ref "C220") (pin "1") (pinfunction "1_1") (pintype "passive"))
      (node (ref "C221") (pin "1") (pinfunction "1_1") (pintype "passive"))
      (node (ref "C222") (pin "1") (pinfunction "1_1") (pintype "passive"))
      (node (ref "C29") (pin "2") (pinfunction "2_2") (pintype "passive"))
      (node (ref "C31") (pin "2") (pinfunction "2_2") (pintype "passive"))
      (node (ref "IC26") (pin "10") (pinfunction "DVIO_10") (pintype "bidirectional"))
      (node (ref "IC26") (pin "9") (pinfunction "SDI_9") (pintype "bidirectional"))
      (node (ref "IC31") (pin "10") (pinfunction "DVIO_10") (pintype "bidirectional"))
      (node (ref "IC31") (pin "9") (pinfunction "SDI_9") (pintype "bidirectional"))
      (node (ref "IC35") (pin "10") (pinfunction "DVIO_10") (pintype "bidirectional"))
      (node (ref "IC35") (pin "9") (pinfunction "SDI_9") (pintype "bidirectional"))
      (node (ref "IC37") (pin "1") (pinfunction "VBAT_1") (pintype "bidirectional"))
      (node (ref "IC37") (pin "20") (pinfunction "VREF+_20") (pintype "bidirectional"))
      (node (ref "IC37") (pin "21") (pinfunction "VDDA_21") (pintype "bidirectional"))
      (node (ref "IC37") (pin "23") (pinfunction "VDD_23") (pintype "bidirectional"))
      (node (ref "IC37") (pin "35") (pinfunction "VDD_35") (pintype "bidirectional"))
      (node (ref "IC37") (pin "48") (pinfunction "VDD_48") (pintype "bidirectional"))
      (node (ref "IC7") (pin "20") (pinfunction "VDD_20") (pintype "bidirectional"))
      (node (ref "JP1") (pin "5") (pinfunction "5_5") (pintype "passive"))
      (node (ref "JP2") (pin "1") (pinfunction "1_1") (pintype "passive"))
      (node (ref "L10") (pin "1") (pinfunction "1_1") (pintype "passive"))
      (node (ref "L21") (pin "1") (pinfunction "1_1") (pintype "passive"))
      (node (ref "L22") (pin "1") (pinfunction "1_1") (pintype "passive"))
      (node (ref "L23") (pin "1") (pinfunction "1_1") (pintype "passive"))
      (node (ref "L25") (pin "2") (pinfunction "2_2") (pintype "passive"))
      (node (ref "L26") (pin "1") (pinfunction "1_1") (pintype "passive"))
      (node (ref "L27") (pin "1") (pinfunction "1_1") (pintype "passive"))
      (node (ref "L4") (pin "P$2") (pinfunction "2_P$2") (pintype "passive"))
      (node (ref "L64") (pin "2") (pinfunction "2_2") (pintype "passive"))
      (node (ref "L65") (pin "2") (pinfunction "2_2") (pintype "passive"))
      (node (ref "LED1") (pin "A") (pinfunction "A_A") (pintype "passive"))
      (node (ref "LED10") (pin "A") (pinfunction "A_A") (pintype "passive"))
      (node (ref "LED2") (pin "A") (pinfunction "A_A") (pintype "passive"))
      (node (ref "LED3") (pin "A") (pinfunction "A_A") (pintype "passive"))
      (node (ref "LED4") (pin "A") (pinfunction "A_A") (pintype "passive"))
      (node (ref "LED5") (pin "A") (pinfunction "A_A") (pintype "passive"))
      (node (ref "LED6") (pin "A") (pinfunction "A_A") (pintype "passive"))
      (node (ref "LED7") (pin "A") (pinfunction "A_A") (pintype "passive"))
      (node (ref "LED8") (pin "A") (pinfunction "A_A") (pintype "passive"))
      (node (ref "LED9") (pin "A") (pinfunction "A_A") (pintype "passive"))
      (node (ref "R108") (pin "1") (pinfunction "1_1") (pintype "passive"))
      (node (ref "R116") (pin "2") (pinfunction "2_2") (pintype "passive"))
      (node (ref "R117") (pin "2") (pinfunction "2_2") (pintype "passive"))
      (node (ref "R121") (pin "2") (pinfunction "2_2") (pintype "passive"))
      (node (ref "R127") (pin "2") (pinfunction "2_2") (pintype "passive"))
      (node (ref "R128") (pin "2") (pinfunction "2_2") (pintype "passive"))
      (node (ref "R129") (pin "2") (pinfunction "2_2") (pintype "passive"))
      (node (ref "R130") (pin "2") (pinfunction "2_2") (pintype "passive"))
      (node (ref "R132") (pin "2") (pinfunction "2_2") (pintype "passive"))
      (node (ref "TP2") (pin "TP") (pinfunction "TP_TP") (pintype "input"))
      (node (ref "U1") (pin "3") (pinfunction "~{WP}_3") (pintype "input"))
      (node (ref "U1") (pin "7") (pinfunction "~{HOLD}_7") (pintype "input"))
      (node (ref "U1") (pin "8") (pinfunction "VCC_8") (pintype "power_in"))
      (node (ref "U2") (pin "P103") (pinfunction "VCCO_1_P103") (pintype "input"))
      (node (ref "U2") (pin "P122") (pinfunction "VCCO_0_P122") (pintype "input"))
      (node (ref "U2") (pin "P125") (pinfunction "VCCO_0_P125") (pintype "input"))
      (node (ref "U2") (pin "P129") (pinfunction "VCCAUX_P129") (pintype "input"))
      (node (ref "U2") (pin "P135") (pinfunction "VCCO_0_P135") (pintype "input"))
      (node (ref "U2") (pin "P18") (pinfunction "VCCO_3_P18") (pintype "input"))
      (node (ref "U2") (pin "P20") (pinfunction "VCCAUX_P20") (pintype "input"))
      (node (ref "U2") (pin "P31") (pinfunction "VCCO_3_P31") (pintype "input"))
      (node (ref "U2") (pin "P36") (pinfunction "VCCAUX_P36") (pintype "input"))
      (node (ref "U2") (pin "P4") (pinfunction "VCCO_3_P4") (pintype "input"))
      (node (ref "U2") (pin "P42") (pinfunction "VCCO_2_P42") (pintype "input"))
      (node (ref "U2") (pin "P53") (pinfunction "VCCAUX_P53") (pintype "input"))
      (node (ref "U2") (pin "P63") (pinfunction "VCCO_2_P63") (pintype "input"))
      (node (ref "U2") (pin "P69") (pinfunction "IO_L1N_M0_CMPMISO_2_P69") (pintype "bidirectional"))
      (node (ref "U2") (pin "P76") (pinfunction "VCCO_1_P76") (pintype "input"))
      (node (ref "U2") (pin "P86") (pinfunction "VCCO_1_P86") (pintype "input"))
      (node (ref "U2") (pin "P90") (pinfunction "VCCAUX_P90") (pintype "input"))
      (node (ref "Y1") (pin "4") (pinfunction "VDD_4") (pintype "power_in"))
    )
    (net (code "2") (name "+5V") (class "Default")
      (node (ref "C1") (pin "1") (pinfunction "1_1") (pintype "passive"))
      (node (ref "C2") (pin "1") (pinfunction "1_1") (pintype "passive"))
      (node (ref "C3") (pin "1") (pinfunction "1_1") (pintype "passive"))
      (node (ref "C6") (pin "2") (pinfunction "2_2") (pintype "passive"))
      (node (ref "IC1") (pin "10") (pinfunction "VIN_10") (pintype "bidirectional"))
      (node (ref "IC2") (pin "1") (pinfunction "VIN_1") (pintype "bidirectional"))
      (node (ref "IC2") (pin "14") (pinfunction "EN_14") (pintype "bidirectional"))
      (node (ref "IC2") (pin "15") (pinfunction "EN_15") (pintype "bidirectional"))
      (node (ref "IC2") (pin "4") (pinfunction "VDD_4") (pintype "bidirectional"))
      (node (ref "IC2") (pin "8") (pinfunction "VIN_8") (pintype "bidirectional"))
      (node (ref "J1") (pin "1") (pinfunction "1_1") (pintype "passive"))
      (node (ref "L1") (pin "P$1") (pinfunction "1_P$1") (pintype "passive"))
      (node (ref "Q2") (pin "3") (pinfunction "D_3") (pintype "passive"))
    )
    (net (code "3") (name "+5V{slash}1") (class "Default")
      (node (ref "C26") (pin "2") (pinfunction "2_2") (pintype "passive"))
      (node (ref "L12") (pin "2") (pinfunction "2_2") (pintype "passive"))
      (node (ref "L13") (pin "2") (pinfunction "2_2") (pintype "passive"))
      (node (ref "L15") (pin "2") (pinfunction "2_2") (pintype "passive"))
      (node (ref "L16") (pin "2") (pinfunction "2_2") (pintype "passive"))
      (node (ref "L17") (pin "2") (pinfunction "2_2") (pintype "passive"))
      (node (ref "L6") (pin "2") (pinfunction "2_2") (pintype "passive"))
      (node (ref "R60") (pin "1") (pinfunction "1_1") (pintype "passive"))
      (node (ref "TP5") (pin "TP") (pinfunction "TP_TP") (pintype "input"))
    )
    (net (code "4") (name "+5V{slash}2") (class "Default")
      (node (ref "C27") (pin "2") (pinfunction "2_2") (pintype "passive"))
      (node (ref "L54") (pin "2") (pinfunction "2_2") (pintype "passive"))
      (node (ref "L55") (pin "2") (pinfunction "2_2") (pintype "passive"))
      (node (ref "L56") (pin "2") (pinfunction "2_2") (pintype "passive"))
      (node (ref "L57") (pin "2") (pinfunction "2_2") (pintype "passive"))
      (node (ref "L58") (pin "2") (pinfunction "2_2") (pintype "passive"))
      (node (ref "L7") (pin "2") (pinfunction "2_2") (pintype "passive"))
      (node (ref "R87") (pin "1") (pinfunction "1_1") (pintype "passive"))
      (node (ref "TP7") (pin "TP") (pinfunction "TP_TP") (pintype "input"))
    )
    (net (code "5") (name "+5V{slash}3") (class "Default")
      (node (ref "C28") (pin "2") (pinfunction "2_2") (pintype "passive"))
      (node (ref "L59") (pin "2") (pinfunction "2_2") (pintype "passive"))
      (node (ref "L60") (pin "2") (pinfunction "2_2") (pintype "passive"))
      (node (ref "L61") (pin "2") (pinfunction "2_2") (pintype "passive"))
      (node (ref "L62") (pin "2") (pinfunction "2_2") (pintype "passive"))
      (node (ref "L63") (pin "1") (pinfunction "1_1") (pintype "passive"))
      (node (ref "L8") (pin "2") (pinfunction "2_2") (pintype "passive"))
      (node (ref "R101") (pin "1") (pinfunction "1_1") (pintype "passive"))
      (node (ref "TP9") (pin "TP") (pinfunction "TP_TP") (pintype "input"))
    )
    (net (code "6") (name "+5V{slash}4") (class "Default")
      (node (ref "C49") (pin "1") (pinfunction "1_1") (pintype "passive"))
      (node (ref "C50") (pin "1") (pinfunction "1_1") (pintype "passive"))
      (node (ref "C78") (pin "1") (pinfunction "1_1") (pintype "passive"))
      (node (ref "C79") (pin "1") (pinfunction "1_1") (pintype "passive"))
      (node (ref "IC19") (pin "3") (pinfunction "VIN_3") (pintype "power_in"))
      (node (ref "IC20") (pin "1") (pinfunction "VIN_1") (pintype "power_in"))
      (node (ref "IC20") (pin "3") (pinfunction "EN_3") (pintype "input"))
      (node (ref "IC8") (pin "3") (pinfunction "VIN_3") (pintype "power_in"))
      (node (ref "IC9") (pin "1") (pinfunction "VIN_1") (pintype "power_in"))
      (node (ref "IC9") (pin "3") (pinfunction "EN_3") (pintype "input"))
      (node (ref "L9") (pin "2") (pinfunction "2_2") (pintype "passive"))
      (node (ref "TP11") (pin "TP") (pinfunction "TP_TP") (pintype "input"))
    )
    (net (code "7") (name "+6V") (class "Default")
      (node (ref "C16") (pin "1") (pinfunction "1_1") (pintype "passive"))
      (node (ref "C17") (pin "1") (pinfunction "1_1") (pintype "passive"))
      (node (ref "C18") (pin "2") (pinfunction "2_2") (pintype "passive"))
      (node (ref "C19") (pin "2") (pinfunction "2_2") (pintype "passive"))
      (node (ref "C20") (pin "2") (pinfunction "2_2") (pintype "passive"))
      (node (ref "C21") (pin "2") (pinfunction "2_2") (pintype "passive"))
      (node (ref "IC3") (pin "4") (pinfunction "VIN_4") (pintype "bidirectional"))
      (node (ref "IC3") (pin "6") (pinfunction "EN_6") (pintype "bidirectional"))
      (node (ref "IC4") (pin "4") (pinfunction "VIN_4") (pintype "bidirectional"))
      (node (ref "IC4") (pin "6") (pinfunction "EN_6") (pintype "bidirectional"))
      (node (ref "IC5") (pin "4") (pinfunction "VIN_4") (pintype "bidirectional"))
      (node (ref "IC5") (pin "6") (pinfunction "EN_6") (pintype "bidirectional"))
      (node (ref "IC6") (pin "4") (pinfunction "VIN_4") (pintype "bidirectional"))
      (node (ref "IC6") (pin "6") (pinfunction "EN_6") (pintype "bidirectional"))
      (node (ref "L5") (pin "P$2") (pinfunction "2_P$2") (pintype "passive"))
      (node (ref "TP3") (pin "TP") (pinfunction "TP_TP") (pintype "input"))
    )
    (net (code "8") (name "AMP_PWDN") (class "Default")
      (node (ref "C243") (pin "1") (pinfunction "1_1") (pintype "passive"))
      (node (ref "R153") (pin "2") (pinfunction "2_2") (pintype "passive"))
      (node (ref "U2") (pin "P8") (pinfunction "IO_L51P_3_P8") (pintype "bidirectional"))
    )
    (net (code "9") (name "ATT_D0") (class "Default")
      (node (ref "C249") (pin "1") (pinfunction "1_1") (pintype "passive"))
      (node (ref "R156") (pin "2") (pinfunction "2_2") (pintype "passive"))
      (node (ref "U2") (pin "P16") (pinfunction "IO_L43N_GCLK22_IRDY2_3_P16") (pintype "bidirectional"))
    )
    (net (code "10") (name "ATT_D1") (class "Default")
      (node (ref "C251") (pin "1") (pinfunction "1_1") (pintype "passive"))
      (node (ref "R157") (pin "2") (pinfunction "2_2") (pintype "passive"))
      (node (ref "U2") (pin "P15") (pinfunction "IO_L44P_GCLK21_3_P15") (pintype "bidirectional"))
    )
    (net (code "11") (name "ATT_D2") (class "Default")
      (node (ref "C253") (pin "1") (pinfunction "1_1") (pintype "passive"))
      (node (ref "R158") (pin "2") (pinfunction "2_2") (pintype "passive"))
      (node (ref "U2") (pin "P14") (pinfunction "IO_L44N_GCLK20_3_P14") (pintype "bidirectional"))
    )
    (net (code "12") (name "ATT_D3") (class "Default")
      (node (ref "C255") (pin "1") (pinfunction "1_1") (pintype "passive"))
      (node (ref "R159") (pin "2") (pinfunction "2_2") (pintype "passive"))
      (node (ref "U2") (pin "P12") (pinfunction "IO_L49P_3_P12") (pintype "bidirectional"))
    )
    (net (code "13") (name "ATT_D4") (class "Default")
      (node (ref "C262") (pin "1") (pinfunction "1_1") (pintype "passive"))
      (node (ref "R162") (pin "1") (pinfunction "1_1") (pintype "passive"))
      (node (ref "U2") (pin "P11") (pinfunction "IO_L49N_3_P11") (pintype "bidirectional"))
    )
    (net (code "14") (name "ATT_D5") (class "Default")
      (node (ref "C260") (pin "1") (pinfunction "1_1") (pintype "passive"))
      (node (ref "R161") (pin "1") (pinfunction "1_1") (pintype "passive"))
      (node (ref "U2") (pin "P10") (pinfunction "IO_L50P_3_P10") (pintype "bidirectional"))
    )
    (net (code "15") (name "ATT_D6") (class "Default")
      (node (ref "C258") (pin "1") (pinfunction "1_1") (pintype "passive"))
      (node (ref "R160") (pin "1") (pinfunction "1_1") (pintype "passive"))
      (node (ref "U2") (pin "P9") (pinfunction "IO_L50N_3_P9") (pintype "bidirectional"))
    )
    (net (code "16") (name "EN_6V") (class "Default")
      (node (ref "IC1") (pin "11") (pinfunction "EN_11") (pintype "bidirectional"))
      (node (ref "IC37") (pin "25") (pinfunction "PB12_25") (pintype "bidirectional"))
    )
    (net (code "17") (name "FILT_IN_C1") (class "Default")
      (node (ref "C263") (pin "1") (pinfunction "1_1") (pintype "passive"))
      (node (ref "R21") (pin "2") (pinfunction "2_2") (pintype "passive"))
      (node (ref "U2") (pin "P26") (pinfunction "IO_L37N_3_P26") (pintype "bidirectional"))
    )
    (net (code "18") (name "FILT_IN_C2") (class "Default")
      (node (ref "C264") (pin "1") (pinfunction "1_1") (pintype "passive"))
      (node (ref "R20") (pin "2") (pinfunction "2_2") (pintype "passive"))
      (node (ref "U2") (pin "P24") (pinfunction "IO_L41P_GCLK27_3_P24") (pintype "bidirectional"))
    )
    (net (code "19") (name "FILT_OUT_C1") (class "Default")
      (node (ref "C266") (pin "1") (pinfunction "1_1") (pintype "passive"))
      (node (ref "R24") (pin "2") (pinfunction "2_2") (pintype "passive"))
      (node (ref "U2") (pin "P22") (pinfunction "IO_L42P_GCLK25_TRDY2_3_P22") (pintype "bidirectional"))
    )
    (net (code "20") (name "FILT_OUT_C2") (class "Default")
      (node (ref "C265") (pin "1") (pinfunction "1_1") (pintype "passive"))
      (node (ref "R22") (pin "2") (pinfunction "2_2") (pintype "passive"))
      (node (ref "U2") (pin "P23") (pinfunction "IO_L41N_GCLK26_3_P23") (pintype "bidirectional"))
    )
    (net (code "21") (name "FPGA_CCLK") (class "Default")
      (node (ref "R109") (pin "2") (pinfunction "2_2") (pintype "passive"))
      (node (ref "R111") (pin "2") (pinfunction "2_2") (pintype "passive"))
      (node (ref "U2") (pin "P70") (pinfunction "IO_L1P_CCLK_2_P70") (pintype "bidirectional"))
    )
    (net (code "22") (name "FPGA_CLK") (class "Default")
      (node (ref "IC7") (pin "15") (pinfunction "CLK7_15") (pintype "bidirectional"))
      (node (ref "R126") (pin "1") (pinfunction "1_1") (pintype "passive"))
    )
    (net (code "23") (name "FPGA_CSO_B") (class "Default")
      (node (ref "R114") (pin "2") (pinfunction "2_2") (pintype "passive"))
      (node (ref "U2") (pin "P38") (pinfunction "IO_L65N_CSO_B_2_P38") (pintype "bidirectional"))
    )
    (net (code "24") (name "FPGA_DIN") (class "Default")
      (node (ref "R110") (pin "2") (pinfunction "2_2") (pintype "passive"))
      (node (ref "R113") (pin "2") (pinfunction "2_2") (pintype "passive"))
      (node (ref "U2") (pin "P65") (pinfunction "IO_L3P_D0_DIN_MISO_MISO1_2_P65") (pintype "bidirectional"))
    )
    (net (code "25") (name "FPGA_DONE") (class "Default")
      (node (ref "IC37") (pin "47") (pinfunction "PB9_47") (pintype "bidirectional"))
      (node (ref "R129") (pin "1") (pinfunction "1_1") (pintype "passive"))
      (node (ref "U2") (pin "P71") (pinfunction "DONE_2_P71") (pintype "bidirectional"))
    )
    (net (code "26") (name "FPGA_INIT_B") (class "Default")
      (node (ref "IC37") (pin "6") (pinfunction "PF1-OSC_OUT_6") (pintype "bidirectional"))
      (node (ref "R128") (pin "1") (pinfunction "1_1") (pintype "passive"))
      (node (ref "U2") (pin "P39") (pinfunction "IO_L65P_INIT_B_2_P39") (pintype "bidirectional"))
    )
    (net (code "27") (name "FPGA_M1") (class "Default")
      (node (ref "R108") (pin "2") (pinfunction "2_2") (pintype "passive"))
      (node (ref "R115") (pin "1") (pinfunction "1_1") (pintype "passive"))
      (node (ref "U2") (pin "P60") (pinfunction "IO_L13P_M1_2_P60") (pintype "bidirectional"))
    )
    (net (code "28") (name "FPGA_MOSI") (class "Default")
      (node (ref "R112") (pin "2") (pinfunction "2_2") (pintype "passive"))
      (node (ref "U2") (pin "P64") (pinfunction "IO_L3N_MOSI_CSI_B_MISO0_2_P64") (pintype "bidirectional"))
    )
    (net (code "29") (name "FPGA_PROGRAM_B") (class "Default")
      (node (ref "IC37") (pin "19") (pinfunction "PB2_19") (pintype "bidirectional"))
      (node (ref "R127") (pin "1") (pinfunction "1_1") (pintype "passive"))
      (node (ref "U2") (pin "P37") (pinfunction "PROGRAM_B_2_P37") (pintype "input"))
    )
    (net (code "30") (name "FPGA_RESET") (class "Default")
      (node (ref "IC37") (pin "45") (pinfunction "PB7_45") (pintype "bidirectional"))
      (node (ref "U2") (pin "P72") (pinfunction "CMPCS_B_2_P72") (pintype "bidirectional"))
    )
    (net (code "31") (name "GND") (class "Default")
      (node (ref "C1") (pin "2") (pinfunction "2_2") (pintype "passive"))
      (node (ref "C10") (pin "2") (pinfunction "2_2") (pintype "passive"))
      (node (ref "C102") (pin "1") (pinfunction "1_1") (pintype "passive"))
      (node (ref "C103") (pin "1") (pinfunction "1_1") (pintype "passive"))
      (node (ref "C104") (pin "2") (pinfunction "2_2") (pintype "passive"))
      (node (ref "C105") (pin "2") (pinfunction "2_2") (pintype "passive"))
      (node (ref "C106") (pin "2") (pinfunction "2_2") (pintype "passive"))
      (node (ref "C108") (pin "2") (pinfunction "2_2") (pintype "passive"))
      (node (ref "C11") (pin "2") (pinfunction "2_2") (pintype "passive"))
      (node (ref "C111") (pin "2") (pinfunction "2_2") (pintype "passive"))
      (node (ref "C115") (pin "1") (pinfunction "1_1") (pintype "passive"))
      (node (ref "C116") (pin "2") (pinfunction "2_2") (pintype "passive"))
      (node (ref "C117") (pin "2") (pinfunction "2_2") (pintype "passive"))
      (node (ref "C118") (pin "1") (pinfunction "1_1") (pintype "passive"))
      (node (ref "C119") (pin "2") (pinfunction "2_2") (pintype "passive"))
      (node (ref "C12") (pin "2") (pinfunction "2_2") (pintype "passive"))
      (node (ref "C122") (pin "2") (pinfunction "2_2") (pintype "passive"))
      (node (ref "C125") (pin "1") (pinfunction "1_1") (pintype "passive"))
      (node (ref "C127") (pin "2") (pinfunction "2_2") (pintype "passive"))
      (node (ref "C129") (pin "2") (pinfunction "2_2") (pintype "passive"))
      (node (ref "C13") (pin "2") (pinfunction "2_2") (pintype "passive"))
      (node (ref "C131") (pin "2") (pinfunction "2_2") (pintype "passive"))
      (node (ref "C132") (pin "1") (pinfunction "1_1") (pintype "passive"))
      (node (ref "C134") (pin "1") (pinfunction "1_1") (pintype "passive"))
      (node (ref "C139") (pin "1") (pinfunction "1_1") (pintype "passive"))
      (node (ref "C14") (pin "2") (pinfunction "2_2") (pintype "passive"))
      (node (ref "C140") (pin "1") (pinfunction "1_1") (pintype "passive"))
      (node (ref "C141") (pin "2") (pinfunction "2_2") (pintype "passive"))
      (node (ref "C142") (pin "2") (pinfunction "2_2") (pintype "passive"))
      (node (ref "C143") (pin "2") (pinfunction "2_2") (pintype "passive"))
      (node (ref "C145") (pin "2") (pinfunction "2_2") (pintype "passive"))
      (node (ref "C148") (pin "2") (pinfunction "2_2") (pintype "passive"))
      (node (ref "C15") (pin "2") (pinfunction "2_2") (pintype "passive"))
      (node (ref "C152") (pin "1") (pinfunction "1_1") (pintype "passive"))
      (node (ref "C153") (pin "2") (pinfunction "2_2") (pintype "passive"))
      (node (ref "C154") (pin "2") (pinfunction "2_2") (pintype "passive"))
      (node (ref "C155") (pin "1") (pinfunction "1_1") (pintype "passive"))
      (node (ref "C156") (pin "2") (pinfunction "2_2") (pintype "passive"))
      (node (ref "C159") (pin "2") (pinfunction "2_2") (pintype "passive"))
      (node (ref "C16") (pin "2") (pinfunction "2_2") (pintype "passive"))
      (node (ref "C162") (pin "1") (pinfunction "1_1") (pintype "passive"))
      (node (ref "C164") (pin "2") (pinfunction "2_2") (pintype "passive"))
      (node (ref "C166") (pin "2") (pinfunction "2_2") (pintype "passive"))
      (node (ref "C168") (pin "2") (pinfunction "2_2") (pintype "passive"))
      (node (ref "C169") (pin "1") (pinfunction "1_1") (pintype "passive"))
      (node (ref "C17") (pin "2") (pinfunction "2_2") (pintype "passive"))
      (node (ref "C171") (pin "2") (pinfunction "2_2") (pintype "passive"))
      (node (ref "C172") (pin "2") (pinfunction "2_2") (pintype "passive"))
      (node (ref "C175") (pin "2") (pinfunction "2_2") (pintype "passive"))
      (node (ref "C177") (pin "2") (pinfunction "2_2") (pintype "passive"))
      (node (ref "C18") (pin "1") (pinfunction "1_1") (pintype "passive"))
      (node (ref "C180") (pin "2") (pinfunction "2_2") (pintype "passive"))
      (node (ref "C181") (pin "1") (pinfunction "1_1") (pintype "passive"))
      (node (ref "C182") (pin "2") (pinfunction "2_2") (pintype "passive"))
      (node (ref "C185") (pin "2") (pinfunction "2_2") (pintype "passive"))
      (node (ref "C186") (pin "1") (pinfunction "1_1") (pintype "passive"))
      (node (ref "C187") (pin "1") (pinfunction "1_1") (pintype "passive"))
      (node (ref "C189") (pin "2") (pinfunction "2_2") (pintype "passive"))
      (node (ref "C19") (pin "1") (pinfunction "1_1") (pintype "passive"))
      (node (ref "C190") (pin "2") (pinfunction "2_2") (pintype "passive"))
      (node (ref "C193") (pin "2") (pinfunction "2_2") (pintype "passive"))
      (node (ref "C195") (pin "2") (pinfunction "2_2") (pintype "passive"))
      (node (ref "C198") (pin "2") (pinfunction "2_2") (pintype "passive"))
      (node (ref "C199") (pin "1") (pinfunction "1_1") (pintype "passive"))
      (node (ref "C2") (pin "2") (pinfunction "2_2") (pintype "passive"))
      (node (ref "C20") (pin "1") (pinfunction "1_1") (pintype "passive"))
      (node (ref "C201") (pin "1") (pinfunction "1_1") (pintype "passive"))
      (node (ref "C204") (pin "1") (pinfunction "1_1") (pintype "passive"))
      (node (ref "C205") (pin "1") (pinfunction "1_1") (pintype "passive"))
      (node (ref "C206") (pin "2") (pinfunction "2_2") (pintype "passive"))
      (node (ref "C207") (pin "2") (pinfunction "2_2") (pintype "passive"))
      (node (ref "C208") (pin "2") (pinfunction "2_2") (pintype "passive"))
      (node (ref "C209") (pin "2") (pinfunction "2_2") (pintype "passive"))
      (node (ref "C21") (pin "1") (pinfunction "1_1") (pintype "passive"))
      (node (ref "C210") (pin "2") (pinfunction "2_2") (pintype "passive"))
      (node (ref "C211") (pin "2") (pinfunction "2_2") (pintype "passive"))
      (node (ref "C212") (pin "2") (pinfunction "2_2") (pintype "passive"))
      (node (ref "C213") (pin "2") (pinfunction "2_2") (pintype "passive"))
      (node (ref "C214") (pin "2") (pinfunction "2_2") (pintype "passive"))
      (node (ref "C215") (pin "2") (pinfunction "2_2") (pintype "passive"))
      (node (ref "C216") (pin "2") (pinfunction "2_2") (pintype "passive"))
      (node (ref "C217") (pin "2") (pinfunction "2_2") (pintype "passive"))
      (node (ref "C218") (pin "2") (pinfunction "2_2") (pintype "passive"))
      (node (ref "C219") (pin "2") (pinfunction "2_2") (pintype "passive"))
      (node (ref "C22") (pin "1") (pinfunction "1_1") (pintype "passive"))
      (node (ref "C220") (pin "2") (pinfunction "2_2") (pintype "passive"))
      (node (ref "C221") (pin "2") (pinfunction "2_2") (pintype "passive"))
      (node (ref "C222") (pin "2") (pinfunction "2_2") (pintype "passive"))
      (node (ref "C223") (pin "2") (pinfunction "2_2") (pintype "passive"))
      (node (ref "C224") (pin "2") (pinfunction "2_2") (pintype "passive"))
      (node (ref "C225") (pin "2") (pinfunction "2_2") (pintype "passive"))
      (node (ref "C226") (pin "2") (pinfunction "2_2") (pintype "passive"))
      (node (ref "C227") (pin "2") (pinfunction "2_2") (pintype "passive"))
      (node (ref "C228") (pin "2") (pinfunction "2_2") (pintype "passive"))
      (node (ref "C229") (pin "2") (pinfunction "2_2") (pintype "passive"))
      (node (ref "C23") (pin "1") (pinfunction "1_1") (pintype "passive"))
      (node (ref "C230") (pin "2") (pinfunction "2_2") (pintype "passive"))
      (node (ref "C231") (pin "2") (pinfunction "2_2") (pintype "passive"))
      (node (ref "C232") (pin "2") (pinfunction "2_2") (pintype "passive"))
      (node (ref "C233") (pin "2") (pinfunction "2_2") (pintype "passive"))
      (node (ref "C234") (pin "2") (pinfunction "2_2") (pintype "passive"))
      (node (ref "C235") (pin "2") (pinfunction "2_2") (pintype "passive"))
      (node (ref "C236") (pin "2") (pinfunction "2_2") (pintype "passive"))
      (node (ref "C237") (pin "2") (pinfunction "2_2") (pintype "passive"))
      (node (ref "C238") (pin "2") (pinfunction "2_2") (pintype "passive"))
      (node (ref "C239") (pin "2") (pinfunction "2_2") (pintype "passive"))
      (node (ref "C24") (pin "1") (pinfunction "1_1") (pintype "passive"))
      (node (ref "C240") (pin "2") (pinfunction "2_2") (pintype "passive"))
      (node (ref "C241") (pin "2") (pinfunction "2_2") (pintype "passive"))
      (node (ref "C242") (pin "2") (pinfunction "2_2") (pintype "passive"))
      (node (ref "C243") (pin "2") (pinfunction "2_2") (pintype "passive"))
      (node (ref "C244") (pin "2") (pinfunction "2_2") (pintype "passive"))
      (node (ref "C245") (pin "2") (pinfunction "2_2") (pintype "passive"))
      (node (ref "C246") (pin "2") (pinfunction "2_2") (pintype "passive"))
      (node (ref "C247") (pin "2") (pinfunction "2_2") (pintype "passive"))
      (node (ref "C248") (pin "2") (pinfunction "2_2") (pintype "passive"))
      (node (ref "C249") (pin "2") (pinfunction "2_2") (pintype "passive"))
      (node (ref "C25") (pin "1") (pinfunction "1_1") (pintype "passive"))
      (node (ref "C250") (pin "2") (pinfunction "2_2") (pintype "passive"))
      (node (ref "C251") (pin "2") (pinfunction "2_2") (pintype "passive"))
      (node (ref "C252") (pin "2") (pinfunction "2_2") (pintype "passive"))
      (node (ref "C253") (pin "2") (pinfunction "2_2") (pintype "passive"))
      (node (ref "C254") (pin "2") (pinfunction "2_2") (pintype "passive"))
      (node (ref "C255") (pin "2") (pinfunction "2_2") (pintype "passive"))
      (node (ref "C256") (pin "2") (pinfunction "2_2") (pintype "passive"))
      (node (ref "C257") (pin "2") (pinfunction "2_2") (pintype "passive"))
      (node (ref "C258") (pin "2") (pinfunction "2_2") (pintype "passive"))
      (node (ref "C259") (pin "2") (pinfunction "2_2") (pintype "passive"))
      (node (ref "C26") (pin "1") (pinfunction "1_1") (pintype "passive"))
      (node (ref "C260") (pin "2") (pinfunction "2_2") (pintype "passive"))
      (node (ref "C261") (pin "2") (pinfunction "2_2") (pintype "passive"))
      (node (ref "C262") (pin "2") (pinfunction "2_2") (pintype "passive"))
      (node (ref "C263") (pin "2") (pinfunction "2_2") (pintype "passive"))
      (node (ref "C264") (pin "2") (pinfunction "2_2") (pintype "passive"))
      (node (ref "C265") (pin "2") (pinfunction "2_2") (pintype "passive"))
      (node (ref "C266") (pin "2") (pinfunction "2_2") (pintype "passive"))
      (node (ref "C267") (pin "2") (pinfunction "2_2") (pintype "passive"))
      (node (ref "C268") (pin "2") (pinfunction "2_2") (pintype "passive"))
      (node (ref "C27") (pin "1") (pinfunction "1_1") (pintype "passive"))
      (node (ref "C271") (pin "2") (pinfunction "2_2") (pintype "passive"))
      (node (ref "C272") (pin "2") (pinfunction "2_2") (pintype "passive"))
      (node (ref "C273") (pin "2") (pinfunction "2_2") (pintype "passive"))
      (node (ref "C274") (pin "2") (pinfunction "2_2") (pintype "passive"))
      (node (ref "C28") (pin "1") (pinfunction "1_1") (pintype "passive"))
      (node (ref "C29") (pin "1") (pinfunction "1_1") (pintype "passive"))
      (node (ref "C3") (pin "2") (pinfunction "2_2") (pintype "passive"))
      (node (ref "C31") (pin "1") (pinfunction "1_1") (pintype "passive"))
      (node (ref "C32") (pin "1") (pinfunction "1_1") (pintype "passive"))
      (node (ref "C33") (pin "1") (pinfunction "1_1") (pintype "passive"))
      (node (ref "C35") (pin "2") (pinfunction "2_2") (pintype "passive"))
      (node (ref "C36") (pin "2") (pinfunction "2_2") (pintype "passive"))
      (node (ref "C37") (pin "2") (pinfunction "2_2") (pintype "passive"))
      (node (ref "C38") (pin "2") (pinfunction "2_2") (pintype "passive"))
      (node (ref "C4") (pin "1") (pinfunction "1_1") (pintype "passive"))
      (node (ref "C40") (pin "2") (pinfunction "2_2") (pintype "passive"))
      (node (ref "C41") (pin "2") (pinfunction "2_2") (pintype "passive"))
      (node (ref "C42") (pin "2") (pinfunction "2_2") (pintype "passive"))
      (node (ref "C43") (pin "2") (pinfunction "2_2") (pintype "passive"))
      (node (ref "C44") (pin "2") (pinfunction "2_2") (pintype "passive"))
      (node (ref "C45") (pin "2") (pinfunction "2_2") (pintype "passive"))
      (node (ref "C46") (pin "2") (pinfunction "2_2") (pintype "passive"))
      (node (ref "C47") (pin "2") (pinfunction "2_2") (pintype "passive"))
      (node (ref "C49") (pin "2") (pinfunction "2_2") (pintype "passive"))
      (node (ref "C5") (pin "1") (pinfunction "1_1") (pintype "passive"))
      (node (ref "C50") (pin "2") (pinfunction "2_2") (pintype "passive"))
      (node (ref "C52") (pin "2") (pinfunction "2_2") (pintype "passive"))
      (node (ref "C53") (pin "2") (pinfunction "2_2") (pintype "passive"))
      (node (ref "C54") (pin "2") (pinfunction "2_2") (pintype "passive"))
      (node (ref "C55") (pin "2") (pinfunction "2_2") (pintype "passive"))
      (node (ref "C56") (pin "2") (pinfunction "2_2") (pintype "passive"))
      (node (ref "C57") (pin "2") (pinfunction "2_2") (pintype "passive"))
      (node (ref "C58") (pin "2") (pinfunction "2_2") (pintype "passive"))
      (node (ref "C59") (pin "2") (pinfunction "2_2") (pintype "passive"))
      (node (ref "C6") (pin "1") (pinfunction "1_1") (pintype "passive"))
      (node (ref "C60") (pin "2") (pinfunction "2_2") (pintype "passive"))
      (node (ref "C61") (pin "2") (pinfunction "2_2") (pintype "passive"))
      (node (ref "C63") (pin "2") (pinfunction "2_2") (pintype "passive"))
      (node (ref "C64") (pin "2") (pinfunction "2_2") (pintype "passive"))
      (node (ref "C67") (pin "1") (pinfunction "1_1") (pintype "passive"))
      (node (ref "C69") (pin "2") (pinfunction "2_2") (pintype "passive"))
      (node (ref "C7") (pin "2") (pinfunction "2_2") (pintype "passive"))
      (node (ref "C70") (pin "2") (pinfunction "2_2") (pintype "passive"))
      (node (ref "C72") (pin "2") (pinfunction "2_2") (pintype "passive"))
      (node (ref "C73") (pin "2") (pinfunction "2_2") (pintype "passive"))
      (node (ref "C75") (pin "2") (pinfunction "2_2") (pintype "passive"))
      (node (ref "C76") (pin "2") (pinfunction "2_2") (pintype "passive"))
      (node (ref "C77") (pin "2") (pinfunction "2_2") (pintype "passive"))
      (node (ref "C78") (pin "2") (pinfunction "2_2") (pintype "passive"))
      (node (ref "C79") (pin "2") (pinfunction "2_2") (pintype "passive"))
      (node (ref "C8") (pin "2") (pinfunction "2_2") (pintype "passive"))
      (node (ref "C81") (pin "2") (pinfunction "2_2") (pintype "passive"))
      (node (ref "C82") (pin "2") (pinfunction "2_2") (pintype "passive"))
      (node (ref "C83") (pin "2") (pinfunction "2_2") (pintype "passive"))
      (node (ref "C84") (pin "2") (pinfunction "2_2") (pintype "passive"))
      (node (ref "C85") (pin "2") (pinfunction "2_2") (pintype "passive"))
      (node (ref "C86") (pin "2") (pinfunction "2_2") (pintype "passive"))
      (node (ref "C87") (pin "2") (pinfunction "2_2") (pintype "passive"))
      (node (ref "C88") (pin "2") (pinfunction "2_2") (pintype "passive"))
      (node (ref "C89") (pin "2") (pinfunction "2_2") (pintype "passive"))
      (node (ref "C90") (pin "2") (pinfunction "2_2") (pintype "passive"))
      (node (ref "C91") (pin "2") (pinfunction "2_2") (pintype "passive"))
      (node (ref "C94") (pin "2") (pinfunction "2_2") (pintype "passive"))
      (node (ref "C95") (pin "1") (pinfunction "1_1") (pintype "passive"))
      (node (ref "C97") (pin "1") (pinfunction "1_1") (pintype "passive"))
      (node (ref "IC1") (pin "13") (pinfunction "PGND_13") (pintype "bidirectional"))
      (node (ref "IC1") (pin "4") (pinfunction "AGND_4") (pintype "bidirectional"))
      (node (ref "IC1") (pin "5") (pinfunction "PGND_5") (pintype "bidirectional"))
      (node (ref "IC1") (pin "6") (pinfunction "PGND_6") (pintype "bidirectional"))
      (node (ref "IC10") (pin "11") (pinfunction "GND_RF_11") (pintype "bidirectional"))
      (node (ref "IC10") (pin "18") (pinfunction "GND_VCO_18") (pintype "bidirectional"))
      (node (ref "IC10") (pin "21") (pinfunction "GND_TUNE_21") (pintype "bidirectional"))
      (node (ref "IC10") (pin "27") (pinfunction "GND_DIG_27") (pintype "bidirectional"))
      (node (ref "IC10") (pin "31") (pinfunction "GND_SD_31") (pintype "bidirectional"))
      (node (ref "IC10") (pin "33") (pinfunction "EP_33") (pintype "bidirectional"))
      (node (ref "IC10") (pin "8") (pinfunction "GND_CP_8") (pintype "bidirectional"))
      (node (ref "IC10") (pin "9") (pinfunction "GND_PLL_9") (pintype "bidirectional"))
      (node (ref "IC11") (pin "10") (pinfunction "GND_10") (pintype "bidirectional"))
      (node (ref "IC11") (pin "12") (pinfunction "GND_12") (pintype "bidirectional"))
      (node (ref "IC11") (pin "13") (pinfunction "GND_13") (pintype "bidirectional"))
      (node (ref "IC11") (pin "5") (pinfunction "GND_5") (pintype "bidirectional"))
      (node (ref "IC11") (pin "8") (pinfunction "GND_8") (pintype "bidirectional"))
      (node (ref "IC12") (pin "10") (pinfunction "GND_10") (pintype "bidirectional"))
      (node (ref "IC12") (pin "12") (pinfunction "GND_12") (pintype "bidirectional"))
      (node (ref "IC12") (pin "13") (pinfunction "GND_13") (pintype "bidirectional"))
      (node (ref "IC12") (pin "5") (pinfunction "GND_5") (pintype "bidirectional"))
      (node (ref "IC12") (pin "8") (pinfunction "GND_8") (pintype "bidirectional"))
      (node (ref "IC13") (pin "1") (pinfunction "GND_1") (pintype "bidirectional"))
      (node (ref "IC13") (pin "10") (pinfunction "GND_10") (pintype "bidirectional"))
      (node (ref "IC13") (pin "11") (pinfunction "GND_11") (pintype "bidirectional"))
      (node (ref "IC13") (pin "12") (pinfunction "GND_12") (pintype "bidirectional"))
      (node (ref "IC13") (pin "14") (pinfunction "GND_14") (pintype "bidirectional"))
      (node (ref "IC13") (pin "15") (pinfunction "GND_15") (pintype "bidirectional"))
      (node (ref "IC13") (pin "18") (pinfunction "GND_18") (pintype "bidirectional"))
      (node (ref "IC13") (pin "19") (pinfunction "GND_19") (pintype "bidirectional"))
      (node (ref "IC13") (pin "2") (pinfunction "GND_2") (pintype "bidirectional"))
      (node (ref "IC13") (pin "21") (pinfunction "GND_21") (pintype "bidirectional"))
      (node (ref "IC13") (pin "4") (pinfunction "GND_4") (pintype "bidirectional"))
      (node (ref "IC13") (pin "5") (pinfunction "GND_5") (pintype "bidirectional"))
      (node (ref "IC13") (pin "6") (pinfunction "GND_6") (pintype "bidirectional"))
      (node (ref "IC13") (pin "7") (pinfunction "GND_7") (pintype "bidirectional"))
      (node (ref "IC13") (pin "9") (pinfunction "GND_9") (pintype "bidirectional"))
      (node (ref "IC14") (pin "10") (pinfunction "GND_10") (pintype "bidirectional"))
      (node (ref "IC14") (pin "11") (pinfunction "GND_11") (pintype "bidirectional"))
      (node (ref "IC14") (pin "12") (pinfunction "GND_12") (pintype "bidirectional"))
      (node (ref "IC14") (pin "13") (pinfunction "GND_13") (pintype "bidirectional"))
      (node (ref "IC14") (pin "15") (pinfunction "GND_15") (pintype "bidirectional"))
      (node (ref "IC14") (pin "25") (pinfunction "GND_25") (pintype "bidirectional"))
      (node (ref "IC14") (pin "3") (pinfunction "MODE_3") (pintype "bidirectional"))
      (node (ref "IC14") (pin "4") (pinfunction "GND_4") (pintype "bidirectional"))
      (node (ref "IC14") (pin "6") (pinfunction "GND_6") (pintype "bidirectional"))
      (node (ref "IC14") (pin "7") (pinfunction "GND_7") (pintype "bidirectional"))
      (node (ref "IC14") (pin "8") (pinfunction "GND_8") (pintype "bidirectional"))
      (node (ref "IC14") (pin "9") (pinfunction "GND_9") (pintype "bidirectional"))
      (node (ref "IC15") (pin "3") (pinfunction "GND_3") (pintype "bidirectional"))
      (node (ref "IC15") (pin "4") (pinfunction "GND_4") (pintype "bidirectional"))
      (node (ref "IC15") (pin "6") (pinfunction "GND_6") (pintype "bidirectional"))
      (node (ref "IC15") (pin "8") (pinfunction "GND_8") (pintype "bidirectional"))
      (node (ref "IC15") (pin "9") (pinfunction "GND_9") (pintype "bidirectional"))
      (node (ref "IC16") (pin "1") (pinfunction "GND_1") (pintype "bidirectional"))
      (node (ref "IC16") (pin "10") (pinfunction "GND_10") (pintype "bidirectional"))
      (node (ref "IC16") (pin "11") (pinfunction "GND_11") (pintype "bidirectional"))
      (node (ref "IC16") (pin "12") (pinfunction "GND_12") (pintype "bidirectional"))
      (node (ref "IC16") (pin "14") (pinfunction "GND_14") (pintype "bidirectional"))
      (node (ref "IC16") (pin "15") (pinfunction "GND_15") (pintype "bidirectional"))
      (node (ref "IC16") (pin "18") (pinfunction "GND_18") (pintype "bidirectional"))
      (node (ref "IC16") (pin "19") (pinfunction "GND_19") (pintype "bidirectional"))
      (node (ref "IC16") (pin "2") (pinfunction "GND_2") (pintype "bidirectional"))
      (node (ref "IC16") (pin "21") (pinfunction "GND_21") (pintype "bidirectional"))
      (node (ref "IC16") (pin "4") (pinfunction "GND_4") (pintype "bidirectional"))
      (node (ref "IC16") (pin "5") (pinfunction "GND_5") (pintype "bidirectional"))
      (node (ref "IC16") (pin "6") (pinfunction "GND_6") (pintype "bidirectional"))
      (node (ref "IC16") (pin "7") (pinfunction "GND_7") (pintype "bidirectional"))
      (node (ref "IC16") (pin "9") (pinfunction "GND_9") (pintype "bidirectional"))
      (node (ref "IC17") (pin "1") (pinfunction "GND_1") (pintype "bidirectional"))
      (node (ref "IC17") (pin "10") (pinfunction "GND_10") (pintype "bidirectional"))
      (node (ref "IC17") (pin "11") (pinfunction "GND_11") (pintype "bidirectional"))
      (node (ref "IC17") (pin "12") (pinfunction "GND_12") (pintype "bidirectional"))
      (node (ref "IC17") (pin "14") (pinfunction "GND_14") (pintype "bidirectional"))
      (node (ref "IC17") (pin "15") (pinfunction "GND_15") (pintype "bidirectional"))
      (node (ref "IC17") (pin "16") (pinfunction "CTL2_16") (pintype "bidirectional"))
      (node (ref "IC17") (pin "18") (pinfunction "GND_18") (pintype "bidirectional"))
      (node (ref "IC17") (pin "19") (pinfunction "GND_19") (pintype "bidirectional"))
      (node (ref "IC17") (pin "2") (pinfunction "GND_2") (pintype "bidirectional"))
      (node (ref "IC17") (pin "21") (pinfunction "GND_21") (pintype "bidirectional"))
      (node (ref "IC17") (pin "4") (pinfunction "GND_4") (pintype "bidirectional"))
      (node (ref "IC17") (pin "5") (pinfunction "GND_5") (pintype "bidirectional"))
      (node (ref "IC17") (pin "6") (pinfunction "GND_6") (pintype "bidirectional"))
      (node (ref "IC17") (pin "7") (pinfunction "GND_7") (pintype "bidirectional"))
      (node (ref "IC17") (pin "9") (pinfunction "GND_9") (pintype "bidirectional"))
      (node (ref "IC18") (pin "1") (pinfunction "GND_1") (pintype "bidirectional"))
      (node (ref "IC18") (pin "10") (pinfunction "GND_10") (pintype "bidirectional"))
      (node (ref "IC18") (pin "11") (pinfunction "GND_11") (pintype "bidirectional"))
      (node (ref "IC18") (pin "12") (pinfunction "GND_12") (pintype "bidirectional"))
      (node (ref "IC18") (pin "14") (pinfunction "GND_14") (pintype "bidirectional"))
      (node (ref "IC18") (pin "15") (pinfunction "GND_15") (pintype "bidirectional"))
      (node (ref "IC18") (pin "16") (pinfunction "CTL2_16") (pintype "bidirectional"))
      (node (ref "IC18") (pin "18") (pinfunction "GND_18") (pintype "bidirectional"))
      (node (ref "IC18") (pin "19") (pinfunction "GND_19") (pintype "bidirectional"))
      (node (ref "IC18") (pin "2") (pinfunction "GND_2") (pintype "bidirectional"))
      (node (ref "IC18") (pin "21") (pinfunction "GND_21") (pintype "bidirectional"))
      (node (ref "IC18") (pin "4") (pinfunction "GND_4") (pintype "bidirectional"))
      (node (ref "IC18") (pin "5") (pinfunction "GND_5") (pintype "bidirectional"))
      (node (ref "IC18") (pin "6") (pinfunction "GND_6") (pintype "bidirectional"))
      (node (ref "IC18") (pin "7") (pinfunction "GND_7") (pintype "bidirectional"))
      (node (ref "IC18") (pin "9") (pinfunction "GND_9") (pintype "bidirectional"))
      (node (ref "IC19") (pin "1") (pinfunction "GND_1") (pintype "power_in"))
      (node (ref "IC2") (pin "17") (pinfunction "SGND_17") (pintype "bidirectional"))
      (node (ref "IC2") (pin "3") (pinfunction "PGND_3") (pintype "bidirectional"))
      (node (ref "IC2") (pin "5") (pinfunction "SGND_5") (pintype "bidirectional"))
      (node (ref "IC2") (pin "6") (pinfunction "PGND_6") (pintype "bidirectional"))
      (node (ref "IC20") (pin "2") (pinfunction "GND_2") (pintype "power_in"))
      (node (ref "IC21") (pin "11") (pinfunction "GND_RF_11") (pintype "bidirectional"))
      (node (ref "IC21") (pin "18") (pinfunction "GND_VCO_18") (pintype "bidirectional"))
      (node (ref "IC21") (pin "21") (pinfunction "GND_TUNE_21") (pintype "bidirectional"))
      (node (ref "IC21") (pin "27") (pinfunction "GND_DIG_27") (pintype "bidirectional"))
      (node (ref "IC21") (pin "31") (pinfunction "GND_SD_31") (pintype "bidirectional"))
      (node (ref "IC21") (pin "33") (pinfunction "EP_33") (pintype "bidirectional"))
      (node (ref "IC21") (pin "8") (pinfunction "GND_CP_8") (pintype "bidirectional"))
      (node (ref "IC21") (pin "9") (pinfunction "GND_PLL_9") (pintype "bidirectional"))
      (node (ref "IC22") (pin "9") (pinfunction "GND_9") (pintype "bidirectional"))
      (node (ref "IC23") (pin "6") (pinfunction "V-_6") (pintype "power_in"))
      (node (ref "IC24") (pin "1") (pinfunction "GND_1") (pintype "bidirectional"))
      (node (ref "IC24") (pin "12") (pinfunction "GND_12") (pintype "bidirectional"))
      (node (ref "IC24") (pin "14") (pinfunction "GND_14") (pintype "bidirectional"))
      (node (ref "IC24") (pin "17") (pinfunction "GND_17") (pintype "bidirectional"))
      (node (ref "IC24") (pin "19") (pinfunction "GND_19") (pintype "bidirectional"))
      (node (ref "IC24") (pin "2") (pinfunction "GND_2") (pintype "bidirectional"))
      (node (ref "IC24") (pin "23") (pinfunction "GND_23") (pintype "bidirectional"))
      (node (ref "IC24") (pin "25") (pinfunction "GND_25") (pintype "bidirectional"))
      (node (ref "IC24") (pin "5") (pinfunction "GND_5") (pintype "bidirectional"))
      (node (ref "IC24") (pin "6") (pinfunction "GND_6") (pintype "bidirectional"))
      (node (ref "IC24") (pin "8") (pinfunction "GND_8") (pintype "bidirectional"))
      (node (ref "IC25") (pin "2") (pinfunction "GND_2") (pintype "power_in"))
      (node (ref "IC26") (pin "5") (pinfunction "GND_5") (pintype "bidirectional"))
      (node (ref "IC27") (pin "9") (pinfunction "GND_9") (pintype "bidirectional"))
      (node (ref "IC28") (pin "6") (pinfunction "V-_6") (pintype "power_in"))
      (node (ref "IC29") (pin "1") (pinfunction "GND_1") (pintype "bidirectional"))
      (node (ref "IC29") (pin "12") (pinfunction "GND_12") (pintype "bidirectional"))
      (node (ref "IC29") (pin "14") (pinfunction "GND_14") (pintype "bidirectional"))
      (node (ref "IC29") (pin "17") (pinfunction "GND_17") (pintype "bidirectional"))
      (node (ref "IC29") (pin "19") (pinfunction "GND_19") (pintype "bidirectional"))
      (node (ref "IC29") (pin "2") (pinfunction "GND_2") (pintype "bidirectional"))
      (node (ref "IC29") (pin "23") (pinfunction "GND_23") (pintype "bidirectional"))
      (node (ref "IC29") (pin "25") (pinfunction "GND_25") (pintype "bidirectional"))
      (node (ref "IC29") (pin "5") (pinfunction "GND_5") (pintype "bidirectional"))
      (node (ref "IC29") (pin "6") (pinfunction "GND_6") (pintype "bidirectional"))
      (node (ref "IC29") (pin "8") (pinfunction "GND_8") (pintype "bidirectional"))
      (node (ref "IC3") (pin "1") (pinfunction "GND_1") (pintype "bidirectional"))
      (node (ref "IC3") (pin "7") (pinfunction "GND_7") (pintype "bidirectional"))
      (node (ref "IC30") (pin "2") (pinfunction "GND_2") (pintype "power_in"))
      (node (ref "IC31") (pin "5") (pinfunction "GND_5") (pintype "bidirectional"))
      (node (ref "IC32") (pin "6") (pinfunction "V-_6") (pintype "power_in"))
      (node (ref "IC33") (pin "1") (pinfunction "GND_1") (pintype "bidirectional"))
      (node (ref "IC33") (pin "12") (pinfunction "GND_12") (pintype "bidirectional"))
      (node (ref "IC33") (pin "14") (pinfunction "GND_14") (pintype "bidirectional"))
      (node (ref "IC33") (pin "17") (pinfunction "GND_17") (pintype "bidirectional"))
      (node (ref "IC33") (pin "19") (pinfunction "GND_19") (pintype "bidirectional"))
      (node (ref "IC33") (pin "2") (pinfunction "GND_2") (pintype "bidirectional"))
      (node (ref "IC33") (pin "23") (pinfunction "GND_23") (pintype "bidirectional"))
      (node (ref "IC33") (pin "25") (pinfunction "GND_25") (pintype "bidirectional"))
      (node (ref "IC33") (pin "5") (pinfunction "GND_5") (pintype "bidirectional"))
      (node (ref "IC33") (pin "6") (pinfunction "GND_6") (pintype "bidirectional"))
      (node (ref "IC33") (pin "8") (pinfunction "GND_8") (pintype "bidirectional"))
      (node (ref "IC34") (pin "2") (pinfunction "GND_2") (pintype "power_in"))
      (node (ref "IC35") (pin "5") (pinfunction "GND_5") (pintype "bidirectional"))
      (node (ref "IC36") (pin "9") (pinfunction "GND_9") (pintype "bidirectional"))
      (node (ref "IC37") (pin "46") (pinfunction "PB8-BOOT0_46") (pintype "bidirectional"))
      (node (ref "IC37") (pin "49") (pinfunction "GND_49") (pintype "bidirectional"))
      (node (ref "IC4") (pin "1") (pinfunction "GND_1") (pintype "bidirectional"))
      (node (ref "IC4") (pin "7") (pinfunction "GND_7") (pintype "bidirectional"))
      (node (ref "IC5") (pin "1") (pinfunction "GND_1") (pintype "bidirectional"))
      (node (ref "IC5") (pin "7") (pinfunction "GND_7") (pintype "bidirectional"))
      (node (ref "IC6") (pin "1") (pinfunction "GND_1") (pintype "bidirectional"))
      (node (ref "IC6") (pin "7") (pinfunction "GND_7") (pintype "bidirectional"))
      (node (ref "IC7") (pin "21") (pinfunction "GND_21") (pintype "bidirectional"))
      (node (ref "IC8") (pin "1") (pinfunction "GND_1") (pintype "power_in"))
      (node (ref "IC9") (pin "2") (pinfunction "GND_2") (pintype "power_in"))
      (node (ref "J1") (pin "2") (pinfunction "2_2") (pintype "passive"))
      (node (ref "J2") (pin "G@1") (pinfunction "2_G@1") (pintype "passive"))
      (node (ref "J2") (pin "G@2") (pinfunction "2_G@2") (pintype "passive"))
      (node (ref "J2") (pin "G@3") (pinfunction "2_G@3") (pintype "passive"))
      (node (ref "J2") (pin "G@4") (pinfunction "2_G@4") (pintype "passive"))
      (node (ref "J3") (pin "G@1") (pinfunction "2_G@1") (pintype "passive"))
      (node (ref "J3") (pin "G@2") (pinfunction "2_G@2") (pintype "passive"))
      (node (ref "J3") (pin "G@3") (pinfunction "2_G@3") (pintype "passive"))
      (node (ref "J3") (pin "G@4") (pinfunction "2_G@4") (pintype "passive"))
      (node (ref "J4") (pin "1") (pinfunction "GND_1") (pintype "bidirectional"))
      (node (ref "J4") (pin "12") (pinfunction "GND_12") (pintype "bidirectional"))
      (node (ref "J4") (pin "M1") (pinfunction "CASE_M1") (pintype "bidirectional"))
      (node (ref "J4") (pin "M2") (pinfunction "CASE_M2") (pintype "bidirectional"))
      (node (ref "J4") (pin "M3") (pinfunction "CASE_M3") (pintype "bidirectional"))
      (node (ref "J4") (pin "M4") (pinfunction "CASE_M4") (pintype "bidirectional"))
      (node (ref "JP1") (pin "7") (pinfunction "7_7") (pintype "passive"))
      (node (ref "JP2") (pin "20") (pinfunction "20_20") (pintype "passive"))
      (node (ref "L30") (pin "2") (pinfunction "2_2") (pintype "passive"))
      (node (ref "L31") (pin "2") (pinfunction "2_2") (pintype "passive"))
      (node (ref "L38") (pin "2") (pinfunction "2_2") (pintype "passive"))
      (node (ref "L39") (pin "2") (pinfunction "2_2") (pintype "passive"))
      (node (ref "L52") (pin "2") (pinfunction "2_2") (pintype "passive"))
      (node (ref "L53") (pin "2") (pinfunction "2_2") (pintype "passive"))
      (node (ref "LP1") (pin "2") (pinfunction "GND_2") (pintype "bidirectional"))
      (node (ref "LP1") (pin "3") (pinfunction "GND_3") (pintype "bidirectional"))
      (node (ref "LP2") (pin "2") (pinfunction "GND_2") (pintype "bidirectional"))
      (node (ref "LP2") (pin "3") (pinfunction "GND_3") (pintype "bidirectional"))
      (node (ref "LP3") (pin "2") (pinfunction "GND_2") (pintype "bidirectional"))
      (node (ref "LP3") (pin "3") (pinfunction "GND_3") (pintype "bidirectional"))
      (node (ref "R10") (pin "1") (pinfunction "1_1") (pintype "passive"))
      (node (ref "R11") (pin "1") (pinfunction "1_1") (pintype "passive"))
      (node (ref "R115") (pin "2") (pinfunction "2_2") (pintype "passive"))
      (node (ref "R122") (pin "1") (pinfunction "1_1") (pintype "passive"))
      (node (ref "R131") (pin "1") (pinfunction "1_1") (pintype "passive"))
      (node (ref "R133") (pin "1") (pinfunction "1_1") (pintype "passive"))
      (node (ref "R134") (pin "2") (pinfunction "2_2") (pintype "passive"))
      (node (ref "R14") (pin "1") (pinfunction "1_1") (pintype "passive"))
      (node (ref "R169") (pin "2") (pinfunction "2_2") (pintype "passive"))
      (node (ref "R17") (pin "2") (pinfunction "2_2") (pintype "passive"))
      (node (ref "R172") (pin "2") (pinfunction "2_2") (pintype "passive"))
      (node (ref "R174") (pin "2") (pinfunction "2_2") (pintype "passive"))
      (node (ref "R175") (pin "2") (pinfunction "2_2") (pintype "passive"))
      (node (ref "R18") (pin "2") (pinfunction "2_2") (pintype "passive"))
      (node (ref "R19") (pin "2") (pinfunction "2_2") (pintype "passive"))
      (node (ref "R23") (pin "2") (pinfunction "2_2") (pintype "passive"))
      (node (ref "R25") (pin "2") (pinfunction "2_2") (pintype "passive"))
      (node (ref "R28") (pin "1") (pinfunction "1_1") (pintype "passive"))
      (node (ref "R3") (pin "1") (pinfunction "1_1") (pintype "passive"))
      (node (ref "R30") (pin "1") (pinfunction "1_1") (pintype "passive"))
      (node (ref "R31") (pin "1") (pinfunction "1_1") (pintype "passive"))
      (node (ref "R38") (pin "1") (pinfunction "1_1") (pintype "passive"))
      (node (ref "R39") (pin "2") (pinfunction "2_2") (pintype "passive"))
      (node (ref "R40") (pin "3") (pinfunction "GND_3") (pintype "bidirectional"))
      (node (ref "R47") (pin "3") (pinfunction "GND_3") (pintype "bidirectional"))
      (node (ref "R48") (pin "3") (pinfunction "GND_3") (pintype "bidirectional"))
      (node (ref "R49") (pin "3") (pinfunction "GND_3") (pintype "bidirectional"))
      (node (ref "R5") (pin "1") (pinfunction "1_1") (pintype "passive"))
      (node (ref "R50") (pin "2") (pinfunction "2_2") (pintype "passive"))
      (node (ref "R6") (pin "1") (pinfunction "1_1") (pintype "passive"))
      (node (ref "R7") (pin "2") (pinfunction "2_2") (pintype "passive"))
      (node (ref "R76") (pin "2") (pinfunction "2_2") (pintype "passive"))
      (node (ref "R9") (pin "1") (pinfunction "1_1") (pintype "passive"))
      (node (ref "T3") (pin "4") (pinfunction "OUT+_4") (pintype "bidirectional"))
      (node (ref "TP10") (pin "TP") (pinfunction "TP_TP") (pintype "input"))
      (node (ref "TP12") (pin "TP") (pinfunction "TP_TP") (pintype "input"))
      (node (ref "TP4") (pin "TP") (pinfunction "TP_TP") (pintype "input"))
      (node (ref "TP6") (pin "TP") (pinfunction "TP_TP") (pintype "input"))
      (node (ref "TP8") (pin "TP") (pinfunction "TP_TP") (pintype "input"))
      (node (ref "U1") (pin "4") (pinfunction "GND_4") (pintype "power_in"))
      (node (ref "U2") (pin "P108") (pinfunction "GND_P108") (pintype "power_in"))
      (node (ref "U2") (pin "P113") (pinfunction "GND_P113") (pintype "power_in"))
      (node (ref "U2") (pin "P13") (pinfunction "GND_P13") (pintype "power_in"))
      (node (ref "U2") (pin "P130") (pinfunction "GND_P130") (pintype "power_in"))
      (node (ref "U2") (pin "P136") (pinfunction "GND_P136") (pintype "power_in"))
      (node (ref "U2") (pin "P25") (pinfunction "GND_P25") (pintype "power_in"))
      (node (ref "U2") (pin "P3") (pinfunction "GND_P3") (pintype "power_in"))
      (node (ref "U2") (pin "P49") (pinfunction "GND_P49") (pintype "power_in"))
      (node (ref "U2") (pin "P54") (pinfunction "GND_P54") (pintype "power_in"))
      (node (ref "U2") (pin "P68") (pinfunction "GND_P68") (pintype "power_in"))
      (node (ref "U2") (pin "P73") (pinfunction "SUSPEND_P73") (pintype "input"))
      (node (ref "U2") (pin "P77") (pinfunction "GND_P77") (pintype "power_in"))
      (node (ref "U2") (pin "P91") (pinfunction "GND_P91") (pintype "power_in"))
      (node (ref "U2") (pin "P96") (pinfunction "GND_P96") (pintype "power_in"))
      (node (ref "X1") (pin "G@1") (pinfunction "2_G@1") (pintype "passive"))
      (node (ref "X1") (pin "G@2") (pinfunction "2_G@2") (pintype "passive"))
      (node (ref "X1") (pin "G@3") (pinfunction "2_G@3") (pintype "passive"))
      (node (ref "X1") (pin "G@4") (pinfunction "2_G@4") (pintype "passive"))
      (node (ref "X2") (pin "G@1") (pinfunction "2_G@1") (pintype "passive"))
      (node (ref "X2") (pin "G@2") (pinfunction "2_G@2") (pintype "passive"))
      (node (ref "X2") (pin "G@3") (pinfunction "2_G@3") (pintype "passive"))
      (node (ref "X2") (pin "G@4") (pinfunction "2_G@4") (pintype "passive"))
      (node (ref "Y1") (pin "1") (pinfunction "GND/NC_1") (pintype "power_in"))
      (node (ref "Y1") (pin "2") (pinfunction "GND_2") (pintype "power_in"))
    )
    (net (code "32") (name "HIGHBAND_SELECT") (class "Default")
      (node (ref "C245") (pin "1") (pinfunction "1_1") (pintype "passive"))
      (node (ref "R154") (pin "2") (pinfunction "2_2") (pintype "passive"))
      (node (ref "U2") (pin "P21") (pinfunction "IO_L42N_GCLK24_3_P21") (pintype "bidirectional"))
    )
    (net (code "33") (name "LO1_CE") (class "Default")
      (node (ref "IC21") (pin "4") (pinfunction "CE_4") (pintype "bidirectional"))
      (node (ref "R31") (pin "2") (pinfunction "2_2") (pintype "passive"))
      (node (ref "U2") (pin "P45") (pinfunction "IO_L49N_D4_2_P45") (pintype "bidirectional"))
    )
    (net (code "34") (name "LO1_CLK") (class "Default")
      (node (ref "IC21") (pin "1") (pinfunction "CLK_1") (pintype "input"))
      (node (ref "U2") (pin "P48") (pinfunction "IO_L48P_D7_2_P48") (pintype "bidirectional"))
    )
    (net (code "35") (name "LO1_LD") (class "Default")
      (node (ref "IC21") (pin "25") (pinfunction "LD_25") (pintype "output"))
      (node (ref "U2") (pin "P56") (pinfunction "IO_L30P_GCLK1_D13_2_P56") (pintype "bidirectional"))
    )
    (net (code "36") (name "LO1_LE") (class "Default")
      (node (ref "IC21") (pin "3") (pinfunction "LE_3") (pintype "input"))
      (node (ref "U2") (pin "P46") (pinfunction "IO_L49P_D3_2_P46") (pintype "bidirectional"))
    )
    (net (code "37") (name "LO1_MOSI") (class "Default")
      (node (ref "IC21") (pin "2") (pinfunction "DATA_2") (pintype "input"))
      (node (ref "U2") (pin "P47") (pinfunction "IO_L48N_RDWR_B_VREF_2_P47") (pintype "bidirectional"))
    )
    (net (code "38") (name "LO1_MUX") (class "Default")
      (node (ref "IC21") (pin "30") (pinfunction "MUX_30") (pintype "bidirectional"))
      (node (ref "U2") (pin "P51") (pinfunction "IO_L31P_GCLK31_D14_2_P51") (pintype "bidirectional"))
    )
    (net (code "39") (name "LO1_REF") (class "Default")
      (node (ref "C80") (pin "1") (pinfunction "1_1") (pintype "passive"))
      (node (ref "IC7") (pin "17") (pinfunction "CLK5_17") (pintype "bidirectional"))
    )
    (net (code "40") (name "LO1_RF_EN") (class "Default")
      (node (ref "IC21") (pin "26") (pinfunction "RFOUT_EN_26") (pintype "input"))
      (node (ref "U2") (pin "P55") (pinfunction "IO_L30N_GCLK0_USERCCLK_2_P55") (pintype "bidirectional"))
    )
    (net (code "41") (name "LOWBAND_SELECT") (class "Default")
      (node (ref "C247") (pin "1") (pinfunction "1_1") (pintype "passive"))
      (node (ref "R155") (pin "2") (pinfunction "2_2") (pintype "passive"))
      (node (ref "U2") (pin "P17") (pinfunction "IO_L43P_GCLK23_3_P17") (pintype "bidirectional"))
    )
    (net (code "42") (name "MCU_AUX1") (class "Default")
      (node (ref "IC37") (pin "9") (pinfunction "PA1_9") (pintype "bidirectional"))
      (node (ref "U2") (pin "P78") (pinfunction "IO_L47N_1_P78") (pintype "bidirectional"))
    )
    (net (code "43") (name "MCU_AUX2") (class "Default")
      (node (ref "IC37") (pin "10") (pinfunction "PA2_10") (pintype "bidirectional"))
      (node (ref "U2") (pin "P74") (pinfunction "IO_L74N_DOUT_BUSY_1_P74") (pintype "bidirectional"))
    )
    (net (code "44") (name "MCU_AUX3") (class "Default")
      (node (ref "IC37") (pin "11") (pinfunction "PA3_11") (pintype "bidirectional"))
      (node (ref "U2") (pin "P75") (pinfunction "IO_L74P_AWAKE_1_P75") (pintype "bidirectional"))
    )
    (net (code "45") (name "MCU_FLASH_CS") (class "Default")
      (node (ref "IC37") (pin "17") (pinfunction "PB0_17") (pintype "bidirectional"))
      (node (ref "R107") (pin "1") (pinfunction "1_1") (pintype "passive"))
    )
    (net (code "46") (name "MCU_FPGA_CCLK") (class "Default")
      (node (ref "IC37") (pin "26") (pinfunction "PB13_26") (pintype "bidirectional"))
      (node (ref "R109") (pin "1") (pinfunction "1_1") (pintype "passive"))
    )
    (net (code "47") (name "MCU_FPGA_DIN") (class "Default")
      (node (ref "IC37") (pin "28") (pinfunction "PB15_28") (pintype "bidirectional"))
      (node (ref "R110") (pin "1") (pinfunction "1_1") (pintype "passive"))
    )
    (net (code "48") (name "MCU_FPGA_NSS") (class "Default")
      (node (ref "IC37") (pin "12") (pinfunction "PA4_12") (pintype "bidirectional"))
      (node (ref "U2") (pin "P67") (pinfunction "IO_L2P_CMPCLK_2_P67") (pintype "bidirectional"))
    )
    (net (code "49") (name "MCU_FPGA_UNUSED1") (class "Default")
      (node (ref "IC37") (pin "43") (pinfunction "PB5_43") (pintype "bidirectional"))
      (node (ref "U2") (pin "P79") (pinfunction "IO_L47P_1_P79") (pintype "bidirectional"))
    )
    (net (code "50") (name "MCU_FPGA_UNUSED2") (class "Default")
      (node (ref "IC37") (pin "41") (pinfunction "PB3_41") (pintype "bidirectional"))
      (node (ref "U2") (pin "P80") (pinfunction "IO_L46N_1_P80") (pintype "bidirectional"))
    )
    (net (code "51") (name "MCU_FPGA_UNUSED3") (class "Default")
      (node (ref "IC37") (pin "40") (pinfunction "PC11_40") (pintype "bidirectional"))
      (node (ref "U2") (pin "P81") (pinfunction "IO_L46P_1_P81") (pintype "bidirectional"))
    )
    (net (code "52") (name "MCU_INTR") (class "Default")
      (node (ref "IC37") (pin "18") (pinfunction "PB1_18") (pintype "bidirectional"))
      (node (ref "U2") (pin "P59") (pinfunction "IO_L13N_D10_2_P59") (pintype "bidirectional"))
    )
    (net (code "53") (name "MCU_MISO") (class "Default")
      (node (ref "IC37") (pin "14") (pinfunction "PA6_14") (pintype "bidirectional"))
      (node (ref "R106") (pin "1") (pinfunction "1_1") (pintype "passive"))
      (node (ref "U2") (pin "P62") (pinfunction "IO_L12P_D1_MISO2_2_P62") (pintype "bidirectional"))
    )
    (net (code "54") (name "MCU_MOSI") (class "Default")
      (node (ref "IC37") (pin "15") (pinfunction "PA7_15") (pintype "bidirectional"))
      (node (ref "R105") (pin "1") (pinfunction "1_1") (pintype "passive"))
      (node (ref "U2") (pin "P61") (pinfunction "IO_L12N_D2_MISO3_2_P61") (pintype "bidirectional"))
    )
    (net (code "55") (name "MCU_SCK") (class "Default")
      (node (ref "IC37") (pin "13") (pinfunction "PA5_13") (pintype "bidirectional"))
      (node (ref "R104") (pin "1") (pinfunction "1_1") (pintype "passive"))
      (node (ref "U2") (pin "P66") (pinfunction "IO_L2N_CMPMOSI_2_P66") (pintype "bidirectional"))
    )
    (net (code "56") (name "NRST") (class "Default")
      (node (ref "IC37") (pin "7") (pinfunction "PG10-NRST_7") (pintype "bidirectional"))
      (node (ref "JP1") (pin "9") (pinfunction "9_9") (pintype "passive"))
    )
    (net (code "57") (name "Net-(C5-Pad2)") (class "Default")
      (node (ref "C5") (pin "2") (pinfunction "2_2") (pintype "passive"))
      (node (ref "R1") (pin "1") (pinfunction "1_1") (pintype "passive"))
    )
    (net (code "58") (name "Net-(C30-Pad1)") (class "Default")
      (node (ref "C30") (pin "1") (pinfunction "1_1") (pintype "passive"))
      (node (ref "X1") (pin "1") (pinfunction "1_1") (pintype "passive"))
    )
    (net (code "59") (name "Net-(C39-Pad2)") (class "Default")
      (node (ref "C39") (pin "2") (pinfunction "2_2") (pintype "passive"))
      (node (ref "X2") (pin "1") (pinfunction "1_1") (pintype "passive"))
    )
    (net (code "60") (name "Net-(C40-Pad1)") (class "Default")
      (node (ref "C40") (pin "1") (pinfunction "1_1") (pintype "passive"))
      (node (ref "R180") (pin "2") (pinfunction "2_2") (pintype "passive"))
      (node (ref "R181") (pin "1") (pinfunction "1_1") (pintype "passive"))
    )
    (net (code "61") (name "Net-(C41-Pad1)") (class "Default")
      (node (ref "C41") (pin "1") (pinfunction "1_1") (pintype "passive"))
      (node (ref "R178") (pin "1") (pinfunction "1_1") (pintype "passive"))
      (node (ref "R179") (pin "2") (pinfunction "2_2") (pintype "passive"))
    )
    (net (code "62") (name "Net-(C42-Pad1)") (class "Default")
      (node (ref "C42") (pin "1") (pinfunction "1_1") (pintype "passive"))
      (node (ref "R176") (pin "2") (pinfunction "2_2") (pintype "passive"))
      (node (ref "R177") (pin "1") (pinfunction "1_1") (pintype "passive"))
    )
    (net (code "63") (name "Net-(C43-Pad1)") (class "Default")
      (node (ref "C43") (pin "1") (pinfunction "1_1") (pintype "passive"))
      (node (ref "L14") (pin "2") (pinfunction "2_2") (pintype "passive"))
      (node (ref "L18") (pin "1") (pinfunction "1_1") (pintype "passive"))
    )
    (net (code "64") (name "Net-(C47-Pad1)") (class "Default")
      (node (ref "C47") (pin "1") (pinfunction "1_1") (pintype "passive"))
      (node (ref "L18") (pin "2") (pinfunction "2_2") (pintype "passive"))
      (node (ref "R7") (pin "1") (pinfunction "1_1") (pintype "passive"))
      (node (ref "R8") (pin "1") (pinfunction "1_1") (pintype "passive"))
    )
    (net (code "65") (name "Net-(C48-Pad2)") (class "Default")
      (node (ref "C48") (pin "2") (pinfunction "2_2") (pintype "passive"))
      (node (ref "R8") (pin "2") (pinfunction "2_2") (pintype "passive"))
      (node (ref "R9") (pin "2") (pinfunction "2_2") (pintype "passive"))
    )
    (net (code "66") (name "Net-(C53-Pad1)") (class "Default")
      (node (ref "C53") (pin "1") (pinfunction "1_1") (pintype "passive"))
      (node (ref "IC8") (pin "2") (pinfunction "VOUT_2") (pintype "power_in"))
      (node (ref "IC8") (pin "4") (pinfunction "VOUT_4") (pintype "power_in"))
      (node (ref "L19") (pin "1") (pinfunction "1_1") (pintype "passive"))
    )
    (net (code "67") (name "Net-(C62-Pad1)") (class "Default")
      (node (ref "C62") (pin "1") (pinfunction "1_1") (pintype "passive"))
      (node (ref "R14") (pin "2") (pinfunction "2_2") (pintype "passive"))
    )
    (net (code "68") (name "Net-(C66-Pad2)") (class "Default")
      (node (ref "C66") (pin "2") (pinfunction "2_2") (pintype "passive"))
      (node (ref "R16") (pin "1") (pinfunction "1_1") (pintype "passive"))
    )
    (net (code "69") (name "Net-(C74-Pad2)") (class "Default")
      (node (ref "C74") (pin "2") (pinfunction "2_2") (pintype "passive"))
      (node (ref "R26") (pin "1") (pinfunction "1_1") (pintype "passive"))
    )
    (net (code "70") (name "Net-(C82-Pad1)") (class "Default")
      (node (ref "C82") (pin "1") (pinfunction "1_1") (pintype "passive"))
      (node (ref "IC19") (pin "2") (pinfunction "VOUT_2") (pintype "power_in"))
      (node (ref "IC19") (pin "4") (pinfunction "VOUT_4") (pintype "power_in"))
      (node (ref "L28") (pin "1") (pinfunction "1_1") (pintype "passive"))
    )
    (net (code "71") (name "Net-(C92-Pad2)") (class "Default")
      (node (ref "C92") (pin "2") (pinfunction "2_2") (pintype "passive"))
      (node (ref "R37") (pin "1") (pinfunction "1_1") (pintype "passive"))
    )
    (net (code "72") (name "Net-(C93-Pad1)") (class "Default")
      (node (ref "C93") (pin "1") (pinfunction "1_1") (pintype "passive"))
      (node (ref "R38") (pin "2") (pinfunction "2_2") (pintype "passive"))
    )
    (net (code "73") (name "Net-(C99-Pad1)") (class "Default")
      (node (ref "C99") (pin "1") (pinfunction "1_1") (pintype "passive"))
      (node (ref "J2") (pin "1") (pinfunction "1_1") (pintype "passive"))
    )
    (net (code "74") (name "Net-(C114-Pad1)") (class "Default")
      (node (ref "C114") (pin "1") (pinfunction "1_1") (pintype "passive"))
      (node (ref "R168") (pin "1") (pinfunction "1_1") (pintype "passive"))
      (node (ref "R169") (pin "1") (pinfunction "1_1") (pintype "passive"))
    )
    (net (code "75") (name "Net-(C119-Pad1)") (class "Default")
      (node (ref "C119") (pin "1") (pinfunction "1_1") (pintype "passive"))
      (node (ref "C122") (pin "1") (pinfunction "1_1") (pintype "passive"))
      (node (ref "L16") (pin "1") (pinfunction "1_1") (pintype "passive"))
      (node (ref "L32") (pin "1") (pinfunction "1_1") (pintype "passive"))
      (node (ref "L33") (pin "1") (pinfunction "1_1") (pintype "passive"))
    )
    (net (code "76") (name "Net-(C120-Pad2)") (class "Default")
      (node (ref "C120") (pin "2") (pinfunction "2_2") (pintype "passive"))
      (node (ref "C124") (pin "1") (pinfunction "1_1") (pintype "passive"))
      (node (ref "L34") (pin "1") (pinfunction "1_1") (pintype "passive"))
    )
    (net (code "77") (name "Net-(C121-Pad1)") (class "Default")
      (node (ref "C121") (pin "1") (pinfunction "1_1") (pintype "passive"))
      (node (ref "R58") (pin "1") (pinfunction "1_1") (pintype "passive"))
      (node (ref "R61") (pin "2") (pinfunction "2_2") (pintype "passive"))
    )
    (net (code "78") (name "Net-(C121-Pad2)") (class "Default")
      (node (ref "C121") (pin "2") (pinfunction "2_2") (pintype "passive"))
      (node (ref "R59") (pin "1") (pinfunction "1_1") (pintype "passive"))
      (node (ref "R62") (pin "2") (pinfunction "2_2") (pintype "passive"))
    )
    (net (code "79") (name "Net-(C123-Pad2)") (class "Default")
      (node (ref "C123") (pin "2") (pinfunction "2_2") (pintype "passive"))
      (node (ref "C124") (pin "2") (pinfunction "2_2") (pintype "passive"))
      (node (ref "L35") (pin "1") (pinfunction "1_1") (pintype "passive"))
    )
    (net (code "80") (name "Net-(C128-Pad1)") (class "Default")
      (node (ref "C128") (pin "1") (pinfunction "1_1") (pintype "passive"))
      (node (ref "L34") (pin "2") (pinfunction "2_2") (pintype "passive"))
      (node (ref "L36") (pin "1") (pinfunction "1_1") (pintype "passive"))
    )
    (net (code "81") (name "Net-(C128-Pad2)") (class "Default")
      (node (ref "C128") (pin "2") (pinfunction "2_2") (pintype "passive"))
      (node (ref "L35") (pin "2") (pinfunction "2_2") (pintype "passive"))
      (node (ref "L37") (pin "1") (pinfunction "1_1") (pintype "passive"))
    )
    (net (code "82") (name "Net-(C130-Pad1)") (class "Default")
      (node (ref "C130") (pin "1") (pinfunction "1_1") (pintype "passive"))
      (node (ref "L36") (pin "2") (pinfunction "2_2") (pintype "passive"))
      (node (ref "R63") (pin "2") (pinfunction "2_2") (pintype "passive"))
      (node (ref "R64") (pin "2") (pinfunction "2_2") (pintype "passive"))
    )
    (net (code "83") (name "Net-(C130-Pad2)") (class "Default")
      (node (ref "C130") (pin "2") (pinfunction "2_2") (pintype "passive"))
      (node (ref "L37") (pin "2") (pinfunction "2_2") (pintype "passive"))
      (node (ref "R63") (pin "1") (pinfunction "1_1") (pintype "passive"))
      (node (ref "R65") (pin "2") (pinfunction "2_2") (pintype "passive"))
    )
    (net (code "84") (name "Net-(C136-Pad1)") (class "Default")
      (node (ref "C136") (pin "1") (pinfunction "1_1") (pintype "passive"))
      (node (ref "J3") (pin "1") (pinfunction "1_1") (pintype "passive"))
    )
    (net (code "85") (name "Net-(C156-Pad1)") (class "Default")
      (node (ref "C156") (pin "1") (pinfunction "1_1") (pintype "passive"))
      (node (ref "C159") (pin "1") (pinfunction "1_1") (pintype "passive"))
      (node (ref "L40") (pin "1") (pinfunction "1_1") (pintype "passive"))
      (node (ref "L41") (pin "1") (pinfunction "1_1") (pintype "passive"))
      (node (ref "L55") (pin "1") (pinfunction "1_1") (pintype "passive"))
    )
    (net (code "86") (name "Net-(C157-Pad2)") (class "Default")
      (node (ref "C157") (pin "2") (pinfunction "2_2") (pintype "passive"))
      (node (ref "C161") (pin "1") (pinfunction "1_1") (pintype "passive"))
      (node (ref "L42") (pin "1") (pinfunction "1_1") (pintype "passive"))
    )
    (net (code "87") (name "Net-(C158-Pad1)") (class "Default")
      (node (ref "C158") (pin "1") (pinfunction "1_1") (pintype "passive"))
      (node (ref "R85") (pin "1") (pinfunction "1_1") (pintype "passive"))
      (node (ref "R88") (pin "2") (pinfunction "2_2") (pintype "passive"))
    )
    (net (code "88") (name "Net-(C158-Pad2)") (class "Default")
      (node (ref "C158") (pin "2") (pinfunction "2_2") (pintype "passive"))
      (node (ref "R86") (pin "1") (pinfunction "1_1") (pintype "passive"))
      (node (ref "R89") (pin "2") (pinfunction "2_2") (pintype "passive"))
    )
    (net (code "89") (name "Net-(C160-Pad2)") (class "Default")
      (node (ref "C160") (pin "2") (pinfunction "2_2") (pintype "passive"))
      (node (ref "C161") (pin "2") (pinfunction "2_2") (pintype "passive"))
      (node (ref "L43") (pin "1") (pinfunction "1_1") (pintype "passive"))
    )
    (net (code "90") (name "Net-(C165-Pad1)") (class "Default")
      (node (ref "C165") (pin "1") (pinfunction "1_1") (pintype "passive"))
      (node (ref "L42") (pin "2") (pinfunction "2_2") (pintype "passive"))
      (node (ref "L44") (pin "1") (pinfunction "1_1") (pintype "passive"))
    )
    (net (code "91") (name "Net-(C165-Pad2)") (class "Default")
      (node (ref "C165") (pin "2") (pinfunction "2_2") (pintype "passive"))
      (node (ref "L43") (pin "2") (pinfunction "2_2") (pintype "passive"))
      (node (ref "L45") (pin "1") (pinfunction "1_1") (pintype "passive"))
    )
    (net (code "92") (name "Net-(C167-Pad1)") (class "Default")
      (node (ref "C167") (pin "1") (pinfunction "1_1") (pintype "passive"))
      (node (ref "L44") (pin "2") (pinfunction "2_2") (pintype "passive"))
      (node (ref "R90") (pin "2") (pinfunction "2_2") (pintype "passive"))
      (node (ref "R91") (pin "2") (pinfunction "2_2") (pintype "passive"))
    )
    (net (code "93") (name "Net-(C167-Pad2)") (class "Default")
      (node (ref "C167") (pin "2") (pinfunction "2_2") (pintype "passive"))
      (node (ref "L45") (pin "2") (pinfunction "2_2") (pintype "passive"))
      (node (ref "R90") (pin "1") (pinfunction "1_1") (pintype "passive"))
      (node (ref "R92") (pin "2") (pinfunction "2_2") (pintype "passive"))
    )
    (net (code "94") (name "Net-(C183-Pad1)") (class "Default")
      (node (ref "C183") (pin "1") (pinfunction "1_1") (pintype "passive"))
      (node (ref "R173") (pin "1") (pinfunction "1_1") (pintype "passive"))
      (node (ref "R174") (pin "1") (pinfunction "1_1") (pintype "passive"))
    )
    (net (code "95") (name "Net-(C184-Pad1)") (class "Default")
      (node (ref "C184") (pin "1") (pinfunction "1_1") (pintype "passive"))
      (node (ref "R96") (pin "1") (pinfunction "1_1") (pintype "passive"))
      (node (ref "R98") (pin "2") (pinfunction "2_2") (pintype "passive"))
    )
    (net (code "96") (name "Net-(C184-Pad2)") (class "Default")
      (node (ref "C184") (pin "2") (pinfunction "2_2") (pintype "passive"))
      (node (ref "R97") (pin "1") (pinfunction "1_1") (pintype "passive"))
      (node (ref "R99") (pin "2") (pinfunction "2_2") (pintype "passive"))
    )
    (net (code "97") (name "Net-(C190-Pad1)") (class "Default")
      (node (ref "C190") (pin "1") (pinfunction "1_1") (pintype "passive"))
      (node (ref "C193") (pin "1") (pinfunction "1_1") (pintype "passive"))
      (node (ref "L46") (pin "1") (pinfunction "1_1") (pintype "passive"))
      (node (ref "L47") (pin "1") (pinfunction "1_1") (pintype "passive"))
      (node (ref "L60") (pin "1") (pinfunction "1_1") (pintype "passive"))
    )
    (net (code "98") (name "Net-(C191-Pad2)") (class "Default")
      (node (ref "C191") (pin "2") (pinfunction "2_2") (pintype "passive"))
      (node (ref "C194") (pin "1") (pinfunction "1_1") (pintype "passive"))
      (node (ref "L48") (pin "1") (pinfunction "1_1") (pintype "passive"))
    )
    (net (code "99") (name "Net-(C192-Pad2)") (class "Default")
      (node (ref "C192") (pin "2") (pinfunction "2_2") (pintype "passive"))
      (node (ref "C194") (pin "2") (pinfunction "2_2") (pintype "passive"))
      (node (ref "L49") (pin "1") (pinfunction "1_1") (pintype "passive"))
    )
    (net (code "100") (name "Net-(C196-Pad1)") (class "Default")
      (node (ref "C196") (pin "1") (pinfunction "1_1") (pintype "passive"))
      (node (ref "L48") (pin "2") (pinfunction "2_2") (pintype "passive"))
      (node (ref "L50") (pin "1") (pinfunction "1_1") (pintype "passive"))
    )
    (net (code "101") (name "Net-(C196-Pad2)") (class "Default")
      (node (ref "C196") (pin "2") (pinfunction "2_2") (pintype "passive"))
      (node (ref "L49") (pin "2") (pinfunction "2_2") (pintype "passive"))
      (node (ref "L51") (pin "1") (pinfunction "1_1") (pintype "passive"))
    )
    (net (code "102") (name "Net-(C269-Pad2)") (class "Default")
      (node (ref "C269") (pin "2") (pinfunction "2_2") (pintype "passive"))
      (node (ref "R168") (pin "2") (pinfunction "2_2") (pintype "passive"))
      (node (ref "R172") (pin "1") (pinfunction "1_1") (pintype "passive"))
    )
    (net (code "103") (name "Net-(C270-Pad2)") (class "Default")
      (node (ref "C270") (pin "2") (pinfunction "2_2") (pintype "passive"))
      (node (ref "R173") (pin "2") (pinfunction "2_2") (pintype "passive"))
      (node (ref "R175") (pin "1") (pinfunction "1_1") (pintype "passive"))
    )
    (net (code "104") (name "Net-(IC1-COMP)") (class "Default")
      (node (ref "IC1") (pin "12") (pinfunction "COMP_12") (pintype "bidirectional"))
      (node (ref "R1") (pin "2") (pinfunction "2_2") (pintype "passive"))
    )
    (net (code "105") (name "Net-(IC1-FB)") (class "Default")
      (node (ref "C9") (pin "2") (pinfunction "2_2") (pintype "passive"))
      (node (ref "IC1") (pin "3") (pinfunction "FB_3") (pintype "bidirectional"))
      (node (ref "R4") (pin "1") (pinfunction "1_1") (pintype "passive"))
      (node (ref "R5") (pin "2") (pinfunction "2_2") (pintype "passive"))
    )
    (net (code "106") (name "Net-(IC1-OVP)") (class "Default")
      (node (ref "IC1") (pin "9") (pinfunction "OVP_9") (pintype "bidirectional"))
      (node (ref "R2") (pin "1") (pinfunction "1_1") (pintype "passive"))
      (node (ref "R3") (pin "2") (pinfunction "2_2") (pintype "passive"))
    )
    (net (code "107") (name "Net-(IC1-SS)") (class "Default")
      (node (ref "C4") (pin "2") (pinfunction "2_2") (pintype "passive"))
      (node (ref "IC1") (pin "2") (pinfunction "SS_2") (pintype "bidirectional"))
    )
    (net (code "108") (name "Net-(IC2A-SW)") (class "Default")
      (node (ref "IC2") (pin "7") (pinfunction "SW_7") (pintype "bidirectional"))
      (node (ref "L2") (pin "P$1") (pinfunction "1_P$1") (pintype "passive"))
    )
    (net (code "109") (name "Net-(IC2B-FB)") (class "Default")
      (node (ref "C11") (pin "1") (pinfunction "1_1") (pintype "passive"))
      (node (ref "C8") (pin "1") (pinfunction "1_1") (pintype "passive"))
      (node (ref "IC2") (pin "16") (pinfunction "FB_16") (pintype "bidirectional"))
      (node (ref "L3") (pin "P$2") (pinfunction "2_P$2") (pintype "passive"))
      (node (ref "L4") (pin "P$1") (pinfunction "1_P$1") (pintype "passive"))
    )
    (net (code "110") (name "Net-(IC2B-SW)") (class "Default")
      (node (ref "IC2") (pin "2") (pinfunction "SW_2") (pintype "bidirectional"))
      (node (ref "L3") (pin "P$1") (pinfunction "1_P$1") (pintype "passive"))
    )
    (net (code "111") (name "Net-(IC3-SENSE)") (class "Default")
      (node (ref "C22") (pin "2") (pinfunction "2_2") (pintype "passive"))
      (node (ref "IC3") (pin "2") (pinfunction "SENSE_2") (pintype "bidirectional"))
      (node (ref "IC3") (pin "3") (pinfunction "VOUT_3") (pintype "bidirectional"))
      (node (ref "L6") (pin "1") (pinfunction "1_1") (pintype "passive"))
    )
    (net (code "112") (name "Net-(IC4-SENSE)") (class "Default")
      (node (ref "C23") (pin "2") (pinfunction "2_2") (pintype "passive"))
      (node (ref "IC4") (pin "2") (pinfunction "SENSE_2") (pintype "bidirectional"))
      (node (ref "IC4") (pin "3") (pinfunction "VOUT_3") (pintype "bidirectional"))
      (node (ref "L7") (pin "1") (pinfunction "1_1") (pintype "passive"))
    )
    (net (code "113") (name "Net-(IC5-SENSE)") (class "Default")
      (node (ref "C24") (pin "2") (pinfunction "2_2") (pintype "passive"))
      (node (ref "IC5") (pin "2") (pinfunction "SENSE_2") (pintype "bidirectional"))
      (node (ref "IC5") (pin "3") (pinfunction "VOUT_3") (pintype "bidirectional"))
      (node (ref "L8") (pin "1") (pinfunction "1_1") (pintype "passive"))
    )
    (net (code "114") (name "Net-(IC6-SENSE)") (class "Default")
      (node (ref "C25") (pin "2") (pinfunction "2_2") (pintype "passive"))
      (node (ref "IC6") (pin "2") (pinfunction "SENSE_2") (pintype "bidirectional"))
      (node (ref "IC6") (pin "3") (pinfunction "VOUT_3") (pintype "bidirectional"))
      (node (ref "L9") (pin "1") (pinfunction "1_1") (pintype "passive"))
    )
    (net (code "115") (name "Net-(IC7-CLK0)") (class "Default")
      (node (ref "C38") (pin "1") (pinfunction "1_1") (pintype "passive"))
      (node (ref "IC7") (pin "13") (pinfunction "CLK0_13") (pintype "bidirectional"))
      (node (ref "L14") (pin "1") (pinfunction "1_1") (pintype "passive"))
    )
    (net (code "116") (name "Net-(IC7-CLK1)") (class "Default")
      (node (ref "C36") (pin "1") (pinfunction "1_1") (pintype "passive"))
      (node (ref "IC7") (pin "12") (pinfunction "CLK1_12") (pintype "bidirectional"))
      (node (ref "R179") (pin "1") (pinfunction "1_1") (pintype "passive"))
    )
    (net (code "117") (name "Net-(IC7-CLK2)") (class "Default")
      (node (ref "C37") (pin "1") (pinfunction "1_1") (pintype "passive"))
      (node (ref "IC7") (pin "9") (pinfunction "CLK2_9") (pintype "bidirectional"))
      (node (ref "R176") (pin "1") (pinfunction "1_1") (pintype "passive"))
    )
    (net (code "118") (name "Net-(IC7-CLK4)") (class "Default")
      (node (ref "C35") (pin "1") (pinfunction "1_1") (pintype "passive"))
      (node (ref "IC7") (pin "19") (pinfunction "CLK4_19") (pintype "bidirectional"))
      (node (ref "R180") (pin "1") (pinfunction "1_1") (pintype "passive"))
    )
    (net (code "119") (name "Net-(IC7-CLK6)") (class "Default")
      (node (ref "C39") (pin "1") (pinfunction "1_1") (pintype "passive"))
      (node (ref "IC7") (pin "16") (pinfunction "CLK6_16") (pintype "bidirectional"))
    )
    (net (code "120") (name "Net-(IC7-CLKIN)") (class "Default")
      (node (ref "C30") (pin "2") (pinfunction "2_2") (pintype "passive"))
      (node (ref "IC7") (pin "6") (pinfunction "CLKIN_6") (pintype "bidirectional"))
    )
    (net (code "121") (name "Net-(IC7-OEB)") (class "Default")
      (node (ref "IC7") (pin "7") (pinfunction "OEB_7") (pintype "bidirectional"))
      (node (ref "R6") (pin "2") (pinfunction "2_2") (pintype "passive"))
    )
    (net (code "122") (name "Net-(IC7-VDDOA)") (class "Default")
      (node (ref "C32") (pin "2") (pinfunction "2_2") (pintype "passive"))
      (node (ref "C33") (pin "2") (pinfunction "2_2") (pintype "passive"))
      (node (ref "IC7") (pin "10") (pinfunction "VDDOB_10") (pintype "bidirectional"))
      (node (ref "IC7") (pin "11") (pinfunction "VDDOA_11") (pintype "bidirectional"))
      (node (ref "IC7") (pin "14") (pinfunction "VDDOD_14") (pintype "bidirectional"))
      (node (ref "IC7") (pin "18") (pinfunction "VDDOC_18") (pintype "bidirectional"))
      (node (ref "L10") (pin "2") (pinfunction "2_2") (pintype "passive"))
    )
    (net (code "123") (name "Net-(IC7-XA)") (class "Default")
      (node (ref "C34") (pin "1") (pinfunction "1_1") (pintype "passive"))
      (node (ref "IC7") (pin "1") (pinfunction "XA_1") (pintype "bidirectional"))
    )
    (net (code "124") (name "Net-(IC9-VOUT)") (class "Default")
      (node (ref "C52") (pin "1") (pinfunction "1_1") (pintype "passive"))
      (node (ref "IC9") (pin "5") (pinfunction "VOUT_5") (pintype "power_in"))
      (node (ref "L20") (pin "1") (pinfunction "1_1") (pintype "passive"))
    )
    (net (code "125") (name "Net-(IC10-BIAS_FILT)") (class "Default")
      (node (ref "C60") (pin "1") (pinfunction "1_1") (pintype "passive"))
      (node (ref "IC10") (pin "23") (pinfunction "BIAS_FILT_23") (pintype "bidirectional"))
    )
    (net (code "126") (name "Net-(IC10-CE)") (class "Default")
      (node (ref "C268") (pin "1") (pinfunction "1_1") (pintype "passive"))
      (node (ref "IC10") (pin "4") (pinfunction "CE_4") (pintype "bidirectional"))
      (node (ref "R163") (pin "1") (pinfunction "1_1") (pintype "passive"))
    )
    (net (code "127") (name "Net-(IC10-CLK)") (class "Default")
      (node (ref "IC10") (pin "1") (pinfunction "CLK_1") (pintype "input"))
      (node (ref "R164") (pin "1") (pinfunction "1_1") (pintype "passive"))
    )
    (net (code "128") (name "Net-(IC10-CP_OUT)") (class "Default")
      (node (ref "C63") (pin "1") (pinfunction "1_1") (pintype "passive"))
      (node (ref "C66") (pin "1") (pinfunction "1_1") (pintype "passive"))
      (node (ref "IC10") (pin "7") (pinfunction "CP_OUT_7") (pintype "bidirectional"))
      (node (ref "R15") (pin "1") (pinfunction "1_1") (pintype "passive"))
    )
    (net (code "129") (name "Net-(IC10-DATA)") (class "Default")
      (node (ref "IC10") (pin "2") (pinfunction "DATA_2") (pintype "input"))
      (node (ref "R170") (pin "1") (pinfunction "1_1") (pintype "passive"))
    )
    (net (code "130") (name "Net-(IC10-LD)") (class "Default")
      (node (ref "C274") (pin "1") (pinfunction "1_1") (pintype "passive"))
      (node (ref "IC10") (pin "25") (pinfunction "LD_25") (pintype "output"))
      (node (ref "R166") (pin "1") (pinfunction "1_1") (pintype "passive"))
    )
    (net (code "131") (name "Net-(IC10-LE)") (class "Default")
      (node (ref "IC10") (pin "3") (pinfunction "LE_3") (pintype "input"))
      (node (ref "R171") (pin "1") (pinfunction "1_1") (pintype "passive"))
    )
    (net (code "132") (name "Net-(IC10-MUX)") (class "Default")
      (node (ref "IC10") (pin "30") (pinfunction "MUX_30") (pintype "bidirectional"))
      (node (ref "R167") (pin "1") (pinfunction "1_1") (pintype "passive"))
    )
    (net (code "133") (name "Net-(IC10-NOISE_FILT)") (class "Default")
      (node (ref "C59") (pin "1") (pinfunction "1_1") (pintype "passive"))
      (node (ref "IC10") (pin "19") (pinfunction "NOISE_FILT_19") (pintype "bidirectional"))
    )
    (net (code "134") (name "Net-(IC10-REF_IN)") (class "Default")
      (node (ref "C51") (pin "2") (pinfunction "2_2") (pintype "passive"))
      (node (ref "IC10") (pin "29") (pinfunction "REF_IN_29") (pintype "input"))
    )
    (net (code "135") (name "Net-(IC10-REG)") (class "Default")
      (node (ref "C58") (pin "1") (pinfunction "1_1") (pintype "passive"))
      (node (ref "IC10") (pin "24") (pinfunction "REG_24") (pintype "bidirectional"))
    )
    (net (code "136") (name "Net-(IC10-RFOUTA_N)") (class "Default")
      (node (ref "C62") (pin "2") (pinfunction "2_2") (pintype "passive"))
      (node (ref "IC10") (pin "13") (pinfunction "RFOUTA_N_13") (pintype "bidirectional"))
      (node (ref "R13") (pin "1") (pinfunction "1_1") (pintype "passive"))
    )
    (net (code "137") (name "Net-(IC10-RFOUTA_P)") (class "Default")
      (node (ref "C65") (pin "1") (pinfunction "1_1") (pintype "passive"))
      (node (ref "IC10") (pin "12") (pinfunction "RFOUTA_P_12") (pintype "bidirectional"))
      (node (ref "R12") (pin "1") (pinfunction "1_1") (pintype "passive"))
    )
    (net (code "138") (name "Net-(IC10-RFOUT_EN)") (class "Default")
      (node (ref "C272") (pin "1") (pinfunction "1_1") (pintype "passive"))
      (node (ref "IC10") (pin "26") (pinfunction "RFOUT_EN_26") (pintype "input"))
      (node (ref "R165") (pin "1") (pinfunction "1_1") (pintype "passive"))
    )
    (net (code "139") (name "Net-(IC10-RSET)") (class "Default")
      (node (ref "IC10") (pin "22") (pinfunction "RSET_22") (pintype "bidirectional"))
      (node (ref "R10") (pin "2") (pinfunction "2_2") (pintype "passive"))
    )
    (net (code "140") (name "Net-(IC10-SW)") (class "Default")
      (node (ref "IC10") (pin "5") (pinfunction "SW_5") (pintype "bidirectional"))
      (node (ref "R16") (pin "2") (pinfunction "2_2") (pintype "passive"))
      (node (ref "R17") (pin "1") (pinfunction "1_1") (pintype "passive"))
    )
    (net (code "141") (name "Net-(IC10-TUNE)") (class "Default")
      (node (ref "C67") (pin "2") (pinfunction "2_2") (pintype "passive"))
      (node (ref "IC10") (pin "20") (pinfunction "TUNE_20") (pintype "bidirectional"))
      (node (ref "R15") (pin "2") (pinfunction "2_2") (pintype "passive"))
    )
    (net (code "142") (name "Net-(IC10-VCC_DIG)") (class "Default")
      (node (ref "C54") (pin "1") (pinfunction "1_1") (pintype "passive"))
      (node (ref "C55") (pin "1") (pinfunction "1_1") (pintype "passive"))
      (node (ref "IC10") (pin "28") (pinfunction "VCC_DIG_28") (pintype "bidirectional"))
      (node (ref "IC10") (pin "32") (pinfunction "VDD_SD_32") (pintype "bidirectional"))
      (node (ref "L64") (pin "1") (pinfunction "1_1") (pintype "passive"))
    )
    (net (code "143") (name "Net-(IC10-VCC_RF)") (class "Default")
      (node (ref "C56") (pin "1") (pinfunction "1_1") (pintype "passive"))
      (node (ref "C61") (pin "1") (pinfunction "1_1") (pintype "passive"))
      (node (ref "C64") (pin "1") (pinfunction "1_1") (pintype "passive"))
      (node (ref "IC10") (pin "16") (pinfunction "VCC_RF_16") (pintype "bidirectional"))
      (node (ref "IC10") (pin "17") (pinfunction "VCC_VCO_17") (pintype "bidirectional"))
      (node (ref "L19") (pin "2") (pinfunction "2_2") (pintype "passive"))
      (node (ref "R12") (pin "2") (pinfunction "2_2") (pintype "passive"))
      (node (ref "R13") (pin "2") (pinfunction "2_2") (pintype "passive"))
      (node (ref "TP14") (pin "TP") (pinfunction "TP_TP") (pintype "input"))
    )
    (net (code "144") (name "Net-(IC11-ANT)") (class "Default")
      (node (ref "C65") (pin "2") (pinfunction "2_2") (pintype "passive"))
      (node (ref "IC11") (pin "7") (pinfunction "ANT_7") (pintype "bidirectional"))
    )
    (net (code "145") (name "Net-(IC11-C1)") (class "Default")
      (node (ref "IC11") (pin "2") (pinfunction "C1_2") (pintype "bidirectional"))
      (node (ref "R18") (pin "1") (pinfunction "1_1") (pintype "passive"))
      (node (ref "R21") (pin "1") (pinfunction "1_1") (pintype "passive"))
    )
    (net (code "146") (name "Net-(IC11-C2)") (class "Default")
      (node (ref "IC11") (pin "1") (pinfunction "C2_1") (pintype "bidirectional"))
      (node (ref "R19") (pin "1") (pinfunction "1_1") (pintype "passive"))
      (node (ref "R20") (pin "1") (pinfunction "1_1") (pintype "passive"))
    )
    (net (code "147") (name "Net-(IC11-RF1)") (class "Default")
      (node (ref "IC11") (pin "9") (pinfunction "RF1_9") (pintype "bidirectional"))
      (node (ref "IC12") (pin "6") (pinfunction "RF3_6") (pintype "bidirectional"))
    )
    (net (code "148") (name "Net-(IC11-RF2)") (class "Default")
      (node (ref "IC11") (pin "11") (pinfunction "RF2_11") (pintype "bidirectional"))
      (node (ref "LP1") (pin "4") (pinfunction "IN_4") (pintype "bidirectional"))
    )
    (net (code "149") (name "Net-(IC11-RF3)") (class "Default")
      (node (ref "IC11") (pin "6") (pinfunction "RF3_6") (pintype "bidirectional"))
      (node (ref "LP3") (pin "4") (pinfunction "IN_4") (pintype "bidirectional"))
    )
    (net (code "150") (name "Net-(IC11-RF4)") (class "Default")
      (node (ref "IC11") (pin "4") (pinfunction "RF4_4") (pintype "bidirectional"))
      (node (ref "LP2") (pin "4") (pinfunction "IN_4") (pintype "bidirectional"))
    )
    (net (code "151") (name "Net-(IC12-ANT)") (class "Default")
      (node (ref "C68") (pin "1") (pinfunction "1_1") (pintype "passive"))
      (node (ref "IC12") (pin "7") (pinfunction "ANT_7") (pintype "bidirectional"))
    )
    (net (code "152") (name "Net-(IC12-C1)") (class "Default")
      (node (ref "IC12") (pin "2") (pinfunction "C1_2") (pintype "bidirectional"))
      (node (ref "R24") (pin "1") (pinfunction "1_1") (pintype "passive"))
      (node (ref "R25") (pin "1") (pinfunction "1_1") (pintype "passive"))
    )
    (net (code "153") (name "Net-(IC12-C2)") (class "Default")
      (node (ref "IC12") (pin "1") (pinfunction "C2_1") (pintype "bidirectional"))
      (node (ref "R22") (pin "1") (pinfunction "1_1") (pintype "passive"))
      (node (ref "R23") (pin "1") (pinfunction "1_1") (pintype "passive"))
    )
    (net (code "154") (name "Net-(IC12-RF1)") (class "Default")
      (node (ref "IC12") (pin "9") (pinfunction "RF1_9") (pintype "bidirectional"))
      (node (ref "LP3") (pin "1") (pinfunction "OUT_1") (pintype "bidirectional"))
    )
    (net (code "155") (name "Net-(IC12-RF2)") (class "Default")
      (node (ref "IC12") (pin "11") (pinfunction "RF2_11") (pintype "bidirectional"))
      (node (ref "LP2") (pin "1") (pinfunction "OUT_1") (pintype "bidirectional"))
    )
    (net (code "156") (name "Net-(IC12-RF4)") (class "Default")
      (node (ref "IC12") (pin "4") (pinfunction "RF4_4") (pintype "bidirectional"))
      (node (ref "LP1") (pin "1") (pinfunction "OUT_1") (pintype "bidirectional"))
    )
    (net (code "157") (name "Net-(IC13-CTL1)") (class "Default")
      (node (ref "C246") (pin "1") (pinfunction "1_1") (pintype "passive"))
      (node (ref "IC13") (pin "17") (pinfunction "CTL1_17") (pintype "bidirectional"))
      (node (ref "R154") (pin "1") (pinfunction "1_1") (pintype "passive"))
    )
    (net (code "158") (name "Net-(IC13-CTL2)") (class "Default")
      (node (ref "C248") (pin "1") (pinfunction "1_1") (pintype "passive"))
      (node (ref "IC13") (pin "16") (pinfunction "CTL2_16") (pintype "bidirectional"))
      (node (ref "R155") (pin "1") (pinfunction "1_1") (pintype "passive"))
    )
    (net (code "159") (name "Net-(IC13-RF_COM)") (class "Default")
      (node (ref "IC13") (pin "8") (pinfunction "RF_COM_8") (pintype "bidirectional"))
      (node (ref "IC14") (pin "5") (pinfunction "RF1_5") (pintype "bidirectional"))
    )
    (net (code "160") (name "Net-(IC13-VCC)") (class "Default")
      (node (ref "C69") (pin "1") (pinfunction "1_1") (pintype "passive"))
      (node (ref "IC13") (pin "20") (pinfunction "VCC_20") (pintype "bidirectional"))
      (node (ref "L21") (pin "2") (pinfunction "2_2") (pintype "passive"))
    )
    (net (code "161") (name "Net-(IC14-D0)") (class "Default")
      (node (ref "C250") (pin "1") (pinfunction "1_1") (pintype "passive"))
      (node (ref "IC14") (pin "1") (pinfunction "D0_1") (pintype "bidirectional"))
      (node (ref "R156") (pin "1") (pinfunction "1_1") (pintype "passive"))
    )
    (net (code "162") (name "Net-(IC14-D1)") (class "Default")
      (node (ref "C252") (pin "1") (pinfunction "1_1") (pintype "passive"))
      (node (ref "IC14") (pin "24") (pinfunction "D1_24") (pintype "bidirectional"))
      (node (ref "R157") (pin "1") (pinfunction "1_1") (pintype "passive"))
    )
    (net (code "163") (name "Net-(IC14-D2)") (class "Default")
      (node (ref "C254") (pin "1") (pinfunction "1_1") (pintype "passive"))
      (node (ref "IC14") (pin "23") (pinfunction "D2_23") (pintype "bidirectional"))
      (node (ref "R158") (pin "1") (pinfunction "1_1") (pintype "passive"))
    )
    (net (code "164") (name "Net-(IC14-D3)") (class "Default")
      (node (ref "C256") (pin "1") (pinfunction "1_1") (pintype "passive"))
      (node (ref "IC14") (pin "22") (pinfunction "D3_22") (pintype "bidirectional"))
      (node (ref "R159") (pin "1") (pinfunction "1_1") (pintype "passive"))
    )
    (net (code "165") (name "Net-(IC14-D4)") (class "Default")
      (node (ref "C261") (pin "1") (pinfunction "1_1") (pintype "passive"))
      (node (ref "IC14") (pin "21") (pinfunction "D4_21") (pintype "bidirectional"))
      (node (ref "R162") (pin "2") (pinfunction "2_2") (pintype "passive"))
    )
    (net (code "166") (name "Net-(IC14-D5)") (class "Default")
      (node (ref "C259") (pin "1") (pinfunction "1_1") (pintype "passive"))
      (node (ref "IC14") (pin "20") (pinfunction "D5_20") (pintype "bidirectional"))
      (node (ref "R161") (pin "2") (pinfunction "2_2") (pintype "passive"))
    )
    (net (code "167") (name "Net-(IC14-D6)") (class "Default")
      (node (ref "C257") (pin "1") (pinfunction "1_1") (pintype "passive"))
      (node (ref "IC14") (pin "19") (pinfunction "D6_19") (pintype "bidirectional"))
      (node (ref "R160") (pin "2") (pinfunction "2_2") (pintype "passive"))
    )
    (net (code "168") (name "Net-(IC14-LE)") (class "Default")
      (node (ref "C70") (pin "1") (pinfunction "1_1") (pintype "passive"))
      (node (ref "IC14") (pin "16") (pinfunction "LE_16") (pintype "bidirectional"))
      (node (ref "IC14") (pin "2") (pinfunction "VDD_2") (pintype "bidirectional"))
      (node (ref "L22") (pin "2") (pinfunction "2_2") (pintype "passive"))
    )
    (net (code "169") (name "Net-(IC14-RF2)") (class "Default")
      (node (ref "C71") (pin "1") (pinfunction "1_1") (pintype "passive"))
      (node (ref "IC14") (pin "14") (pinfunction "RF2_14") (pintype "bidirectional"))
    )
    (net (code "170") (name "Net-(IC15-PWDN)") (class "Default")
      (node (ref "C244") (pin "1") (pinfunction "1_1") (pintype "passive"))
      (node (ref "IC15") (pin "5") (pinfunction "PWDN_5") (pintype "bidirectional"))
      (node (ref "R153") (pin "1") (pinfunction "1_1") (pintype "passive"))
    )
    (net (code "171") (name "Net-(IC15-RFIN)") (class "Default")
      (node (ref "C71") (pin "2") (pinfunction "2_2") (pintype "passive"))
      (node (ref "IC15") (pin "2") (pinfunction "RFIN_2") (pintype "bidirectional"))
    )
    (net (code "172") (name "Net-(IC15-RFOUT)") (class "Default")
      (node (ref "C74") (pin "1") (pinfunction "1_1") (pintype "passive"))
      (node (ref "IC15") (pin "7") (pinfunction "RFOUT_7") (pintype "bidirectional"))
      (node (ref "L24") (pin "2") (pinfunction "2_2") (pintype "passive"))
    )
    (net (code "173") (name "Net-(IC15-VCC)") (class "Default")
      (node (ref "C72") (pin "1") (pinfunction "1_1") (pintype "passive"))
      (node (ref "C73") (pin "1") (pinfunction "1_1") (pintype "passive"))
      (node (ref "IC15") (pin "1") (pinfunction "VCC_1") (pintype "bidirectional"))
      (node (ref "L11") (pin "1") (pinfunction "1_1") (pintype "passive"))
      (node (ref "L23") (pin "2") (pinfunction "2_2") (pintype "passive"))
    )
    (net (code "174") (name "Net-(IC16-CTL1)") (class "Default")
      (node (ref "C238") (pin "1") (pinfunction "1_1") (pintype "passive"))
      (node (ref "IC16") (pin "17") (pinfunction "CTL1_17") (pintype "bidirectional"))
      (node (ref "R150") (pin "1") (pinfunction "1_1") (pintype "passive"))
    )
    (net (code "175") (name "Net-(IC16-CTL2)") (class "Default")
      (node (ref "C240") (pin "1") (pinfunction "1_1") (pintype "passive"))
      (node (ref "IC16") (pin "16") (pinfunction "CTL2_16") (pintype "bidirectional"))
      (node (ref "R151") (pin "1") (pinfunction "1_1") (pintype "passive"))
    )
    (net (code "176") (name "Net-(IC16-RF1)") (class "Default")
      (node (ref "IC16") (pin "3") (pinfunction "RF1_3") (pintype "bidirectional"))
      (node (ref "IC17") (pin "3") (pinfunction "RF1_3") (pintype "bidirectional"))
    )
    (net (code "177") (name "Net-(IC16-RF2)") (class "Default")
      (node (ref "IC16") (pin "13") (pinfunction "RF2_13") (pintype "bidirectional"))
      (node (ref "IC18") (pin "8") (pinfunction "RF_COM_8") (pintype "bidirectional"))
    )
    (net (code "178") (name "Net-(IC16-RF_COM)") (class "Default")
      (node (ref "IC16") (pin "8") (pinfunction "RF_COM_8") (pintype "bidirectional"))
      (node (ref "R29") (pin "2") (pinfunction "2_2") (pintype "passive"))
    )
    (net (code "179") (name "Net-(IC16-VCC)") (class "Default")
      (node (ref "C75") (pin "1") (pinfunction "1_1") (pintype "passive"))
      (node (ref "IC16") (pin "20") (pinfunction "VCC_20") (pintype "bidirectional"))
      (node (ref "L25") (pin "1") (pinfunction "1_1") (pintype "passive"))
    )
    (net (code "180") (name "Net-(IC17-CTL1)") (class "Default")
      (node (ref "C236") (pin "1") (pinfunction "1_1") (pintype "passive"))
      (node (ref "IC17") (pin "17") (pinfunction "CTL1_17") (pintype "bidirectional"))
      (node (ref "R149") (pin "1") (pinfunction "1_1") (pintype "passive"))
    )
    (net (code "181") (name "Net-(IC17-VCC)") (class "Default")
      (node (ref "C77") (pin "1") (pinfunction "1_1") (pintype "passive"))
      (node (ref "IC17") (pin "20") (pinfunction "VCC_20") (pintype "bidirectional"))
      (node (ref "L26") (pin "2") (pinfunction "2_2") (pintype "passive"))
    )
    (net (code "182") (name "Net-(IC18-CTL1)") (class "Default")
      (node (ref "C242") (pin "1") (pinfunction "1_1") (pintype "passive"))
      (node (ref "IC18") (pin "17") (pinfunction "CTL1_17") (pintype "bidirectional"))
      (node (ref "R152") (pin "1") (pinfunction "1_1") (pintype "passive"))
    )
    (net (code "183") (name "Net-(IC18-VCC)") (class "Default")
      (node (ref "C76") (pin "1") (pinfunction "1_1") (pintype "passive"))
      (node (ref "IC18") (pin "20") (pinfunction "VCC_20") (pintype "bidirectional"))
      (node (ref "L27") (pin "2") (pinfunction "2_2") (pintype "passive"))
    )
    (net (code "184") (name "Net-(IC20-VOUT)") (class "Default")
      (node (ref "C81") (pin "1") (pinfunction "1_1") (pintype "passive"))
      (node (ref "IC20") (pin "5") (pinfunction "VOUT_5") (pintype "power_in"))
      (node (ref "L29") (pin "1") (pinfunction "1_1") (pintype "passive"))
    )
    (net (code "185") (name "Net-(IC21-BIAS_FILT)") (class "Default")
      (node (ref "C89") (pin "1") (pinfunction "1_1") (pintype "passive"))
      (node (ref "IC21") (pin "23") (pinfunction "BIAS_FILT_23") (pintype "bidirectional"))
    )
    (net (code "186") (name "Net-(IC21-CP_OUT)") (class "Default")
      (node (ref "C90") (pin "1") (pinfunction "1_1") (pintype "passive"))
      (node (ref "C92") (pin "1") (pinfunction "1_1") (pintype "passive"))
      (node (ref "IC21") (pin "7") (pinfunction "CP_OUT_7") (pintype "bidirectional"))
      (node (ref "R36") (pin "1") (pinfunction "1_1") (pintype "passive"))
    )
    (net (code "187") (name "Net-(IC21-NOISE_FILT)") (class "Default")
      (node (ref "C88") (pin "1") (pinfunction "1_1") (pintype "passive"))
      (node (ref "IC21") (pin "19") (pinfunction "NOISE_FILT_19") (pintype "bidirectional"))
    )
    (net (code "188") (name "Net-(IC21-REF_IN)") (class "Default")
      (node (ref "C80") (pin "2") (pinfunction "2_2") (pintype "passive"))
      (node (ref "IC21") (pin "29") (pinfunction "REF_IN_29") (pintype "input"))
    )
    (net (code "189") (name "Net-(IC21-REG)") (class "Default")
      (node (ref "C87") (pin "1") (pinfunction "1_1") (pintype "passive"))
      (node (ref "IC21") (pin "24") (pinfunction "REG_24") (pintype "bidirectional"))
    )
    (net (code "190") (name "Net-(IC21-RFOUTB_N)") (class "Default")
      (node (ref "C93") (pin "2") (pinfunction "2_2") (pintype "passive"))
      (node (ref "IC21") (pin "15") (pinfunction "RFOUTB_N_15") (pintype "bidirectional"))
      (node (ref "R35") (pin "1") (pinfunction "1_1") (pintype "passive"))
    )
    (net (code "191") (name "Net-(IC21-RSET)") (class "Default")
      (node (ref "IC21") (pin "22") (pinfunction "RSET_22") (pintype "bidirectional"))
      (node (ref "R30") (pin "2") (pinfunction "2_2") (pintype "passive"))
    )
    (net (code "192") (name "Net-(IC21-SW)") (class "Default")
      (node (ref "IC21") (pin "5") (pinfunction "SW_5") (pintype "bidirectional"))
      (node (ref "R37") (pin "2") (pinfunction "2_2") (pintype "passive"))
      (node (ref "R39") (pin "1") (pinfunction "1_1") (pintype "passive"))
    )
    (net (code "193") (name "Net-(IC21-TUNE)") (class "Default")
      (node (ref "C95") (pin "2") (pinfunction "2_2") (pintype "passive"))
      (node (ref "IC21") (pin "20") (pinfunction "TUNE_20") (pintype "bidirectional"))
      (node (ref "R36") (pin "2") (pinfunction "2_2") (pintype "passive"))
    )
    (net (code "194") (name "Net-(IC21-VCC_CP)") (class "Default")
      (node (ref "C86") (pin "1") (pinfunction "1_1") (pintype "passive"))
      (node (ref "IC21") (pin "10") (pinfunction "VCC_PLL_10") (pintype "bidirectional"))
      (node (ref "IC21") (pin "6") (pinfunction "VCC_CP_6") (pintype "bidirectional"))
      (node (ref "L29") (pin "2") (pinfunction "2_2") (pintype "passive"))
      (node (ref "TP15") (pin "TP") (pinfunction "TP_TP") (pintype "input"))
    )
    (net (code "195") (name "Net-(IC21-VCC_DIG)") (class "Default")
      (node (ref "C83") (pin "1") (pinfunction "1_1") (pintype "passive"))
      (node (ref "C84") (pin "1") (pinfunction "1_1") (pintype "passive"))
      (node (ref "IC21") (pin "28") (pinfunction "VCC_DIG_28") (pintype "bidirectional"))
      (node (ref "IC21") (pin "32") (pinfunction "VDD_SD_32") (pintype "bidirectional"))
      (node (ref "L65") (pin "1") (pinfunction "1_1") (pintype "passive"))
    )
    (net (code "196") (name "Net-(IC21-VCC_RF)") (class "Default")
      (node (ref "C85") (pin "1") (pinfunction "1_1") (pintype "passive"))
      (node (ref "C91") (pin "1") (pinfunction "1_1") (pintype "passive"))
      (node (ref "C94") (pin "1") (pinfunction "1_1") (pintype "passive"))
      (node (ref "IC21") (pin "16") (pinfunction "VCC_RF_16") (pintype "bidirectional"))
      (node (ref "IC21") (pin "17") (pinfunction "VCC_VCO_17") (pintype "bidirectional"))
      (node (ref "L28") (pin "2") (pinfunction "2_2") (pintype "passive"))
      (node (ref "R32") (pin "2") (pinfunction "2_2") (pintype "passive"))
      (node (ref "R33") (pin "2") (pinfunction "2_2") (pintype "passive"))
      (node (ref "R34") (pin "2") (pinfunction "2_2") (pintype "passive"))
      (node (ref "R35") (pin "2") (pinfunction "2_2") (pintype "passive"))
      (node (ref "TP16") (pin "TP") (pinfunction "TP_TP") (pintype "input"))
    )
    (net (code "197") (name "Net-(IC22-IN+)") (class "Default")
      (node (ref "IC22") (pin "3") (pinfunction "IN+_3") (pintype "bidirectional"))
      (node (ref "L30") (pin "1") (pinfunction "1_1") (pintype "passive"))
      (node (ref "R65") (pin "1") (pinfunction "1_1") (pintype "passive"))
      (node (ref "R66") (pin "2") (pinfunction "2_2") (pintype "passive"))
    )
    (net (code "198") (name "Net-(IC22-IN-)") (class "Default")
      (node (ref "IC22") (pin "4") (pinfunction "IN-_4") (pintype "bidirectional"))
      (node (ref "L31") (pin "1") (pinfunction "1_1") (pintype "passive"))
      (node (ref "R64") (pin "1") (pinfunction "1_1") (pintype "passive"))
      (node (ref "R66") (pin "1") (pinfunction "1_1") (pintype "passive"))
    )
    (net (code "199") (name "Net-(IC22-LO+)") (class "Default")
      (node (ref "C98") (pin "2") (pinfunction "2_2") (pintype "passive"))
      (node (ref "IC22") (pin "8") (pinfunction "LO+_8") (pintype "bidirectional"))
    )
    (net (code "200") (name "Net-(IC22-LO-)") (class "Default")
      (node (ref "C97") (pin "2") (pinfunction "2_2") (pintype "passive"))
      (node (ref "IC22") (pin "1") (pinfunction "LO-_1") (pintype "bidirectional"))
    )
    (net (code "201") (name "Net-(IC22-OUT+)") (class "Default")
      (node (ref "C100") (pin "1") (pinfunction "1_1") (pintype "passive"))
      (node (ref "IC22") (pin "6") (pinfunction "OUT+_6") (pintype "bidirectional"))
      (node (ref "R53") (pin "2") (pinfunction "2_2") (pintype "passive"))
    )
    (net (code "202") (name "Net-(IC22-OUT-)") (class "Default")
      (node (ref "C101") (pin "1") (pinfunction "1_1") (pintype "passive"))
      (node (ref "IC22") (pin "5") (pinfunction "OUT-_5") (pintype "bidirectional"))
      (node (ref "R54") (pin "2") (pinfunction "2_2") (pintype "passive"))
    )
    (net (code "203") (name "Net-(IC22-VCC)") (class "Default")
      (node (ref "C102") (pin "2") (pinfunction "2_2") (pintype "passive"))
      (node (ref "C103") (pin "2") (pinfunction "2_2") (pintype "passive"))
      (node (ref "IC22") (pin "7") (pinfunction "VCC_7") (pintype "bidirectional"))
      (node (ref "L12") (pin "1") (pinfunction "1_1") (pintype "passive"))
      (node (ref "R53") (pin "1") (pinfunction "1_1") (pintype "passive"))
      (node (ref "R54") (pin "1") (pinfunction "1_1") (pintype "passive"))
    )
    (net (code "204") (name "Net-(IC23-+IN)") (class "Default")
      (node (ref "C100") (pin "2") (pinfunction "2_2") (pintype "passive"))
      (node (ref "C112") (pin "1") (pinfunction "1_1") (pintype "passive"))
      (node (ref "IC23") (pin "8") (pinfunction "+IN_8") (pintype "input"))
      (node (ref "R55") (pin "1") (pinfunction "1_1") (pintype "passive"))
    )
    (net (code "205") (name "Net-(IC23-+OUT)") (class "Default")
      (node (ref "C113") (pin "1") (pinfunction "1_1") (pintype "passive"))
      (node (ref "IC23") (pin "4") (pinfunction "+OUT_4") (pintype "bidirectional"))
      (node (ref "R56") (pin "1") (pinfunction "1_1") (pintype "passive"))
      (node (ref "R59") (pin "2") (pinfunction "2_2") (pintype "passive"))
    )
    (net (code "206") (name "Net-(IC23--IN)") (class "Default")
      (node (ref "C101") (pin "2") (pinfunction "2_2") (pintype "passive"))
      (node (ref "C113") (pin "2") (pinfunction "2_2") (pintype "passive"))
      (node (ref "IC23") (pin "1") (pinfunction "-IN_1") (pintype "input"))
      (node (ref "R56") (pin "2") (pinfunction "2_2") (pintype "passive"))
    )
    (net (code "207") (name "Net-(IC23--OUT)") (class "Default")
      (node (ref "C112") (pin "2") (pinfunction "2_2") (pintype "passive"))
      (node (ref "IC23") (pin "5") (pinfunction "-OUT_5") (pintype "bidirectional"))
      (node (ref "R55") (pin "2") (pinfunction "2_2") (pintype "passive"))
      (node (ref "R58") (pin "2") (pinfunction "2_2") (pintype "passive"))
    )
    (net (code "208") (name "Net-(IC23-V+)") (class "Default")
      (node (ref "C115") (pin "2") (pinfunction "2_2") (pintype "passive"))
      (node (ref "IC23") (pin "3") (pinfunction "V+_3") (pintype "power_in"))
      (node (ref "L15") (pin "1") (pinfunction "1_1") (pintype "passive"))
    )
    (net (code "209") (name "Net-(IC23-VOCM)") (class "Default")
      (node (ref "C116") (pin "1") (pinfunction "1_1") (pintype "passive"))
      (node (ref "IC23") (pin "2") (pinfunction "VOCM_2") (pintype "output"))
    )
    (net (code "210") (name "Net-(IC24-DETO)") (class "Default")
      (node (ref "IC24") (pin "11") (pinfunction "DETO_11") (pintype "bidirectional"))
      (node (ref "R57") (pin "2") (pinfunction "2_2") (pintype "passive"))
    )
    (net (code "211") (name "Net-(IC24-IN+)") (class "Default")
      (node (ref "C109") (pin "2") (pinfunction "2_2") (pintype "passive"))
      (node (ref "IC24") (pin "15") (pinfunction "IN+_15") (pintype "bidirectional"))
    )
    (net (code "212") (name "Net-(IC24-IN-)") (class "Default")
      (node (ref "C110") (pin "2") (pinfunction "2_2") (pintype "passive"))
      (node (ref "IC24") (pin "16") (pinfunction "IN-_16") (pintype "bidirectional"))
    )
    (net (code "213") (name "Net-(IC24-LO+)") (class "Default")
      (node (ref "C114") (pin "2") (pinfunction "2_2") (pintype "passive"))
      (node (ref "IC24") (pin "3") (pinfunction "LO+_3") (pintype "bidirectional"))
    )
    (net (code "214") (name "Net-(IC24-LO-)") (class "Default")
      (node (ref "C117") (pin "1") (pinfunction "1_1") (pintype "passive"))
      (node (ref "IC24") (pin "4") (pinfunction "LO-_4") (pintype "bidirectional"))
    )
    (net (code "215") (name "Net-(IC24-OUT+)") (class "Default")
      (node (ref "C120") (pin "1") (pinfunction "1_1") (pintype "passive"))
      (node (ref "IC24") (pin "20") (pinfunction "OUT+_20") (pintype "bidirectional"))
      (node (ref "L32") (pin "2") (pinfunction "2_2") (pintype "passive"))
    )
    (net (code "216") (name "Net-(IC24-OUT-)") (class "Default")
      (node (ref "C123") (pin "1") (pinfunction "1_1") (pintype "passive"))
      (node (ref "IC24") (pin "21") (pinfunction "OUT-_21") (pintype "bidirectional"))
      (node (ref "L33") (pin "2") (pinfunction "2_2") (pintype "passive"))
    )
    (net (code "217") (name "Net-(IC24-VPDT)") (class "Default")
      (node (ref "C104") (pin "1") (pinfunction "1_1") (pintype "passive"))
      (node (ref "C105") (pin "1") (pinfunction "1_1") (pintype "passive"))
      (node (ref "C106") (pin "1") (pinfunction "1_1") (pintype "passive"))
      (node (ref "C108") (pin "1") (pinfunction "1_1") (pintype "passive"))
      (node (ref "C111") (pin "1") (pinfunction "1_1") (pintype "passive"))
      (node (ref "IC24") (pin "13") (pinfunction "VPDT_13") (pintype "bidirectional"))
      (node (ref "IC24") (pin "18") (pinfunction "VPRF_18") (pintype "bidirectional"))
      (node (ref "IC24") (pin "24") (pinfunction "VPLO_24") (pintype "bidirectional"))
      (node (ref "IC24") (pin "7") (pinfunction "VPLO_7") (pintype "bidirectional"))
      (node (ref "L17") (pin "1") (pinfunction "1_1") (pintype "passive"))
    )
    (net (code "218") (name "Net-(IC24-VSET)") (class "Default")
      (node (ref "C118") (pin "2") (pinfunction "2_2") (pintype "passive"))
      (node (ref "IC24") (pin "10") (pinfunction "VSET_10") (pintype "bidirectional"))
      (node (ref "R57") (pin "1") (pinfunction "1_1") (pintype "passive"))
      (node (ref "R60") (pin "2") (pinfunction "2_2") (pintype "passive"))
    )
    (net (code "219") (name "Net-(IC25-EN)") (class "Default")
      (node (ref "C129") (pin "1") (pinfunction "1_1") (pintype "passive"))
      (node (ref "IC25") (pin "1") (pinfunction "VIN_1") (pintype "power_in"))
      (node (ref "IC25") (pin "3") (pinfunction "EN_3") (pintype "input"))
      (node (ref "IC26") (pin "1") (pinfunction "VREF_1") (pintype "bidirectional"))
      (node (ref "L13") (pin "1") (pinfunction "1_1") (pintype "passive"))
    )
    (net (code "220") (name "Net-(IC25-VOUT)") (class "Default")
      (node (ref "C131") (pin "1") (pinfunction "1_1") (pintype "passive"))
      (node (ref "IC25") (pin "5") (pinfunction "VOUT_5") (pintype "power_in"))
      (node (ref "IC26") (pin "2") (pinfunction "AVDD_2") (pintype "bidirectional"))
      (node (ref "TP17") (pin "TP") (pinfunction "TP_TP") (pintype "input"))
    )
    (net (code "221") (name "Net-(IC26-AIN+)") (class "Default")
      (node (ref "C125") (pin "2") (pinfunction "2_2") (pintype "passive"))
      (node (ref "C126") (pin "1") (pinfunction "1_1") (pintype "passive"))
      (node (ref "IC26") (pin "3") (pinfunction "AIN+_3") (pintype "bidirectional"))
      (node (ref "R61") (pin "1") (pinfunction "1_1") (pintype "passive"))
    )
    (net (code "222") (name "Net-(IC26-AIN-)") (class "Default")
      (node (ref "C126") (pin "2") (pinfunction "2_2") (pintype "passive"))
      (node (ref "C127") (pin "1") (pinfunction "1_1") (pintype "passive"))
      (node (ref "IC26") (pin "4") (pinfunction "AIN-_4") (pintype "bidirectional"))
      (node (ref "R62") (pin "1") (pinfunction "1_1") (pintype "passive"))
    )
    (net (code "223") (name "Net-(IC27-IN+)") (class "Default")
      (node (ref "IC27") (pin "3") (pinfunction "IN+_3") (pintype "bidirectional"))
      (node (ref "L38") (pin "1") (pinfunction "1_1") (pintype "passive"))
      (node (ref "R92") (pin "1") (pinfunction "1_1") (pintype "passive"))
      (node (ref "R93") (pin "2") (pinfunction "2_2") (pintype "passive"))
    )
    (net (code "224") (name "Net-(IC27-IN-)") (class "Default")
      (node (ref "IC27") (pin "4") (pinfunction "IN-_4") (pintype "bidirectional"))
      (node (ref "L39") (pin "1") (pinfunction "1_1") (pintype "passive"))
      (node (ref "R91") (pin "1") (pinfunction "1_1") (pintype "passive"))
      (node (ref "R93") (pin "1") (pinfunction "1_1") (pintype "passive"))
    )
    (net (code "225") (name "Net-(IC27-LO+)") (class "Default")
      (node (ref "C135") (pin "2") (pinfunction "2_2") (pintype "passive"))
      (node (ref "IC27") (pin "8") (pinfunction "LO+_8") (pintype "bidirectional"))
    )
    (net (code "226") (name "Net-(IC27-LO-)") (class "Default")
      (node (ref "C134") (pin "2") (pinfunction "2_2") (pintype "passive"))
      (node (ref "IC27") (pin "1") (pinfunction "LO-_1") (pintype "bidirectional"))
    )
    (net (code "227") (name "Net-(IC27-OUT+)") (class "Default")
      (node (ref "C137") (pin "1") (pinfunction "1_1") (pintype "passive"))
      (node (ref "IC27") (pin "6") (pinfunction "OUT+_6") (pintype "bidirectional"))
      (node (ref "R80") (pin "2") (pinfunction "2_2") (pintype "passive"))
    )
    (net (code "228") (name "Net-(IC27-OUT-)") (class "Default")
      (node (ref "C138") (pin "1") (pinfunction "1_1") (pintype "passive"))
      (node (ref "IC27") (pin "5") (pinfunction "OUT-_5") (pintype "bidirectional"))
      (node (ref "R81") (pin "2") (pinfunction "2_2") (pintype "passive"))
    )
    (net (code "229") (name "Net-(IC27-VCC)") (class "Default")
      (node (ref "C139") (pin "2") (pinfunction "2_2") (pintype "passive"))
      (node (ref "C140") (pin "2") (pinfunction "2_2") (pintype "passive"))
      (node (ref "IC27") (pin "7") (pinfunction "VCC_7") (pintype "bidirectional"))
      (node (ref "L57") (pin "1") (pinfunction "1_1") (pintype "passive"))
      (node (ref "R80") (pin "1") (pinfunction "1_1") (pintype "passive"))
      (node (ref "R81") (pin "1") (pinfunction "1_1") (pintype "passive"))
    )
    (net (code "230") (name "Net-(IC28-+IN)") (class "Default")
      (node (ref "C137") (pin "2") (pinfunction "2_2") (pintype "passive"))
      (node (ref "C149") (pin "1") (pinfunction "1_1") (pintype "passive"))
      (node (ref "IC28") (pin "8") (pinfunction "+IN_8") (pintype "input"))
      (node (ref "R82") (pin "1") (pinfunction "1_1") (pintype "passive"))
    )
    (net (code "231") (name "Net-(IC28-+OUT)") (class "Default")
      (node (ref "C150") (pin "1") (pinfunction "1_1") (pintype "passive"))
      (node (ref "IC28") (pin "4") (pinfunction "+OUT_4") (pintype "bidirectional"))
      (node (ref "R83") (pin "1") (pinfunction "1_1") (pintype "passive"))
      (node (ref "R86") (pin "2") (pinfunction "2_2") (pintype "passive"))
    )
    (net (code "232") (name "Net-(IC28--IN)") (class "Default")
      (node (ref "C138") (pin "2") (pinfunction "2_2") (pintype "passive"))
      (node (ref "C150") (pin "2") (pinfunction "2_2") (pintype "passive"))
      (node (ref "IC28") (pin "1") (pinfunction "-IN_1") (pintype "input"))
      (node (ref "R83") (pin "2") (pinfunction "2_2") (pintype "passive"))
    )
    (net (code "233") (name "Net-(IC28--OUT)") (class "Default")
      (node (ref "C149") (pin "2") (pinfunction "2_2") (pintype "passive"))
      (node (ref "IC28") (pin "5") (pinfunction "-OUT_5") (pintype "bidirectional"))
      (node (ref "R82") (pin "2") (pinfunction "2_2") (pintype "passive"))
      (node (ref "R85") (pin "2") (pinfunction "2_2") (pintype "passive"))
    )
    (net (code "234") (name "Net-(IC28-V+)") (class "Default")
      (node (ref "C152") (pin "2") (pinfunction "2_2") (pintype "passive"))
      (node (ref "IC28") (pin "3") (pinfunction "V+_3") (pintype "power_in"))
      (node (ref "L56") (pin "1") (pinfunction "1_1") (pintype "passive"))
    )
    (net (code "235") (name "Net-(IC28-VOCM)") (class "Default")
      (node (ref "C153") (pin "1") (pinfunction "1_1") (pintype "passive"))
      (node (ref "IC28") (pin "2") (pinfunction "VOCM_2") (pintype "output"))
    )
    (net (code "236") (name "Net-(IC29-DETO)") (class "Default")
      (node (ref "IC29") (pin "11") (pinfunction "DETO_11") (pintype "bidirectional"))
      (node (ref "R84") (pin "2") (pinfunction "2_2") (pintype "passive"))
    )
    (net (code "237") (name "Net-(IC29-IN+)") (class "Default")
      (node (ref "C146") (pin "2") (pinfunction "2_2") (pintype "passive"))
      (node (ref "IC29") (pin "15") (pinfunction "IN+_15") (pintype "bidirectional"))
    )
    (net (code "238") (name "Net-(IC29-IN-)") (class "Default")
      (node (ref "C147") (pin "2") (pinfunction "2_2") (pintype "passive"))
      (node (ref "IC29") (pin "16") (pinfunction "IN-_16") (pintype "bidirectional"))
    )
    (net (code "239") (name "Net-(IC29-LO+)") (class "Default")
      (node (ref "C151") (pin "2") (pinfunction "2_2") (pintype "passive"))
      (node (ref "IC29") (pin "3") (pinfunction "LO+_3") (pintype "bidirectional"))
    )
    (net (code "240") (name "Net-(IC29-LO-)") (class "Default")
      (node (ref "C154") (pin "1") (pinfunction "1_1") (pintype "passive"))
      (node (ref "IC29") (pin "4") (pinfunction "LO-_4") (pintype "bidirectional"))
    )
    (net (code "241") (name "Net-(IC29-OUT+)") (class "Default")
      (node (ref "C157") (pin "1") (pinfunction "1_1") (pintype "passive"))
      (node (ref "IC29") (pin "20") (pinfunction "OUT+_20") (pintype "bidirectional"))
      (node (ref "L40") (pin "2") (pinfunction "2_2") (pintype "passive"))
    )
    (net (code "242") (name "Net-(IC29-OUT-)") (class "Default")
      (node (ref "C160") (pin "1") (pinfunction "1_1") (pintype "passive"))
      (node (ref "IC29") (pin "21") (pinfunction "OUT-_21") (pintype "bidirectional"))
      (node (ref "L41") (pin "2") (pinfunction "2_2") (pintype "passive"))
    )
    (net (code "243") (name "Net-(IC29-VPDT)") (class "Default")
      (node (ref "C141") (pin "1") (pinfunction "1_1") (pintype "passive"))
      (node (ref "C142") (pin "1") (pinfunction "1_1") (pintype "passive"))
      (node (ref "C143") (pin "1") (pinfunction "1_1") (pintype "passive"))
      (node (ref "C145") (pin "1") (pinfunction "1_1") (pintype "passive"))
      (node (ref "C148") (pin "1") (pinfunction "1_1") (pintype "passive"))
      (node (ref "IC29") (pin "13") (pinfunction "VPDT_13") (pintype "bidirectional"))
      (node (ref "IC29") (pin "18") (pinfunction "VPRF_18") (pintype "bidirectional"))
      (node (ref "IC29") (pin "24") (pinfunction "VPLO_24") (pintype "bidirectional"))
      (node (ref "IC29") (pin "7") (pinfunction "VPLO_7") (pintype "bidirectional"))
      (node (ref "L54") (pin "1") (pinfunction "1_1") (pintype "passive"))
    )
    (net (code "244") (name "Net-(IC29-VSET)") (class "Default")
      (node (ref "C155") (pin "2") (pinfunction "2_2") (pintype "passive"))
      (node (ref "IC29") (pin "10") (pinfunction "VSET_10") (pintype "bidirectional"))
      (node (ref "R84") (pin "1") (pinfunction "1_1") (pintype "passive"))
      (node (ref "R87") (pin "2") (pinfunction "2_2") (pintype "passive"))
    )
    (net (code "245") (name "Net-(IC30-EN)") (class "Default")
      (node (ref "C166") (pin "1") (pinfunction "1_1") (pintype "passive"))
      (node (ref "IC30") (pin "1") (pinfunction "VIN_1") (pintype "power_in"))
      (node (ref "IC30") (pin "3") (pinfunction "EN_3") (pintype "input"))
      (node (ref "IC31") (pin "1") (pinfunction "VREF_1") (pintype "bidirectional"))
      (node (ref "L58") (pin "1") (pinfunction "1_1") (pintype "passive"))
    )
    (net (code "246") (name "Net-(IC30-VOUT)") (class "Default")
      (node (ref "C168") (pin "1") (pinfunction "1_1") (pintype "passive"))
      (node (ref "IC30") (pin "5") (pinfunction "VOUT_5") (pintype "power_in"))
      (node (ref "IC31") (pin "2") (pinfunction "AVDD_2") (pintype "bidirectional"))
      (node (ref "TP18") (pin "TP") (pinfunction "TP_TP") (pintype "input"))
    )
    (net (code "247") (name "Net-(IC31-AIN+)") (class "Default")
      (node (ref "C162") (pin "2") (pinfunction "2_2") (pintype "passive"))
      (node (ref "C163") (pin "1") (pinfunction "1_1") (pintype "passive"))
      (node (ref "IC31") (pin "3") (pinfunction "AIN+_3") (pintype "bidirectional"))
      (node (ref "R88") (pin "1") (pinfunction "1_1") (pintype "passive"))
    )
    (net (code "248") (name "Net-(IC31-AIN-)") (class "Default")
      (node (ref "C163") (pin "2") (pinfunction "2_2") (pintype "passive"))
      (node (ref "C164") (pin "1") (pinfunction "1_1") (pintype "passive"))
      (node (ref "IC31") (pin "4") (pinfunction "AIN-_4") (pintype "bidirectional"))
      (node (ref "R89") (pin "1") (pinfunction "1_1") (pintype "passive"))
    )
    (net (code "249") (name "Net-(IC32-+IN)") (class "Default")
      (node (ref "C173") (pin "1") (pinfunction "1_1") (pintype "passive"))
      (node (ref "C202") (pin "2") (pinfunction "2_2") (pintype "passive"))
      (node (ref "IC32") (pin "8") (pinfunction "+IN_8") (pintype "input"))
      (node (ref "R94") (pin "1") (pinfunction "1_1") (pintype "passive"))
    )
    (net (code "250") (name "Net-(IC32-+OUT)") (class "Default")
      (node (ref "C174") (pin "1") (pinfunction "1_1") (pintype "passive"))
      (node (ref "IC32") (pin "4") (pinfunction "+OUT_4") (pintype "bidirectional"))
      (node (ref "R95") (pin "1") (pinfunction "1_1") (pintype "passive"))
      (node (ref "R97") (pin "2") (pinfunction "2_2") (pintype "passive"))
    )
    (net (code "251") (name "Net-(IC32--IN)") (class "Default")
      (node (ref "C174") (pin "2") (pinfunction "2_2") (pintype "passive"))
      (node (ref "C203") (pin "2") (pinfunction "2_2") (pintype "passive"))
      (node (ref "IC32") (pin "1") (pinfunction "-IN_1") (pintype "input"))
      (node (ref "R95") (pin "2") (pinfunction "2_2") (pintype "passive"))
    )
    (net (code "252") (name "Net-(IC32--OUT)") (class "Default")
      (node (ref "C173") (pin "2") (pinfunction "2_2") (pintype "passive"))
      (node (ref "IC32") (pin "5") (pinfunction "-OUT_5") (pintype "bidirectional"))
      (node (ref "R94") (pin "2") (pinfunction "2_2") (pintype "passive"))
      (node (ref "R96") (pin "2") (pinfunction "2_2") (pintype "passive"))
    )
    (net (code "253") (name "Net-(IC32-V+)") (class "Default")
      (node (ref "C181") (pin "2") (pinfunction "2_2") (pintype "passive"))
      (node (ref "IC32") (pin "3") (pinfunction "V+_3") (pintype "power_in"))
      (node (ref "L62") (pin "1") (pinfunction "1_1") (pintype "passive"))
    )
    (net (code "254") (name "Net-(IC32-VOCM)") (class "Default")
      (node (ref "C182") (pin "1") (pinfunction "1_1") (pintype "passive"))
      (node (ref "IC32") (pin "2") (pinfunction "VOCM_2") (pintype "output"))
    )
    (net (code "255") (name "Net-(IC33-DETO)") (class "Default")
      (node (ref "IC33") (pin "11") (pinfunction "DETO_11") (pintype "bidirectional"))
      (node (ref "R100") (pin "2") (pinfunction "2_2") (pintype "passive"))
    )
    (net (code "256") (name "Net-(IC33-IN+)") (class "Default")
      (node (ref "C178") (pin "2") (pinfunction "2_2") (pintype "passive"))
      (node (ref "IC33") (pin "15") (pinfunction "IN+_15") (pintype "bidirectional"))
    )
    (net (code "257") (name "Net-(IC33-IN-)") (class "Default")
      (node (ref "C179") (pin "2") (pinfunction "2_2") (pintype "passive"))
      (node (ref "IC33") (pin "16") (pinfunction "IN-_16") (pintype "bidirectional"))
    )
    (net (code "258") (name "Net-(IC33-LO+)") (class "Default")
      (node (ref "C183") (pin "2") (pinfunction "2_2") (pintype "passive"))
      (node (ref "IC33") (pin "3") (pinfunction "LO+_3") (pintype "bidirectional"))
    )
    (net (code "259") (name "Net-(IC33-LO-)") (class "Default")
      (node (ref "C185") (pin "1") (pinfunction "1_1") (pintype "passive"))
      (node (ref "IC33") (pin "4") (pinfunction "LO-_4") (pintype "bidirectional"))
    )
    (net (code "260") (name "Net-(IC33-OUT+)") (class "Default")
      (node (ref "C191") (pin "1") (pinfunction "1_1") (pintype "passive"))
      (node (ref "IC33") (pin "20") (pinfunction "OUT+_20") (pintype "bidirectional"))
      (node (ref "L46") (pin "2") (pinfunction "2_2") (pintype "passive"))
    )
    (net (code "261") (name "Net-(IC33-OUT-)") (class "Default")
      (node (ref "C192") (pin "1") (pinfunction "1_1") (pintype "passive"))
      (node (ref "IC33") (pin "21") (pinfunction "OUT-_21") (pintype "bidirectional"))
      (node (ref "L47") (pin "2") (pinfunction "2_2") (pintype "passive"))
    )
    (net (code "262") (name "Net-(IC33-VPDT)") (class "Default")
      (node (ref "C171") (pin "1") (pinfunction "1_1") (pintype "passive"))
      (node (ref "C172") (pin "1") (pinfunction "1_1") (pintype "passive"))
      (node (ref "C175") (pin "1") (pinfunction "1_1") (pintype "passive"))
      (node (ref "C177") (pin "1") (pinfunction "1_1") (pintype "passive"))
      (node (ref "C180") (pin "1") (pinfunction "1_1") (pintype "passive"))
      (node (ref "IC33") (pin "13") (pinfunction "VPDT_13") (pintype "bidirectional"))
      (node (ref "IC33") (pin "18") (pinfunction "VPRF_18") (pintype "bidirectional"))
      (node (ref "IC33") (pin "24") (pinfunction "VPLO_24") (pintype "bidirectional"))
      (node (ref "IC33") (pin "7") (pinfunction "VPLO_7") (pintype "bidirectional"))
      (node (ref "L59") (pin "1") (pinfunction "1_1") (pintype "passive"))
    )
    (net (code "263") (name "Net-(IC33-VSET)") (class "Default")
      (node (ref "C186") (pin "2") (pinfunction "2_2") (pintype "passive"))
      (node (ref "IC33") (pin "10") (pinfunction "VSET_10") (pintype "bidirectional"))
      (node (ref "R100") (pin "1") (pinfunction "1_1") (pintype "passive"))
      (node (ref "R101") (pin "2") (pinfunction "2_2") (pintype "passive"))
    )
    (net (code "264") (name "Net-(IC34-EN)") (class "Default")
      (node (ref "C195") (pin "1") (pinfunction "1_1") (pintype "passive"))
      (node (ref "IC34") (pin "1") (pinfunction "VIN_1") (pintype "power_in"))
      (node (ref "IC34") (pin "3") (pinfunction "EN_3") (pintype "input"))
      (node (ref "IC35") (pin "1") (pinfunction "VREF_1") (pintype "bidirectional"))
      (node (ref "L63") (pin "2") (pinfunction "2_2") (pintype "passive"))
    )
    (net (code "265") (name "Net-(IC34-VOUT)") (class "Default")
      (node (ref "C198") (pin "1") (pinfunction "1_1") (pintype "passive"))
      (node (ref "IC34") (pin "5") (pinfunction "VOUT_5") (pintype "power_in"))
      (node (ref "IC35") (pin "2") (pinfunction "AVDD_2") (pintype "bidirectional"))
      (node (ref "TP19") (pin "TP") (pinfunction "TP_TP") (pintype "input"))
    )
    (net (code "266") (name "Net-(IC35-AIN+)") (class "Default")
      (node (ref "C187") (pin "2") (pinfunction "2_2") (pintype "passive"))
      (node (ref "C188") (pin "1") (pinfunction "1_1") (pintype "passive"))
      (node (ref "IC35") (pin "3") (pinfunction "AIN+_3") (pintype "bidirectional"))
      (node (ref "R98") (pin "1") (pinfunction "1_1") (pintype "passive"))
    )
    (net (code "267") (name "Net-(IC35-AIN-)") (class "Default")
      (node (ref "C188") (pin "2") (pinfunction "2_2") (pintype "passive"))
      (node (ref "C189") (pin "1") (pinfunction "1_1") (pintype "passive"))
      (node (ref "IC35") (pin "4") (pinfunction "AIN-_4") (pintype "bidirectional"))
      (node (ref "R99") (pin "1") (pinfunction "1_1") (pintype "passive"))
    )
    (net (code "268") (name "Net-(IC36-IN+)") (class "Default")
      (node (ref "C197") (pin "2") (pinfunction "2_2") (pintype "passive"))
      (node (ref "IC36") (pin "3") (pinfunction "IN+_3") (pintype "bidirectional"))
      (node (ref "L51") (pin "2") (pinfunction "2_2") (pintype "passive"))
      (node (ref "L53") (pin "1") (pinfunction "1_1") (pintype "passive"))
    )
    (net (code "269") (name "Net-(IC36-IN-)") (class "Default")
      (node (ref "C197") (pin "1") (pinfunction "1_1") (pintype "passive"))
      (node (ref "IC36") (pin "4") (pinfunction "IN-_4") (pintype "bidirectional"))
      (node (ref "L50") (pin "2") (pinfunction "2_2") (pintype "passive"))
      (node (ref "L52") (pin "1") (pinfunction "1_1") (pintype "passive"))
    )
    (net (code "270") (name "Net-(IC36-LO+)") (class "Default")
      (node (ref "C200") (pin "2") (pinfunction "2_2") (pintype "passive"))
      (node (ref "IC36") (pin "8") (pinfunction "LO+_8") (pintype "bidirectional"))
    )
    (net (code "271") (name "Net-(IC36-LO-)") (class "Default")
      (node (ref "C199") (pin "2") (pinfunction "2_2") (pintype "passive"))
      (node (ref "IC36") (pin "1") (pinfunction "LO-_1") (pintype "bidirectional"))
    )
    (net (code "272") (name "Net-(IC36-OUT+)") (class "Default")
      (node (ref "C202") (pin "1") (pinfunction "1_1") (pintype "passive"))
      (node (ref "IC36") (pin "6") (pinfunction "OUT+_6") (pintype "bidirectional"))
      (node (ref "R102") (pin "2") (pinfunction "2_2") (pintype "passive"))
    )
    (net (code "273") (name "Net-(IC36-OUT-)") (class "Default")
      (node (ref "C203") (pin "1") (pinfunction "1_1") (pintype "passive"))
      (node (ref "IC36") (pin "5") (pinfunction "OUT-_5") (pintype "bidirectional"))
      (node (ref "R103") (pin "2") (pinfunction "2_2") (pintype "passive"))
    )
    (net (code "274") (name "Net-(IC36-VCC)") (class "Default")
      (node (ref "C204") (pin "2") (pinfunction "2_2") (pintype "passive"))
      (node (ref "C205") (pin "2") (pinfunction "2_2") (pintype "passive"))
      (node (ref "IC36") (pin "7") (pinfunction "VCC_7") (pintype "bidirectional"))
      (node (ref "L61") (pin "1") (pinfunction "1_1") (pintype "passive"))
      (node (ref "R102") (pin "1") (pinfunction "1_1") (pintype "passive"))
      (node (ref "R103") (pin "1") (pinfunction "1_1") (pintype "passive"))
    )
    (net (code "275") (name "Net-(IC37-PA9)") (class "Default")
      (node (ref "IC37") (pin "31") (pinfunction "PA9_31") (pintype "bidirectional"))
      (node (ref "IC37") (pin "44") (pinfunction "PB6_44") (pintype "bidirectional"))
      (node (ref "J4") (pin "4") (pinfunction "CC1_4") (pintype "bidirectional"))
    )
    (net (code "276") (name "Net-(IC37-PA10)") (class "Default")
      (node (ref "IC37") (pin "32") (pinfunction "PA10_32") (pintype "bidirectional"))
      (node (ref "IC37") (pin "42") (pinfunction "PB4_42") (pintype "bidirectional"))
      (node (ref "J4") (pin "10") (pinfunction "CC2_10") (pintype "bidirectional"))
    )
    (net (code "277") (name "Net-(IC37-PA11)") (class "Default")
      (node (ref "IC37") (pin "33") (pinfunction "PA11_33") (pintype "bidirectional"))
      (node (ref "R118") (pin "2") (pinfunction "2_2") (pintype "passive"))
    )
    (net (code "278") (name "Net-(IC37-PA12)") (class "Default")
      (node (ref "IC37") (pin "34") (pinfunction "PA12_34") (pintype "bidirectional"))
      (node (ref "R119") (pin "1") (pinfunction "1_1") (pintype "passive"))
    )
    (net (code "279") (name "Net-(IC37-PA15)") (class "Default")
      (node (ref "IC37") (pin "38") (pinfunction "PA15_38") (pintype "bidirectional"))
      (node (ref "R120") (pin "2") (pinfunction "2_2") (pintype "passive"))
    )
    (net (code "280") (name "Net-(J4-D+1)") (class "Default")
      (node (ref "J4") (pin "6") (pinfunction "D+1_6") (pintype "bidirectional"))
      (node (ref "J4") (pin "8") (pinfunction "D+2_8") (pintype "bidirectional"))
      (node (ref "R119") (pin "2") (pinfunction "2_2") (pintype "passive"))
    )
    (net (code "281") (name "Net-(J4-D-1)") (class "Default")
      (node (ref "J4") (pin "5") (pinfunction "D-2_5") (pintype "bidirectional"))
      (node (ref "J4") (pin "7") (pinfunction "D-1_7") (pintype "bidirectional"))
      (node (ref "R118") (pin "1") (pinfunction "1_1") (pintype "passive"))
    )
    (net (code "282") (name "Net-(L1-2)") (class "Default")
      (node (ref "D1") (pin "A") (pinfunction "A_A") (pintype "passive"))
      (node (ref "IC1") (pin "7") (pinfunction "SW_7") (pintype "bidirectional"))
      (node (ref "IC1") (pin "8") (pinfunction "SW_8") (pintype "bidirectional"))
      (node (ref "L1") (pin "P$2") (pinfunction "2_P$2") (pintype "passive"))
    )
    (net (code "283") (name "Net-(L5-1)") (class "Default")
      (node (ref "C12") (pin "1") (pinfunction "1_1") (pintype "passive"))
      (node (ref "C13") (pin "1") (pinfunction "1_1") (pintype "passive"))
      (node (ref "C9") (pin "1") (pinfunction "1_1") (pintype "passive"))
      (node (ref "D1") (pin "C") (pinfunction "C_C") (pintype "passive"))
      (node (ref "L5") (pin "P$1") (pinfunction "1_P$1") (pintype "passive"))
      (node (ref "R2") (pin "2") (pinfunction "2_2") (pintype "passive"))
      (node (ref "R4") (pin "2") (pinfunction "2_2") (pintype "passive"))
    )
    (net (code "284") (name "Net-(L11-Pad2)") (class "Default")
      (node (ref "L11") (pin "2") (pinfunction "2_2") (pintype "passive"))
      (node (ref "L24") (pin "1") (pinfunction "1_1") (pintype "passive"))
    )
    (net (code "285") (name "Net-(LED1-PadC)") (class "Default")
      (node (ref "LED1") (pin "C") (pinfunction "C_C") (pintype "passive"))
      (node (ref "R120") (pin "1") (pinfunction "1_1") (pintype "passive"))
    )
    (net (code "286") (name "Net-(LED2-PadC)") (class "Default")
      (node (ref "LED2") (pin "C") (pinfunction "C_C") (pintype "passive"))
      (node (ref "R134") (pin "1") (pinfunction "1_1") (pintype "passive"))
    )
    (net (code "287") (name "Net-(LED3-PadC)") (class "Default")
      (node (ref "LED3") (pin "C") (pinfunction "C_C") (pintype "passive"))
      (node (ref "R135") (pin "1") (pinfunction "1_1") (pintype "passive"))
    )
    (net (code "288") (name "Net-(LED4-PadC)") (class "Default")
      (node (ref "LED4") (pin "C") (pinfunction "C_C") (pintype "passive"))
      (node (ref "R136") (pin "1") (pinfunction "1_1") (pintype "passive"))
    )
    (net (code "289") (name "Net-(LED5-PadC)") (class "Default")
      (node (ref "LED5") (pin "C") (pinfunction "C_C") (pintype "passive"))
      (node (ref "R137") (pin "1") (pinfunction "1_1") (pintype "passive"))
    )
    (net (code "290") (name "Net-(LED6-PadC)") (class "Default")
      (node (ref "LED6") (pin "C") (pinfunction "C_C") (pintype "passive"))
      (node (ref "R138") (pin "1") (pinfunction "1_1") (pintype "passive"))
    )
    (net (code "291") (name "Net-(LED7-PadC)") (class "Default")
      (node (ref "LED7") (pin "C") (pinfunction "C_C") (pintype "passive"))
      (node (ref "R139") (pin "1") (pinfunction "1_1") (pintype "passive"))
    )
    (net (code "292") (name "Net-(LED8-PadC)") (class "Default")
      (node (ref "LED8") (pin "C") (pinfunction "C_C") (pintype "passive"))
      (node (ref "R140") (pin "1") (pinfunction "1_1") (pintype "passive"))
    )
    (net (code "293") (name "Net-(LED9-PadC)") (class "Default")
      (node (ref "LED9") (pin "C") (pinfunction "C_C") (pintype "passive"))
      (node (ref "R141") (pin "1") (pinfunction "1_1") (pintype "passive"))
    )
    (net (code "294") (name "Net-(LED10-PadC)") (class "Default")
      (node (ref "LED10") (pin "C") (pinfunction "C_C") (pintype "passive"))
      (node (ref "R142") (pin "1") (pinfunction "1_1") (pintype "passive"))
    )
    (net (code "295") (name "Net-(Q1-G)") (class "Default")
      (node (ref "J1") (pin "3") (pinfunction "3_3") (pintype "passive"))
      (node (ref "Q1") (pin "1") (pinfunction "G_1") (pintype "passive"))
      (node (ref "Q2") (pin "1") (pinfunction "G_1") (pintype "passive"))
      (node (ref "R125") (pin "1") (pinfunction "1_1") (pintype "passive"))
    )
    (net (code "296") (name "Net-(Q1-S)") (class "Default")
      (node (ref "Q1") (pin "2") (pinfunction "S_2") (pintype "passive"))
      (node (ref "Q2") (pin "2") (pinfunction "S_2") (pintype "passive"))
      (node (ref "R125") (pin "2") (pinfunction "2_2") (pintype "passive"))
    )
    (net (code "297") (name "Net-(R26-Pad2)") (class "Default")
      (node (ref "R26") (pin "2") (pinfunction "2_2") (pintype "passive"))
      (node (ref "R27") (pin "2") (pinfunction "2_2") (pintype "passive"))
      (node (ref "R29") (pin "1") (pinfunction "1_1") (pintype "passive"))
    )
    (net (code "298") (name "Net-(R40-IN)") (class "Default")
      (node (ref "R40") (pin "1") (pinfunction "IN_1") (pintype "bidirectional"))
      (node (ref "R72") (pin "2") (pinfunction "2_2") (pintype "passive"))
      (node (ref "R73") (pin "2") (pinfunction "2_2") (pintype "passive"))
    )
    (net (code "299") (name "Net-(R40-OUT)") (class "Default")
      (node (ref "C133") (pin "2") (pinfunction "2_2") (pintype "passive"))
      (node (ref "R40") (pin "2") (pinfunction "OUT_2") (pintype "bidirectional"))
    )
    (net (code "300") (name "Net-(R47-IN)") (class "Default")
      (node (ref "C136") (pin "2") (pinfunction "2_2") (pintype "passive"))
      (node (ref "R47") (pin "1") (pinfunction "IN_1") (pintype "bidirectional"))
      (node (ref "R47") (pin "2") (pinfunction "OUT_2") (pintype "bidirectional"))
      (node (ref "R72") (pin "1") (pinfunction "1_1") (pintype "passive"))
      (node (ref "T2") (pin "4") (pinfunction "OUT+_4") (pintype "bidirectional"))
    )
    (net (code "301") (name "Net-(R48-IN)") (class "Default")
      (node (ref "C99") (pin "2") (pinfunction "2_2") (pintype "passive"))
      (node (ref "R45") (pin "1") (pinfunction "1_1") (pintype "passive"))
      (node (ref "R48") (pin "1") (pinfunction "IN_1") (pintype "bidirectional"))
      (node (ref "R48") (pin "2") (pinfunction "OUT_2") (pintype "bidirectional"))
      (node (ref "T1") (pin "6") (pinfunction "OUT-_6") (pintype "bidirectional"))
    )
    (net (code "302") (name "Net-(R49-IN)") (class "Default")
      (node (ref "C96") (pin "2") (pinfunction "2_2") (pintype "passive"))
      (node (ref "R49") (pin "1") (pinfunction "IN_1") (pintype "bidirectional"))
    )
    (net (code "303") (name "Net-(R49-OUT)") (class "Default")
      (node (ref "R45") (pin "2") (pinfunction "2_2") (pintype "passive"))
      (node (ref "R46") (pin "2") (pinfunction "2_2") (pintype "passive"))
      (node (ref "R49") (pin "2") (pinfunction "OUT_2") (pintype "bidirectional"))
    )
    (net (code "304") (name "Net-(T1-IN+)") (class "Default")
      (node (ref "C107") (pin "1") (pinfunction "1_1") (pintype "passive"))
      (node (ref "C110") (pin "1") (pinfunction "1_1") (pintype "passive"))
      (node (ref "T1") (pin "3") (pinfunction "IN+_3") (pintype "bidirectional"))
    )
    (net (code "305") (name "Net-(T1-IN-)") (class "Default")
      (node (ref "C107") (pin "2") (pinfunction "2_2") (pintype "passive"))
      (node (ref "C109") (pin "1") (pinfunction "1_1") (pintype "passive"))
      (node (ref "T1") (pin "2") (pinfunction "IN-_2") (pintype "bidirectional"))
    )
    (net (code "306") (name "Net-(T1-OUT+)") (class "Default")
      (node (ref "R46") (pin "1") (pinfunction "1_1") (pintype "passive"))
      (node (ref "R50") (pin "1") (pinfunction "1_1") (pintype "passive"))
      (node (ref "T1") (pin "4") (pinfunction "OUT+_4") (pintype "bidirectional"))
    )
    (net (code "307") (name "Net-(T2-IN+)") (class "Default")
      (node (ref "C144") (pin "1") (pinfunction "1_1") (pintype "passive"))
      (node (ref "C147") (pin "1") (pinfunction "1_1") (pintype "passive"))
      (node (ref "T2") (pin "3") (pinfunction "IN+_3") (pintype "bidirectional"))
    )
    (net (code "308") (name "Net-(T2-IN-)") (class "Default")
      (node (ref "C144") (pin "2") (pinfunction "2_2") (pintype "passive"))
      (node (ref "C146") (pin "1") (pinfunction "1_1") (pintype "passive"))
      (node (ref "T2") (pin "2") (pinfunction "IN-_2") (pintype "bidirectional"))
    )
    (net (code "309") (name "Net-(T2-OUT-)") (class "Default")
      (node (ref "R73") (pin "1") (pinfunction "1_1") (pintype "passive"))
      (node (ref "R76") (pin "1") (pinfunction "1_1") (pintype "passive"))
      (node (ref "T2") (pin "6") (pinfunction "OUT-_6") (pintype "bidirectional"))
    )
    (net (code "310") (name "Net-(T3-IN+)") (class "Default")
      (node (ref "C176") (pin "1") (pinfunction "1_1") (pintype "passive"))
      (node (ref "C179") (pin "1") (pinfunction "1_1") (pintype "passive"))
      (node (ref "T3") (pin "3") (pinfunction "IN+_3") (pintype "bidirectional"))
    )
    (net (code "311") (name "Net-(T3-IN-)") (class "Default")
      (node (ref "C176") (pin "2") (pinfunction "2_2") (pintype "passive"))
      (node (ref "C178") (pin "1") (pinfunction "1_1") (pintype "passive"))
      (node (ref "T3") (pin "2") (pinfunction "IN-_2") (pintype "bidirectional"))
    )
    (net (code "312") (name "Net-(T3-OUT-)") (class "Default")
      (node (ref "C170") (pin "2") (pinfunction "2_2") (pintype "passive"))
      (node (ref "T3") (pin "6") (pinfunction "OUT-_6") (pintype "bidirectional"))
    )
    (net (code "313") (name "Net-(U1-CLK)") (class "Default")
      (node (ref "R104") (pin "2") (pinfunction "2_2") (pintype "passive"))
      (node (ref "R111") (pin "1") (pinfunction "1_1") (pintype "passive"))
      (node (ref "U1") (pin "6") (pinfunction "CLK_6") (pintype "input"))
    )
    (net (code "314") (name "Net-(U1-DI)") (class "Default")
      (node (ref "R105") (pin "2") (pinfunction "2_2") (pintype "passive"))
      (node (ref "R112") (pin "1") (pinfunction "1_1") (pintype "passive"))
      (node (ref "U1") (pin "5") (pinfunction "DI_5") (pintype "input"))
    )
    (net (code "315") (name "Net-(U1-DO)") (class "Default")
      (node (ref "R106") (pin "2") (pinfunction "2_2") (pintype "passive"))
      (node (ref "R113") (pin "1") (pinfunction "1_1") (pintype "passive"))
      (node (ref "U1") (pin "2") (pinfunction "DO_2") (pintype "output"))
    )
    (net (code "316") (name "Net-(U1-~{CS})") (class "Default")
      (node (ref "R107") (pin "2") (pinfunction "2_2") (pintype "passive"))
      (node (ref "R114") (pin "1") (pinfunction "1_1") (pintype "passive"))
      (node (ref "U1") (pin "1") (pinfunction "~{CS}_1") (pintype "input"))
    )
    (net (code "317") (name "Net-(U2A-IO_L1N_VREF_0)") (class "Default")
      (node (ref "C223") (pin "1") (pinfunction "1_1") (pintype "passive"))
      (node (ref "R133") (pin "2") (pinfunction "2_2") (pintype "passive"))
      (node (ref "R143") (pin "2") (pinfunction "2_2") (pintype "passive"))
      (node (ref "U2") (pin "P143") (pinfunction "IO_L1N_VREF_0_P143") (pintype "bidirectional"))
    )
    (net (code "318") (name "Net-(U2A-IO_L1P_HSWAPEN_0)") (class "Default")
      (node (ref "C225") (pin "1") (pinfunction "1_1") (pintype "passive"))
      (node (ref "R132") (pin "1") (pinfunction "1_1") (pintype "passive"))
      (node (ref "R144") (pin "1") (pinfunction "1_1") (pintype "passive"))
      (node (ref "U2") (pin "P144") (pinfunction "IO_L1P_HSWAPEN_0_P144") (pintype "bidirectional"))
    )
    (net (code "319") (name "Net-(U2A-IO_L2N_0)") (class "Default")
      (node (ref "C229") (pin "1") (pinfunction "1_1") (pintype "passive"))
      (node (ref "R130") (pin "1") (pinfunction "1_1") (pintype "passive"))
      (node (ref "R146") (pin "1") (pinfunction "1_1") (pintype "passive"))
      (node (ref "U2") (pin "P141") (pinfunction "IO_L2N_0_P141") (pintype "bidirectional"))
    )
    (net (code "320") (name "Net-(U2A-IO_L3P_0)") (class "Default")
      (node (ref "C227") (pin "1") (pinfunction "1_1") (pintype "passive"))
      (node (ref "R131") (pin "2") (pinfunction "2_2") (pintype "passive"))
      (node (ref "R145") (pin "2") (pinfunction "2_2") (pintype "passive"))
      (node (ref "U2") (pin "P140") (pinfunction "IO_L3P_0_P140") (pintype "bidirectional"))
    )
    (net (code "321") (name "Net-(U2A-IO_L34N_GCLK18_0)") (class "Default")
      (node (ref "JP2") (pin "4") (pinfunction "4_4") (pintype "passive"))
      (node (ref "U2") (pin "P133") (pinfunction "IO_L34N_GCLK18_0_P133") (pintype "bidirectional"))
    )
    (net (code "322") (name "Net-(U2A-IO_L34P_GCLK19_0)") (class "Default")
      (node (ref "JP2") (pin "2") (pinfunction "2_2") (pintype "passive"))
      (node (ref "U2") (pin "P134") (pinfunction "IO_L34P_GCLK19_0_P134") (pintype "bidirectional"))
    )
    (net (code "323") (name "Net-(U2A-IO_L35N_GCLK16_0)") (class "Default")
      (node (ref "JP2") (pin "6") (pinfunction "6_6") (pintype "passive"))
      (node (ref "U2") (pin "P131") (pinfunction "IO_L35N_GCLK16_0_P131") (pintype "bidirectional"))
    )
    (net (code "324") (name "Net-(U2A-IO_L35P_GCLK17_0)") (class "Default")
      (node (ref "JP2") (pin "3") (pinfunction "3_3") (pintype "passive"))
      (node (ref "U2") (pin "P132") (pinfunction "IO_L35P_GCLK17_0_P132") (pintype "bidirectional"))
    )
    (net (code "325") (name "Net-(U2A-IO_L36N_GCLK14_0)") (class "Default")
      (node (ref "JP2") (pin "8") (pinfunction "8_8") (pintype "passive"))
      (node (ref "U2") (pin "P126") (pinfunction "IO_L36N_GCLK14_0_P126") (pintype "bidirectional"))
    )
    (net (code "326") (name "Net-(U2A-IO_L36P_GCLK15_0)") (class "Default")
      (node (ref "JP2") (pin "5") (pinfunction "5_5") (pintype "passive"))
      (node (ref "U2") (pin "P127") (pinfunction "IO_L36P_GCLK15_0_P127") (pintype "bidirectional"))
    )
    (net (code "327") (name "Net-(U2A-IO_L37N_GCLK12_0)") (class "Default")
      (node (ref "JP2") (pin "10") (pinfunction "10_10") (pintype "passive"))
      (node (ref "U2") (pin "P123") (pinfunction "IO_L37N_GCLK12_0_P123") (pintype "bidirectional"))
    )
    (net (code "328") (name "Net-(U2A-IO_L37P_GCLK13_0)") (class "Default")
      (node (ref "JP2") (pin "7") (pinfunction "7_7") (pintype "passive"))
      (node (ref "U2") (pin "P124") (pinfunction "IO_L37P_GCLK13_0_P124") (pintype "bidirectional"))
    )
    (net (code "329") (name "Net-(U2A-IO_L62N_VREF_0)") (class "Default")
      (node (ref "JP2") (pin "12") (pinfunction "12_12") (pintype "passive"))
      (node (ref "U2") (pin "P120") (pinfunction "IO_L62N_VREF_0_P120") (pintype "bidirectional"))
    )
    (net (code "330") (name "Net-(U2A-IO_L62P_0)") (class "Default")
      (node (ref "JP2") (pin "9") (pinfunction "9_9") (pintype "passive"))
      (node (ref "U2") (pin "P121") (pinfunction "IO_L62P_0_P121") (pintype "bidirectional"))
    )
    (net (code "331") (name "Net-(U2A-IO_L63N_SCP6_0)") (class "Default")
      (node (ref "JP2") (pin "14") (pinfunction "14_14") (pintype "passive"))
      (node (ref "U2") (pin "P118") (pinfunction "IO_L63N_SCP6_0_P118") (pintype "bidirectional"))
    )
    (net (code "332") (name "Net-(U2A-IO_L63P_SCP7_0)") (class "Default")
      (node (ref "JP2") (pin "11") (pinfunction "11_11") (pintype "passive"))
      (node (ref "U2") (pin "P119") (pinfunction "IO_L63P_SCP7_0_P119") (pintype "bidirectional"))
    )
    (net (code "333") (name "Net-(U2A-IO_L64N_SCP4_0)") (class "Default")
      (node (ref "JP2") (pin "16") (pinfunction "16_16") (pintype "passive"))
      (node (ref "U2") (pin "P116") (pinfunction "IO_L64N_SCP4_0_P116") (pintype "bidirectional"))
    )
    (net (code "334") (name "Net-(U2A-IO_L64P_SCP5_0)") (class "Default")
      (node (ref "JP2") (pin "13") (pinfunction "13_13") (pintype "passive"))
      (node (ref "U2") (pin "P117") (pinfunction "IO_L64P_SCP5_0_P117") (pintype "bidirectional"))
    )
    (net (code "335") (name "Net-(U2A-IO_L65N_SCP2_0)") (class "Default")
      (node (ref "JP2") (pin "18") (pinfunction "18_18") (pintype "passive"))
      (node (ref "U2") (pin "P114") (pinfunction "IO_L65N_SCP2_0_P114") (pintype "bidirectional"))
    )
    (net (code "336") (name "Net-(U2A-IO_L65P_SCP3_0)") (class "Default")
      (node (ref "JP2") (pin "15") (pinfunction "15_15") (pintype "passive"))
      (node (ref "U2") (pin "P115") (pinfunction "IO_L65P_SCP3_0_P115") (pintype "bidirectional"))
    )
    (net (code "337") (name "Net-(U2A-IO_L66N_SCP0_0)") (class "Default")
      (node (ref "JP2") (pin "19") (pinfunction "19_19") (pintype "passive"))
      (node (ref "U2") (pin "P111") (pinfunction "IO_L66N_SCP0_0_P111") (pintype "bidirectional"))
    )
    (net (code "338") (name "Net-(U2A-IO_L66P_SCP1_0)") (class "Default")
      (node (ref "JP2") (pin "17") (pinfunction "17_17") (pintype "passive"))
      (node (ref "U2") (pin "P112") (pinfunction "IO_L66P_SCP1_0_P112") (pintype "bidirectional"))
    )
    (net (code "339") (name "Net-(U2B-IO_L41N_GCLK8_1)") (class "Default")
      (node (ref "R135") (pin "2") (pinfunction "2_2") (pintype "passive"))
      (node (ref "U2") (pin "P92") (pinfunction "IO_L41N_GCLK8_1_P92") (pintype "bidirectional"))
    )
    (net (code "340") (name "Net-(U2B-IO_L41P_GCLK9_IRDY1_1)") (class "Default")
      (node (ref "R136") (pin "2") (pinfunction "2_2") (pintype "passive"))
      (node (ref "U2") (pin "P93") (pinfunction "IO_L41P_GCLK9_IRDY1_1_P93") (pintype "bidirectional"))
    )
    (net (code "341") (name "Net-(U2B-IO_L42N_GCLK6_TRDY1_1)") (class "Default")
      (node (ref "R138") (pin "2") (pinfunction "2_2") (pintype "passive"))
      (node (ref "U2") (pin "P87") (pinfunction "IO_L42N_GCLK6_TRDY1_1_P87") (pintype "bidirectional"))
    )
    (net (code "342") (name "Net-(U2B-IO_L42P_GCLK7_1)") (class "Default")
      (node (ref "R137") (pin "2") (pinfunction "2_2") (pintype "passive"))
      (node (ref "U2") (pin "P88") (pinfunction "IO_L42P_GCLK7_1_P88") (pintype "bidirectional"))
    )
    (net (code "343") (name "Net-(U2B-IO_L43N_GCLK4_1)") (class "Default")
      (node (ref "R140") (pin "2") (pinfunction "2_2") (pintype "passive"))
      (node (ref "U2") (pin "P84") (pinfunction "IO_L43N_GCLK4_1_P84") (pintype "bidirectional"))
    )
    (net (code "344") (name "Net-(U2B-IO_L43P_GCLK5_1)") (class "Default")
      (node (ref "R139") (pin "2") (pinfunction "2_2") (pintype "passive"))
      (node (ref "U2") (pin "P85") (pinfunction "IO_L43P_GCLK5_1_P85") (pintype "bidirectional"))
    )
    (net (code "345") (name "Net-(U2B-IO_L45N_1)") (class "Default")
      (node (ref "R142") (pin "2") (pinfunction "2_2") (pintype "passive"))
      (node (ref "U2") (pin "P82") (pinfunction "IO_L45N_1_P82") (pintype "bidirectional"))
    )
    (net (code "346") (name "Net-(U2B-IO_L45P_1)") (class "Default")
      (node (ref "R141") (pin "2") (pinfunction "2_2") (pintype "passive"))
      (node (ref "U2") (pin "P83") (pinfunction "IO_L45P_1_P83") (pintype "bidirectional"))
    )
    (net (code "347") (name "Net-(U2C-IO_L14N_D12_2)") (class "Default")
      (node (ref "C232") (pin "1") (pinfunction "1_1") (pintype "passive"))
      (node (ref "R122") (pin "2") (pinfunction "2_2") (pintype "passive"))
      (node (ref "R147") (pin "1") (pinfunction "1_1") (pintype "passive"))
      (node (ref "U2") (pin "P57") (pinfunction "IO_L14N_D12_2_P57") (pintype "bidirectional"))
    )
    (net (code "348") (name "Net-(U2C-IO_L14P_D11_2)") (class "Default")
      (node (ref "C234") (pin "1") (pinfunction "1_1") (pintype "passive"))
      (node (ref "R121") (pin "1") (pinfunction "1_1") (pintype "passive"))
      (node (ref "R148") (pin "2") (pinfunction "2_2") (pintype "passive"))
      (node (ref "U2") (pin "P58") (pinfunction "IO_L14P_D11_2_P58") (pintype "bidirectional"))
    )
    (net (code "349") (name "Net-(U2C-IO_L31N_GCLK30_D15_2)") (class "Default")
      (node (ref "R126") (pin "2") (pinfunction "2_2") (pintype "passive"))
      (node (ref "U2") (pin "P50") (pinfunction "IO_L31N_GCLK30_D15_2_P50") (pintype "bidirectional"))
    )
    (net (code "350") (name "Net-(U2C-IO_L62N_D6_2)") (class "Default")
      (node (ref "R123") (pin "2") (pinfunction "2_2") (pintype "passive"))
      (node (ref "U2") (pin "P43") (pinfunction "IO_L62N_D6_2_P43") (pintype "bidirectional"))
    )
    (net (code "351") (name "Net-(U2C-IO_L64P_D8_2)") (class "Default")
      (node (ref "R124") (pin "2") (pinfunction "2_2") (pintype "passive"))
      (node (ref "U2") (pin "P41") (pinfunction "IO_L64P_D8_2_P41") (pintype "bidirectional"))
    )
    (net (code "352") (name "Net-(Y1-OUT)") (class "Default")
      (node (ref "C34") (pin "2") (pinfunction "2_2") (pintype "passive"))
      (node (ref "Y1") (pin "3") (pinfunction "OUT_3") (pintype "output"))
    )
    (net (code "353") (name "PORT1LO1") (class "Default")
      (node (ref "C269") (pin "1") (pinfunction "1_1") (pintype "passive"))
      (node (ref "IC21") (pin "12") (pinfunction "RFOUTA_P_12") (pintype "bidirectional"))
      (node (ref "R32") (pin "1") (pinfunction "1_1") (pintype "passive"))
    )
    (net (code "354") (name "PORT1LO2") (class "Default")
      (node (ref "C46") (pin "1") (pinfunction "1_1") (pintype "passive"))
      (node (ref "C98") (pin "1") (pinfunction "1_1") (pintype "passive"))
      (node (ref "R177") (pin "2") (pinfunction "2_2") (pintype "passive"))
    )
    (net (code "355") (name "PORT1MIX1_EN") (class "Default")
      (node (ref "C230") (pin "1") (pinfunction "1_1") (pintype "passive"))
      (node (ref "IC24") (pin "9") (pinfunction "ENBL_9") (pintype "bidirectional"))
      (node (ref "R146") (pin "2") (pinfunction "2_2") (pintype "passive"))
    )
    (net (code "356") (name "PORT1MIX2_EN") (class "Default")
      (node (ref "C228") (pin "1") (pinfunction "1_1") (pintype "passive"))
      (node (ref "IC22") (pin "2") (pinfunction "EN_2") (pintype "bidirectional"))
      (node (ref "IC23") (pin "7") (pinfunction "SHDN_7") (pintype "bidirectional"))
      (node (ref "R145") (pin "1") (pinfunction "1_1") (pintype "passive"))
    )
    (net (code "357") (name "PORT1SRC") (class "Default")
      (node (ref "C96") (pin "1") (pinfunction "1_1") (pintype "passive"))
      (node (ref "IC18") (pin "3") (pinfunction "RF1_3") (pintype "bidirectional"))
    )
    (net (code "358") (name "PORT1SWITCH") (class "Default")
      (node (ref "C241") (pin "1") (pinfunction "1_1") (pintype "passive"))
      (node (ref "R152") (pin "2") (pinfunction "2_2") (pintype "passive"))
      (node (ref "U2") (pin "P142") (pinfunction "IO_L2P_0_P142") (pintype "bidirectional"))
    )
    (net (code "359") (name "PORT1_CONVSTART") (class "Default")
      (node (ref "IC26") (pin "6") (pinfunction "CONVST_6") (pintype "bidirectional"))
      (node (ref "U2") (pin "P139") (pinfunction "IO_L3N_0_P139") (pintype "bidirectional"))
    )
    (net (code "360") (name "PORT1_SCLK") (class "Default")
      (node (ref "IC26") (pin "8") (pinfunction "SCLK_8") (pintype "bidirectional"))
      (node (ref "U2") (pin "P137") (pinfunction "IO_L4N_0_P137") (pintype "bidirectional"))
    )
    (net (code "361") (name "PORT1_SDO") (class "Default")
      (node (ref "IC26") (pin "7") (pinfunction "SDO_7") (pintype "bidirectional"))
      (node (ref "U2") (pin "P138") (pinfunction "IO_L4P_0_P138") (pintype "bidirectional"))
    )
    (net (code "362") (name "PORT2LO1") (class "Default")
      (node (ref "C151") (pin "1") (pinfunction "1_1") (pintype "passive"))
      (node (ref "IC21") (pin "14") (pinfunction "RFOUTB_P_14") (pintype "bidirectional"))
      (node (ref "R34") (pin "1") (pinfunction "1_1") (pintype "passive"))
    )
    (net (code "363") (name "PORT2LO2") (class "Default")
      (node (ref "C135") (pin "1") (pinfunction "1_1") (pintype "passive"))
      (node (ref "C44") (pin "1") (pinfunction "1_1") (pintype "passive"))
      (node (ref "R181") (pin "2") (pinfunction "2_2") (pintype "passive"))
    )
    (net (code "364") (name "PORT2MIX1_EN") (class "Default")
      (node (ref "C233") (pin "1") (pinfunction "1_1") (pintype "passive"))
      (node (ref "IC29") (pin "9") (pinfunction "ENBL_9") (pintype "bidirectional"))
      (node (ref "R148") (pin "1") (pinfunction "1_1") (pintype "passive"))
    )
    (net (code "365") (name "PORT2MIX2_EN") (class "Default")
      (node (ref "C231") (pin "1") (pinfunction "1_1") (pintype "passive"))
      (node (ref "IC27") (pin "2") (pinfunction "EN_2") (pintype "bidirectional"))
      (node (ref "IC28") (pin "7") (pinfunction "SHDN_7") (pintype "bidirectional"))
      (node (ref "R147") (pin "2") (pinfunction "2_2") (pintype "passive"))
    )
    (net (code "366") (name "PORT2SRC") (class "Default")
      (node (ref "C133") (pin "1") (pinfunction "1_1") (pintype "passive"))
      (node (ref "IC17") (pin "8") (pinfunction "RF_COM_8") (pintype "bidirectional"))
    )
    (net (code "367") (name "PORT2SWITCH") (class "Default")
      (node (ref "C235") (pin "1") (pinfunction "1_1") (pintype "passive"))
      (node (ref "R149") (pin "2") (pinfunction "2_2") (pintype "passive"))
      (node (ref "U2") (pin "P40") (pinfunction "IO_L64N_D9_2_P40") (pintype "bidirectional"))
    )
    (net (code "368") (name "PORT2_CONVSTART") (class "Default")
      (node (ref "IC31") (pin "6") (pinfunction "CONVST_6") (pintype "bidirectional"))
      (node (ref "U2") (pin "P44") (pinfunction "IO_L62P_D5_2_P44") (pintype "bidirectional"))
    )
    (net (code "369") (name "PORT2_SCLK") (class "Default")
      (node (ref "IC31") (pin "8") (pinfunction "SCLK_8") (pintype "bidirectional"))
      (node (ref "R124") (pin "1") (pinfunction "1_1") (pintype "passive"))
    )
    (net (code "370") (name "PORT2_SDO") (class "Default")
      (node (ref "IC31") (pin "7") (pinfunction "SDO_7") (pintype "bidirectional"))
      (node (ref "R123") (pin "1") (pinfunction "1_1") (pintype "passive"))
    )
    (net (code "371") (name "PORTSWITCH1") (class "Default")
      (node (ref "C239") (pin "1") (pinfunction "1_1") (pintype "passive"))
      (node (ref "R151") (pin "2") (pinfunction "2_2") (pintype "passive"))
      (node (ref "U2") (pin "P6") (pinfunction "IO_L52P_3_P6") (pintype "bidirectional"))
    )
    (net (code "372") (name "PORTSWITCH2") (class "Default")
      (node (ref "C237") (pin "1") (pinfunction "1_1") (pintype "passive"))
      (node (ref "R150") (pin "2") (pinfunction "2_2") (pintype "passive"))
      (node (ref "U2") (pin "P7") (pinfunction "IO_L51N_3_P7") (pintype "bidirectional"))
    )
    (net (code "373") (name "REFLO1") (class "Default")
      (node (ref "C270") (pin "1") (pinfunction "1_1") (pintype "passive"))
      (node (ref "IC21") (pin "13") (pinfunction "RFOUTA_N_13") (pintype "bidirectional"))
      (node (ref "R33") (pin "1") (pinfunction "1_1") (pintype "passive"))
    )
    (net (code "374") (name "REFLO2") (class "Default")
      (node (ref "C200") (pin "1") (pinfunction "1_1") (pintype "passive"))
      (node (ref "C45") (pin "1") (pinfunction "1_1") (pintype "passive"))
      (node (ref "R178") (pin "2") (pinfunction "2_2") (pintype "passive"))
    )
    (net (code "375") (name "REFMIX1_EN") (class "Default")
      (node (ref "C226") (pin "1") (pinfunction "1_1") (pintype "passive"))
      (node (ref "IC33") (pin "9") (pinfunction "ENBL_9") (pintype "bidirectional"))
      (node (ref "R144") (pin "2") (pinfunction "2_2") (pintype "passive"))
    )
    (net (code "376") (name "REFMIX2_EN") (class "Default")
      (node (ref "C224") (pin "1") (pinfunction "1_1") (pintype "passive"))
      (node (ref "IC32") (pin "7") (pinfunction "SHDN_7") (pintype "bidirectional"))
      (node (ref "IC36") (pin "2") (pinfunction "EN_2") (pintype "bidirectional"))
      (node (ref "R143") (pin "1") (pinfunction "1_1") (pintype "passive"))
    )
    (net (code "377") (name "REFSRC") (class "Default")
      (node (ref "C170") (pin "1") (pinfunction "1_1") (pintype "passive"))
      (node (ref "R27") (pin "1") (pinfunction "1_1") (pintype "passive"))
      (node (ref "R28") (pin "2") (pinfunction "2_2") (pintype "passive"))
    )
    (net (code "378") (name "REF_CONVSTART") (class "Default")
      (node (ref "IC35") (pin "6") (pinfunction "CONVST_6") (pintype "bidirectional"))
      (node (ref "U2") (pin "P5") (pinfunction "IO_L52N_3_P5") (pintype "bidirectional"))
    )
    (net (code "379") (name "REF_SCLK") (class "Default")
      (node (ref "IC35") (pin "8") (pinfunction "SCLK_8") (pintype "bidirectional"))
      (node (ref "U2") (pin "P1") (pinfunction "IO_L83N_VREF_3_P1") (pintype "bidirectional"))
    )
    (net (code "380") (name "REF_SDO") (class "Default")
      (node (ref "IC35") (pin "7") (pinfunction "SDO_7") (pintype "bidirectional"))
      (node (ref "U2") (pin "P2") (pinfunction "IO_L83P_3_P2") (pintype "bidirectional"))
    )
    (net (code "381") (name "SCL") (class "Default")
      (node (ref "IC2") (pin "11") (pinfunction "SCL_11") (pintype "bidirectional"))
      (node (ref "IC37") (pin "16") (pinfunction "PC4_16") (pintype "bidirectional"))
      (node (ref "IC7") (pin "4") (pinfunction "SCL_4") (pintype "bidirectional"))
      (node (ref "R116") (pin "1") (pinfunction "1_1") (pintype "passive"))
    )
    (net (code "382") (name "SDA") (class "Default")
      (node (ref "IC2") (pin "10") (pinfunction "SDA_10") (pintype "bidirectional"))
      (node (ref "IC37") (pin "30") (pinfunction "PA8_30") (pintype "bidirectional"))
      (node (ref "IC7") (pin "5") (pinfunction "SDA_5") (pintype "bidirectional"))
      (node (ref "R117") (pin "1") (pinfunction "1_1") (pintype "passive"))
    )
    (net (code "383") (name "SOURCE_CE") (class "Default")
      (node (ref "C267") (pin "1") (pinfunction "1_1") (pintype "passive"))
      (node (ref "R11") (pin "2") (pinfunction "2_2") (pintype "passive"))
      (node (ref "R163") (pin "2") (pinfunction "2_2") (pintype "passive"))
      (node (ref "U2") (pin "P27") (pinfunction "IO_L37P_3_P27") (pintype "bidirectional"))
    )
    (net (code "384") (name "SOURCE_CLK") (class "Default")
      (node (ref "R164") (pin "2") (pinfunction "2_2") (pintype "passive"))
      (node (ref "U2") (pin "P32") (pinfunction "IO_L2N_3_P32") (pintype "bidirectional"))
    )
    (net (code "385") (name "SOURCE_HIGHBAND") (class "Default")
      (node (ref "C68") (pin "2") (pinfunction "2_2") (pintype "passive"))
      (node (ref "IC13") (pin "3") (pinfunction "RF1_3") (pintype "bidirectional"))
    )
    (net (code "386") (name "SOURCE_LD") (class "Default")
      (node (ref "C273") (pin "1") (pinfunction "1_1") (pintype "passive"))
      (node (ref "R166") (pin "2") (pinfunction "2_2") (pintype "passive"))
      (node (ref "U2") (pin "P35") (pinfunction "IO_L1P_3_P35") (pintype "bidirectional"))
    )
    (net (code "387") (name "SOURCE_LE") (class "Default")
      (node (ref "R171") (pin "2") (pinfunction "2_2") (pintype "passive"))
      (node (ref "U2") (pin "P29") (pinfunction "IO_L36N_3_P29") (pintype "bidirectional"))
    )
    (net (code "388") (name "SOURCE_LOWBAND") (class "Default")
      (node (ref "C48") (pin "1") (pinfunction "1_1") (pintype "passive"))
      (node (ref "IC13") (pin "13") (pinfunction "RF2_13") (pintype "bidirectional"))
    )
    (net (code "389") (name "SOURCE_MOSI") (class "Default")
      (node (ref "R170") (pin "2") (pinfunction "2_2") (pintype "passive"))
      (node (ref "U2") (pin "P30") (pinfunction "IO_L36P_3_P30") (pintype "bidirectional"))
    )
    (net (code "390") (name "SOURCE_MUX") (class "Default")
      (node (ref "R167") (pin "2") (pinfunction "2_2") (pintype "passive"))
      (node (ref "U2") (pin "P33") (pinfunction "IO_L2P_3_P33") (pintype "bidirectional"))
    )
    (net (code "391") (name "SOURCE_REF") (class "Default")
      (node (ref "C51") (pin "1") (pinfunction "1_1") (pintype "passive"))
      (node (ref "IC7") (pin "8") (pinfunction "CLK3_8") (pintype "bidirectional"))
    )
    (net (code "392") (name "SOURCE_RF_EN") (class "Default")
      (node (ref "C271") (pin "1") (pinfunction "1_1") (pintype "passive"))
      (node (ref "R165") (pin "2") (pinfunction "2_2") (pintype "passive"))
      (node (ref "U2") (pin "P34") (pinfunction "IO_L1N_VREF_3_P34") (pintype "bidirectional"))
    )
    (net (code "393") (name "SOURCE_VCC") (class "Default")
      (node (ref "C57") (pin "1") (pinfunction "1_1") (pintype "passive"))
      (node (ref "IC10") (pin "10") (pinfunction "VCC_PLL_10") (pintype "bidirectional"))
      (node (ref "IC10") (pin "6") (pinfunction "VCC_CP_6") (pintype "bidirectional"))
      (node (ref "IC11") (pin "3") (pinfunction "VDD_3") (pintype "bidirectional"))
      (node (ref "IC12") (pin "3") (pinfunction "VDD_3") (pintype "bidirectional"))
      (node (ref "L20") (pin "2") (pinfunction "2_2") (pintype "passive"))
      (node (ref "TP13") (pin "TP") (pinfunction "TP_TP") (pintype "input"))
    )
    (net (code "394") (name "SWCLK") (class "Default")
      (node (ref "IC37") (pin "37") (pinfunction "PA14_37") (pintype "bidirectional"))
      (node (ref "JP1") (pin "6") (pinfunction "6_6") (pintype "passive"))
    )
    (net (code "395") (name "SWDIO") (class "Default")
      (node (ref "IC37") (pin "36") (pinfunction "PA13_36") (pintype "bidirectional"))
      (node (ref "JP1") (pin "8") (pinfunction "8_8") (pintype "passive"))
    )
    (net (code "396") (name "TCK") (class "Default")
      (node (ref "JP1") (pin "1") (pinfunction "1_1") (pintype "passive"))
      (node (ref "U2") (pin "P109") (pinfunction "TCK_P109") (pintype "input"))
    )
    (net (code "397") (name "TDI") (class "Default")
      (node (ref "JP1") (pin "3") (pinfunction "3_3") (pintype "passive"))
      (node (ref "U2") (pin "P110") (pinfunction "TDI_P110") (pintype "input"))
    )
    (net (code "398") (name "TDO") (class "Default")
      (node (ref "JP1") (pin "2") (pinfunction "2_2") (pintype "passive"))
      (node (ref "U2") (pin "P106") (pinfunction "TDO_P106") (pintype "output"))
    )
    (net (code "399") (name "TMS") (class "Default")
      (node (ref "JP1") (pin "4") (pinfunction "4_4") (pintype "passive"))
      (node (ref "U2") (pin "P107") (pinfunction "TMS_P107") (pintype "input"))
    )
    (net (code "400") (name "UART_TX") (class "Default")
      (node (ref "IC37") (pin "39") (pinfunction "PC10_39") (pintype "bidirectional"))
      (node (ref "JP1") (pin "10") (pinfunction "10_10") (pintype "passive"))
    )
    (net (code "401") (name "USB_POWER") (class "Default")
      (node (ref "J4") (pin "11") (pinfunction "VBUS_11") (pintype "bidirectional"))
      (node (ref "J4") (pin "2") (pinfunction "VBUS_2") (pintype "bidirectional"))
      (node (ref "Q1") (pin "3") (pinfunction "D_3") (pintype "passive"))
    )
    (net (code "402") (name "VCCINT") (class "Default")
      (node (ref "C10") (pin "1") (pinfunction "1_1") (pintype "passive"))
      (node (ref "C211") (pin "1") (pinfunction "1_1") (pintype "passive"))
      (node (ref "C213") (pin "1") (pinfunction "1_1") (pintype "passive"))
      (node (ref "C215") (pin "1") (pinfunction "1_1") (pintype "passive"))
      (node (ref "C217") (pin "1") (pinfunction "1_1") (pintype "passive"))
      (node (ref "C219") (pin "1") (pinfunction "1_1") (pintype "passive"))
      (node (ref "C7") (pin "1") (pinfunction "1_1") (pintype "passive"))
      (node (ref "IC2") (pin "9") (pinfunction "FB_9") (pintype "bidirectional"))
      (node (ref "L2") (pin "P$2") (pinfunction "2_P$2") (pintype "passive"))
      (node (ref "TP1") (pin "TP") (pinfunction "TP_TP") (pintype "input"))
      (node (ref "U2") (pin "P128") (pinfunction "VCCINT_P128") (pintype "input"))
      (node (ref "U2") (pin "P19") (pinfunction "VCCINT_P19") (pintype "input"))
      (node (ref "U2") (pin "P28") (pinfunction "VCCINT_P28") (pintype "input"))
      (node (ref "U2") (pin "P52") (pinfunction "VCCINT_P52") (pintype "input"))
      (node (ref "U2") (pin "P89") (pinfunction "VCCINT_P89") (pintype "input"))
    )
    (net (code "403") (name "unconnected-(IC2A-{slash}POR-Pad12)") (class "Default")
      (node (ref "IC2") (pin "12") (pinfunction "/POR_12") (pintype "bidirectional"))
    )
    (net (code "404") (name "unconnected-(IC2B-{slash}POR-Pad13)") (class "Default")
      (node (ref "IC2") (pin "13") (pinfunction "/POR_13") (pintype "bidirectional"))
    )
    (net (code "405") (name "unconnected-(IC7-INTR-Pad3)") (class "Default")
      (node (ref "IC7") (pin "3") (pinfunction "INTR_3") (pintype "bidirectional"))
    )
    (net (code "406") (name "unconnected-(IC7-XB-Pad2)") (class "Default")
      (node (ref "IC7") (pin "2") (pinfunction "XB_2") (pintype "bidirectional"))
    )
    (net (code "407") (name "unconnected-(IC10-RFOUTB_N-Pad15)") (class "Default")
      (node (ref "IC10") (pin "15") (pinfunction "RFOUTB_N_15") (pintype "bidirectional"))
    )
    (net (code "408") (name "unconnected-(IC10-RFOUTB_P-Pad14)") (class "Default")
      (node (ref "IC10") (pin "14") (pinfunction "RFOUTB_P_14") (pintype "bidirectional"))
    )
    (net (code "409") (name "unconnected-(IC14-CLK-Pad17)") (class "Default")
      (node (ref "IC14") (pin "17") (pinfunction "CLK_17") (pintype "bidirectional"))
    )
    (net (code "410") (name "unconnected-(IC14-DATA-Pad18)") (class "Default")
      (node (ref "IC14") (pin "18") (pinfunction "DATA_18") (pintype "bidirectional"))
    )
    (net (code "411") (name "unconnected-(IC17-RF2-Pad13)") (class "Default")
      (node (ref "IC17") (pin "13") (pinfunction "RF2_13") (pintype "bidirectional"))
    )
    (net (code "412") (name "unconnected-(IC18-RF2-Pad13)") (class "Default")
      (node (ref "IC18") (pin "13") (pinfunction "RF2_13") (pintype "bidirectional"))
    )
    (net (code "413") (name "unconnected-(IC37-PA0-Pad8)") (class "Default")
      (node (ref "IC37") (pin "8") (pinfunction "PA0_8") (pintype "bidirectional"))
    )
    (net (code "414") (name "unconnected-(IC37-PB10-Pad22)") (class "Default")
      (node (ref "IC37") (pin "22") (pinfunction "PB10_22") (pintype "bidirectional"))
    )
    (net (code "415") (name "unconnected-(IC37-PB11-Pad24)") (class "Default")
      (node (ref "IC37") (pin "24") (pinfunction "PB11_24") (pintype "bidirectional"))
    )
    (net (code "416") (name "unconnected-(IC37-PB14-Pad27)") (class "Default")
      (node (ref "IC37") (pin "27") (pinfunction "PB14_27") (pintype "bidirectional"))
    )
    (net (code "417") (name "unconnected-(IC37-PC6-Pad29)") (class "Default")
      (node (ref "IC37") (pin "29") (pinfunction "PC6_29") (pintype "bidirectional"))
    )
    (net (code "418") (name "unconnected-(IC37-PC13-Pad2)") (class "Default")
      (node (ref "IC37") (pin "2") (pinfunction "PC13_2") (pintype "bidirectional"))
    )
    (net (code "419") (name "unconnected-(IC37-PC14-OSC32_IN-Pad3)") (class "Default")
      (node (ref "IC37") (pin "3") (pinfunction "PC14-OSC32_IN_3") (pintype "bidirectional"))
    )
    (net (code "420") (name "unconnected-(IC37-PC15-OSC32_OUT-Pad4)") (class "Default")
      (node (ref "IC37") (pin "4") (pinfunction "PC15-OSC32_OUT_4") (pintype "bidirectional"))
    )
    (net (code "421") (name "unconnected-(IC37-PF0-OSC_IN-Pad5)") (class "Default")
      (node (ref "IC37") (pin "5") (pinfunction "PF0-OSC_IN_5") (pintype "bidirectional"))
    )
    (net (code "422") (name "unconnected-(J4-SBU1-Pad9)") (class "Default")
      (node (ref "J4") (pin "9") (pinfunction "SBU1_9") (pintype "bidirectional"))
    )
    (net (code "423") (name "unconnected-(J4-SBU2-Pad3)") (class "Default")
      (node (ref "J4") (pin "3") (pinfunction "SBU2_3") (pintype "bidirectional"))
    )
    (net (code "424") (name "unconnected-(U2B-IO_L1N_VREF_1-PadP104)") (class "Default")
      (node (ref "U2") (pin "P104") (pinfunction "IO_L1N_VREF_1_P104") (pintype "bidirectional"))
    )
    (net (code "425") (name "unconnected-(U2B-IO_L1P_1-PadP105)") (class "Default")
      (node (ref "U2") (pin "P105") (pinfunction "IO_L1P_1_P105") (pintype "bidirectional"))
    )
    (net (code "426") (name "unconnected-(U2B-IO_L32N_1-PadP101)") (class "Default")
      (node (ref "U2") (pin "P101") (pinfunction "IO_L32N_1_P101") (pintype "bidirectional"))
    )
    (net (code "427") (name "unconnected-(U2B-IO_L32P_1-PadP102)") (class "Default")
      (node (ref "U2") (pin "P102") (pinfunction "IO_L32P_1_P102") (pintype "bidirectional"))
    )
    (net (code "428") (name "unconnected-(U2B-IO_L33N_1-PadP99)") (class "Default")
      (node (ref "U2") (pin "P99") (pinfunction "IO_L33N_1_P99") (pintype "bidirectional"))
    )
    (net (code "429") (name "unconnected-(U2B-IO_L33P_1-PadP100)") (class "Default")
      (node (ref "U2") (pin "P100") (pinfunction "IO_L33P_1_P100") (pintype "bidirectional"))
    )
    (net (code "430") (name "unconnected-(U2B-IO_L34N_1-PadP97)") (class "Default")
      (node (ref "U2") (pin "P97") (pinfunction "IO_L34N_1_P97") (pintype "bidirectional"))
    )
    (net (code "431") (name "unconnected-(U2B-IO_L34P_1-PadP98)") (class "Default")
      (node (ref "U2") (pin "P98") (pinfunction "IO_L34P_1_P98") (pintype "bidirectional"))
    )
    (net (code "432") (name "unconnected-(U2B-IO_L40N_GCLK10_1-PadP94)") (class "Default")
      (node (ref "U2") (pin "P94") (pinfunction "IO_L40N_GCLK10_1_P94") (pintype "bidirectional"))
    )
    (net (code "433") (name "unconnected-(U2B-IO_L40P_GCLK11_1-PadP95)") (class "Default")
      (node (ref "U2") (pin "P95") (pinfunction "IO_L40P_GCLK11_1_P95") (pintype "bidirectional"))
    )
  )
)
